# STM32_output_card.net
KiCad netlist of a schematic drawn in EAGLE
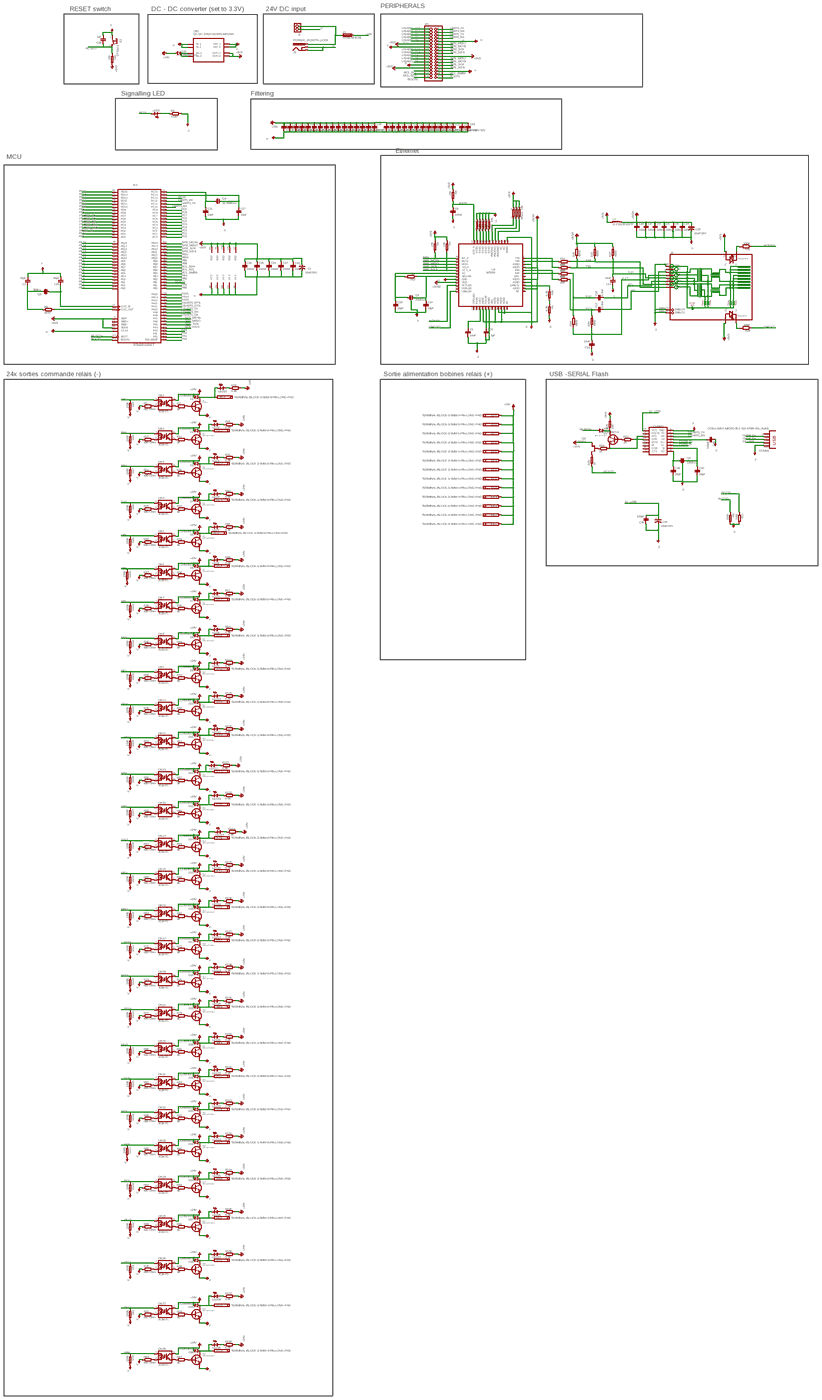
[diagram p0: schematic, sheet 1, overview]
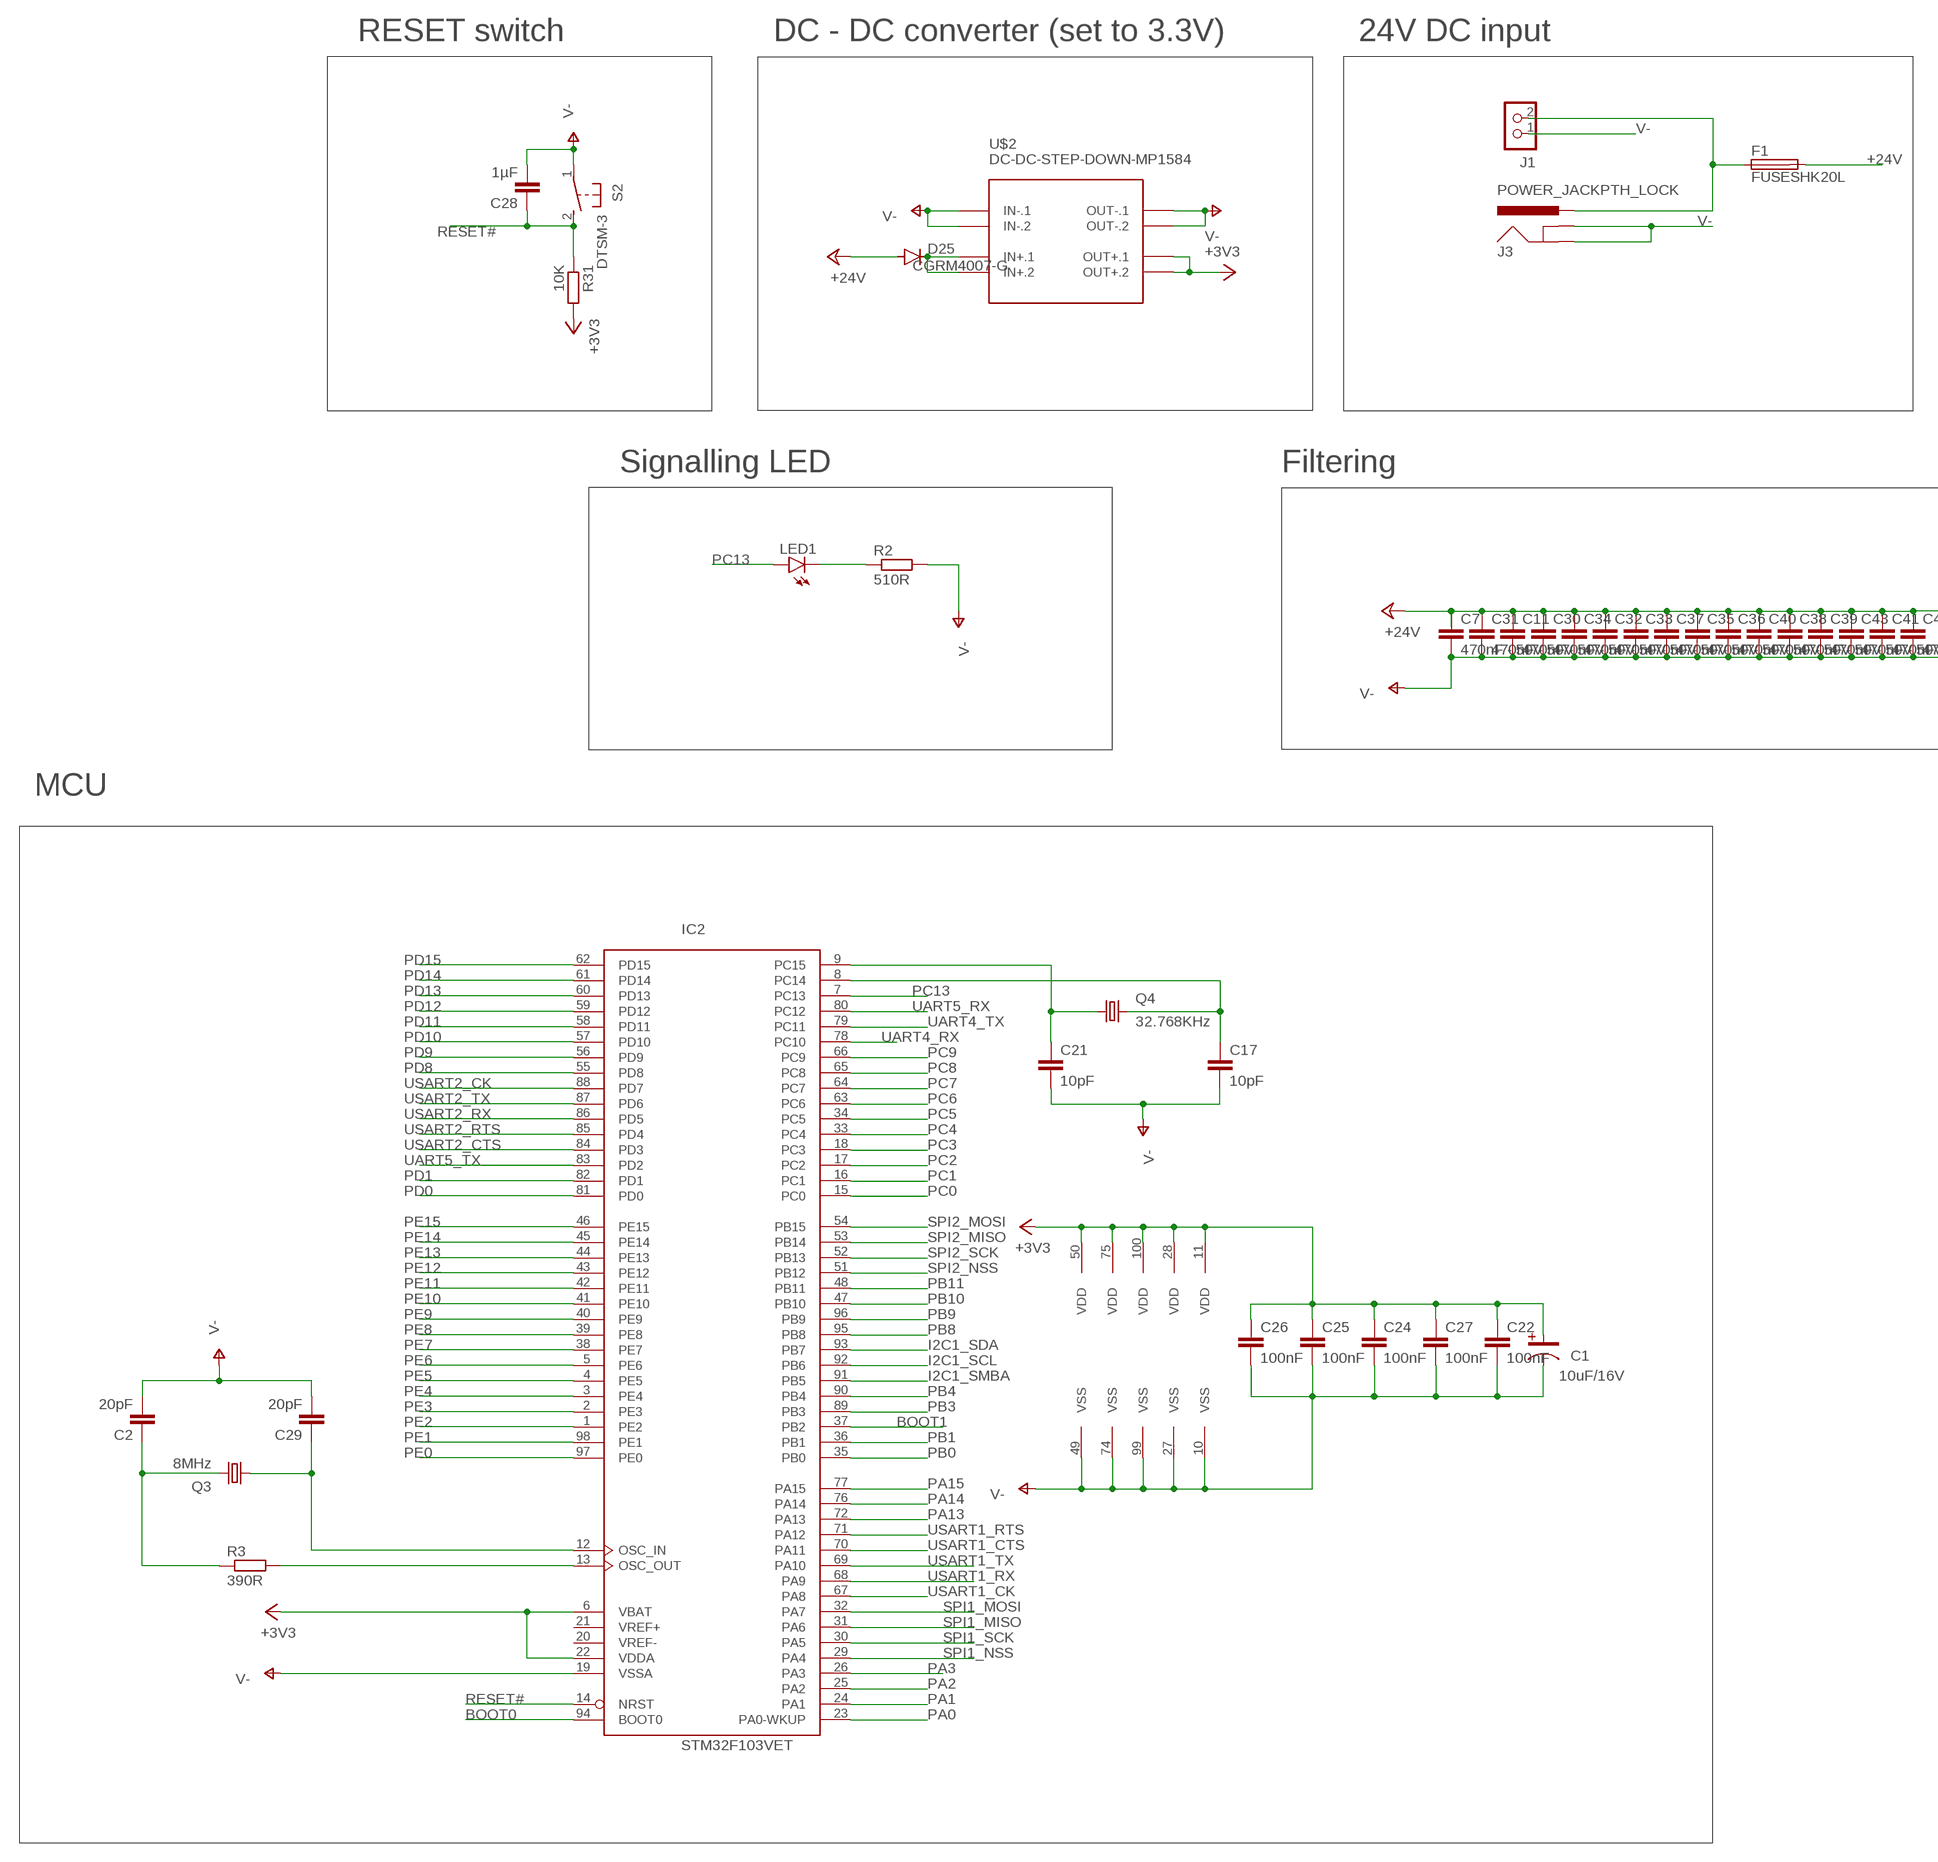
[diagram p1: schematic, sheet 1, part 1 of 6]
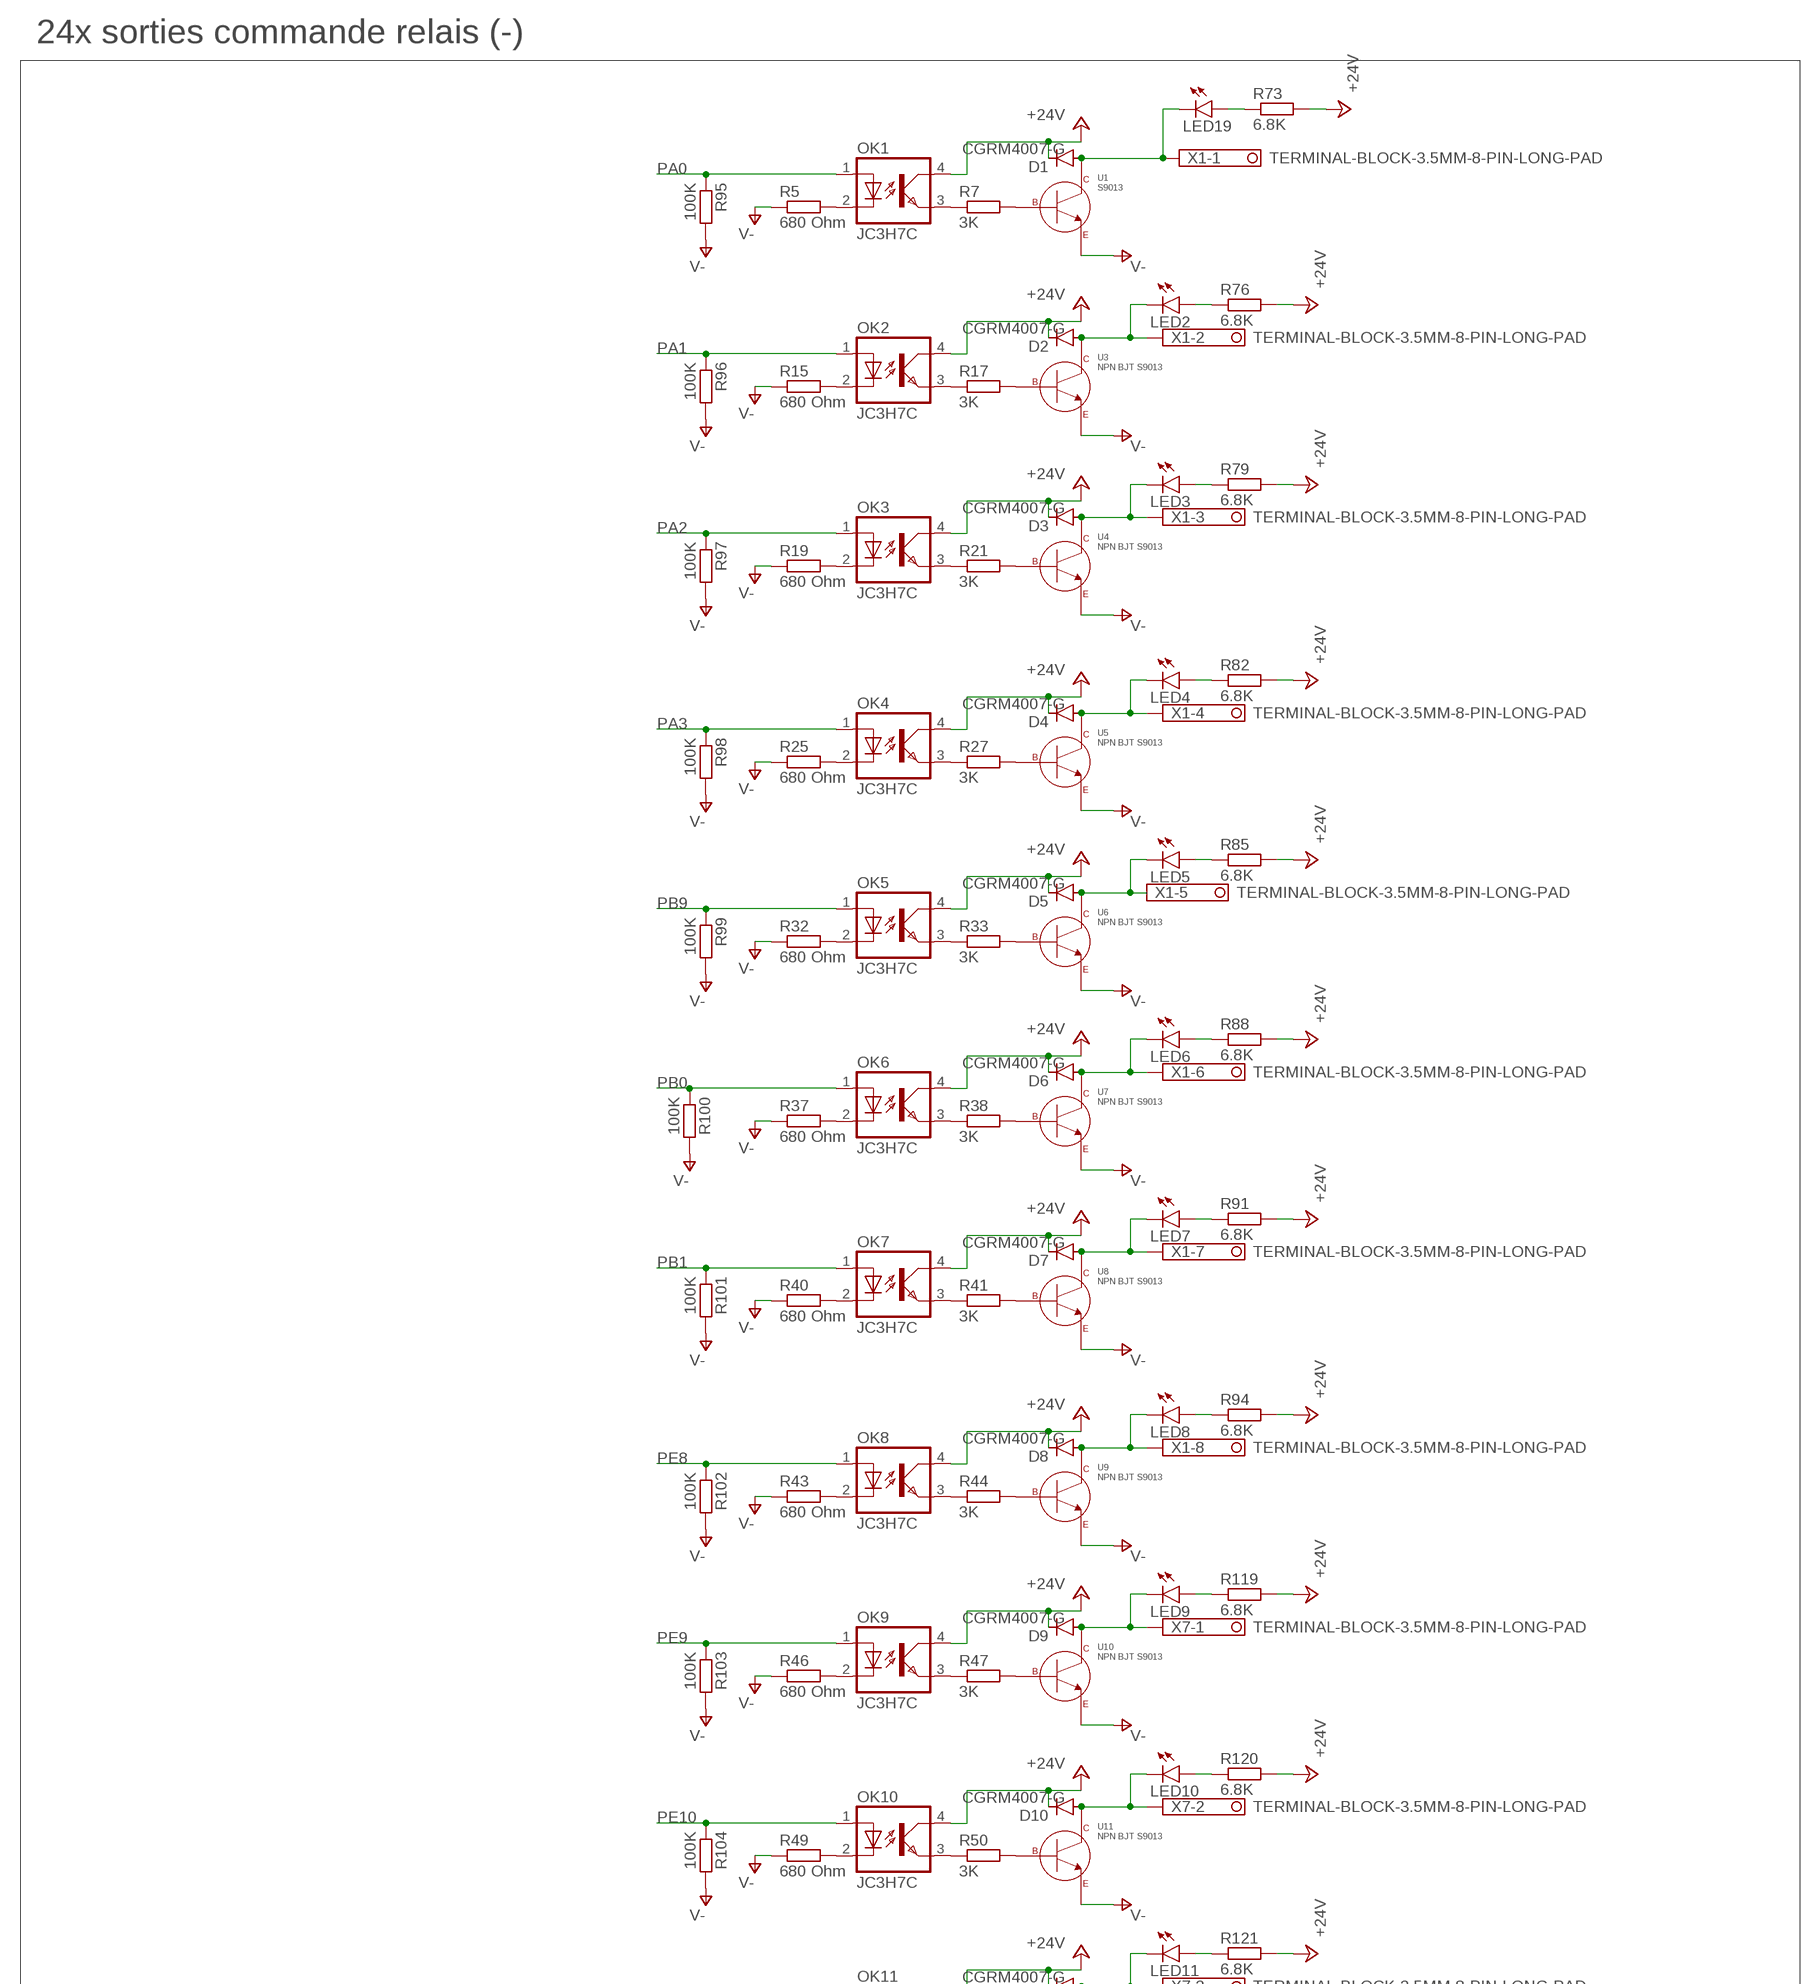
[diagram p2: schematic, sheet 1, part 2 of 6]
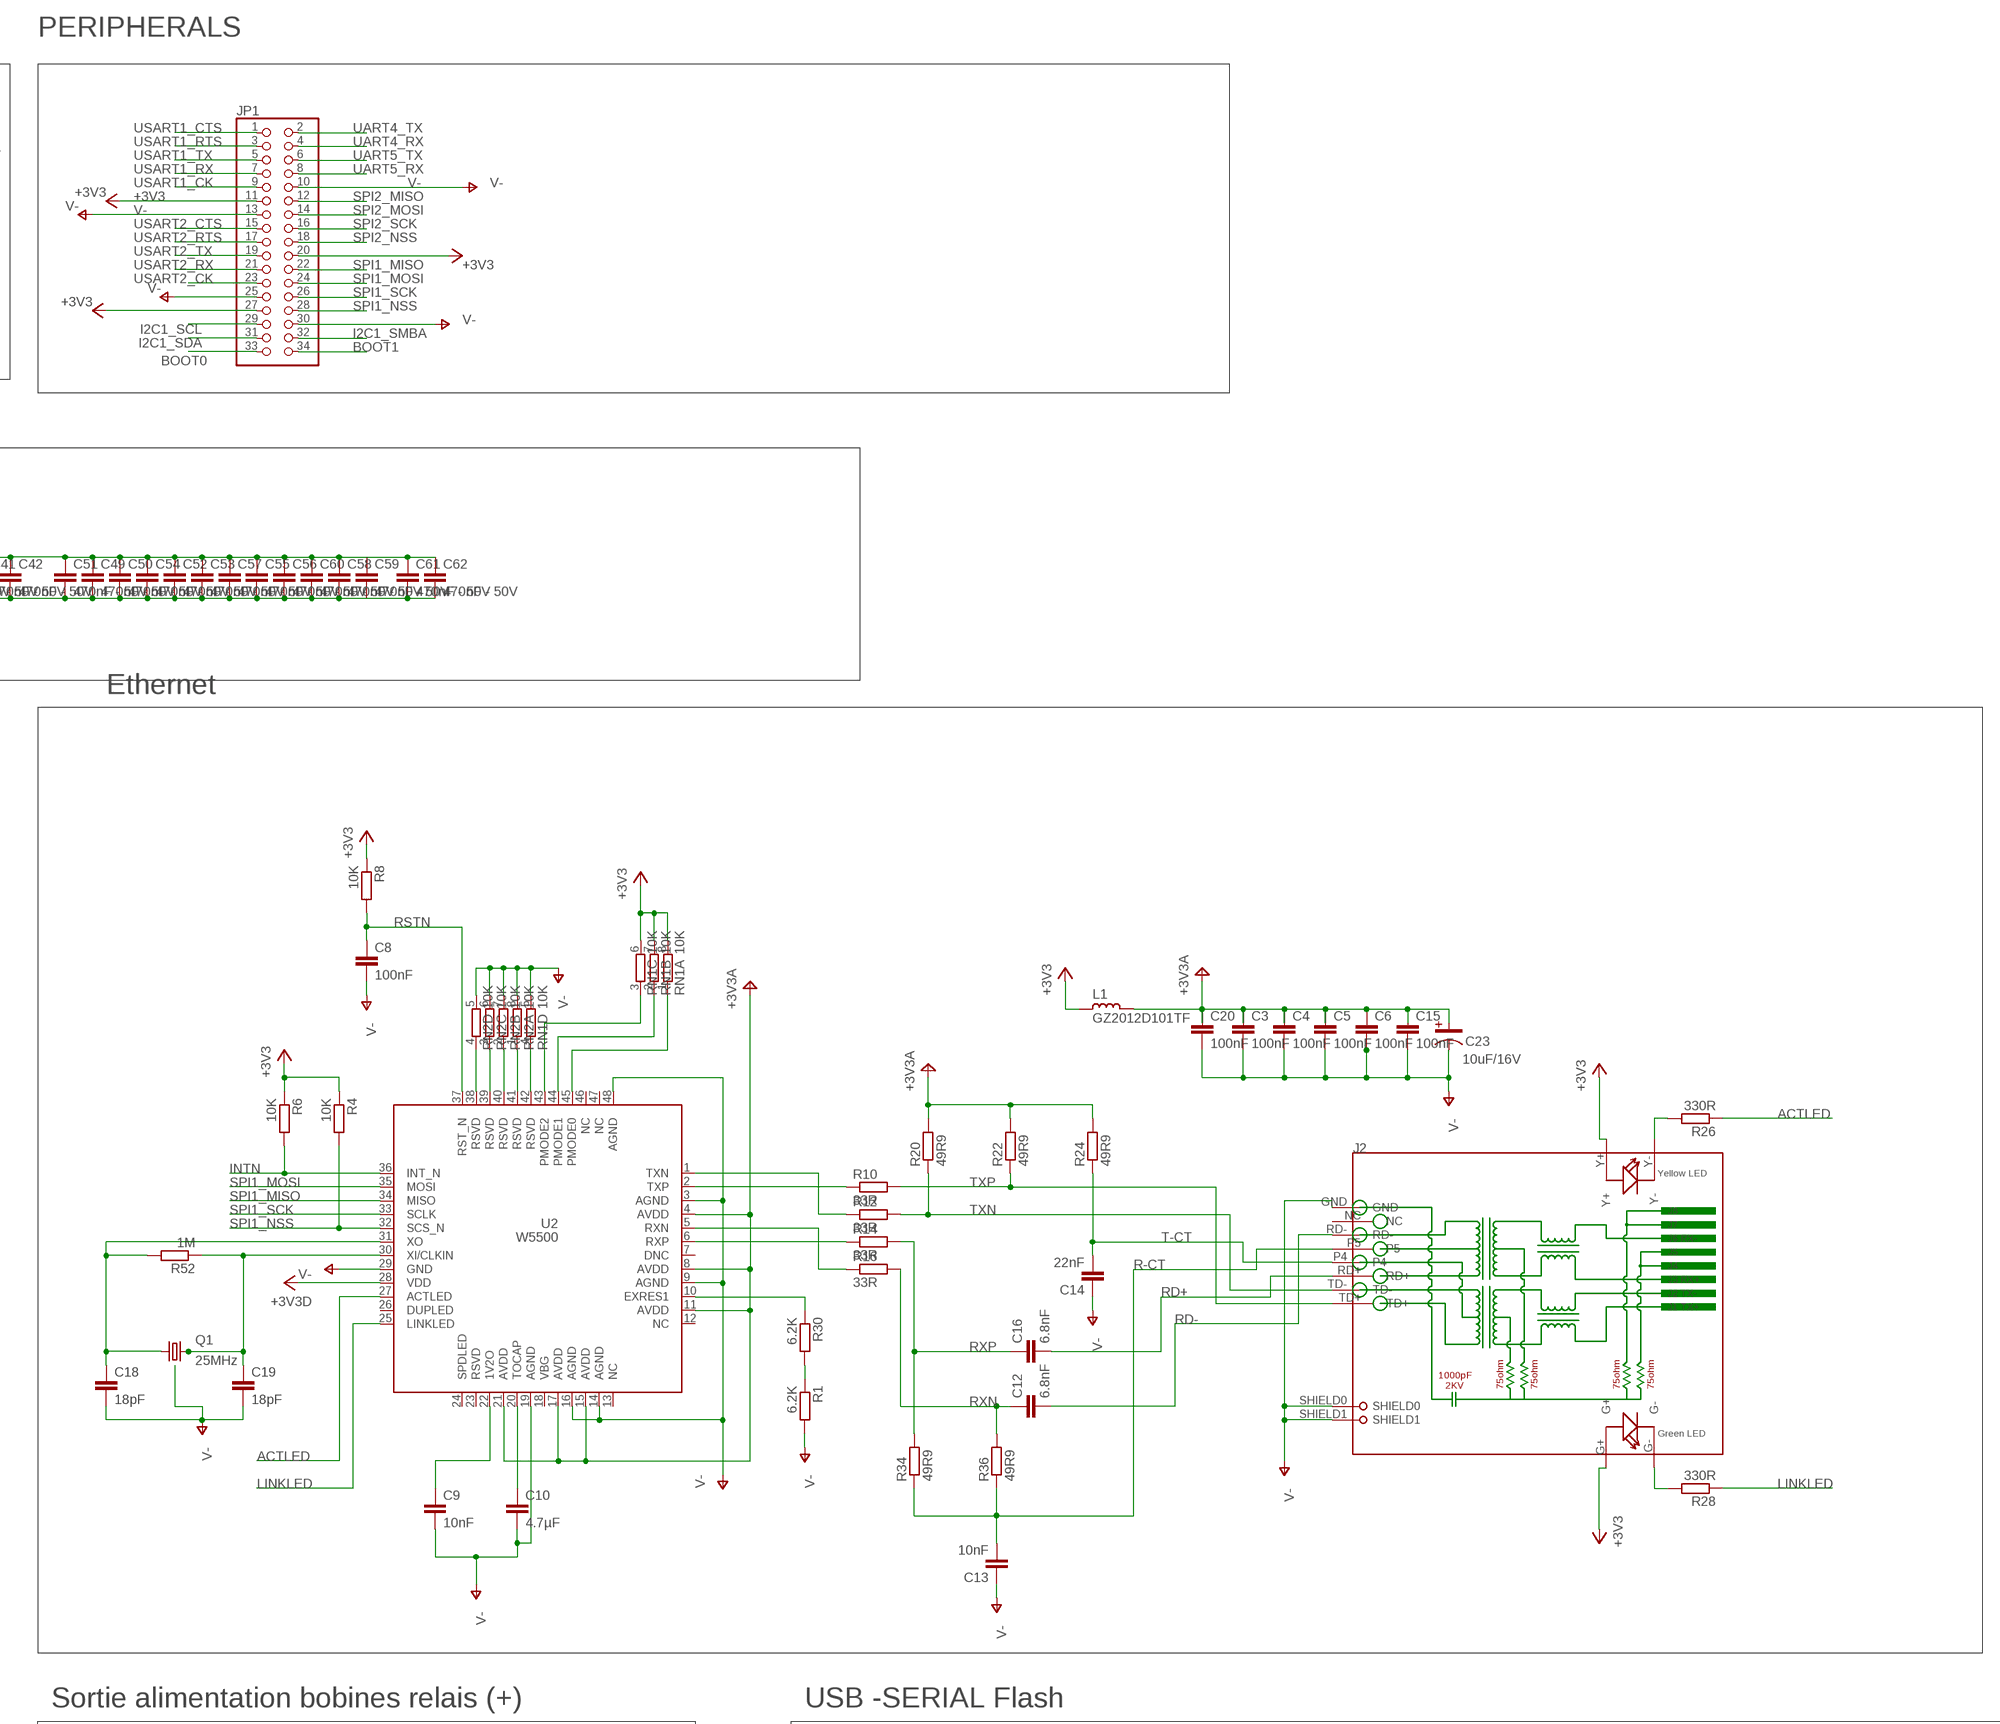
[diagram p3: schematic, sheet 1, part 3 of 6]
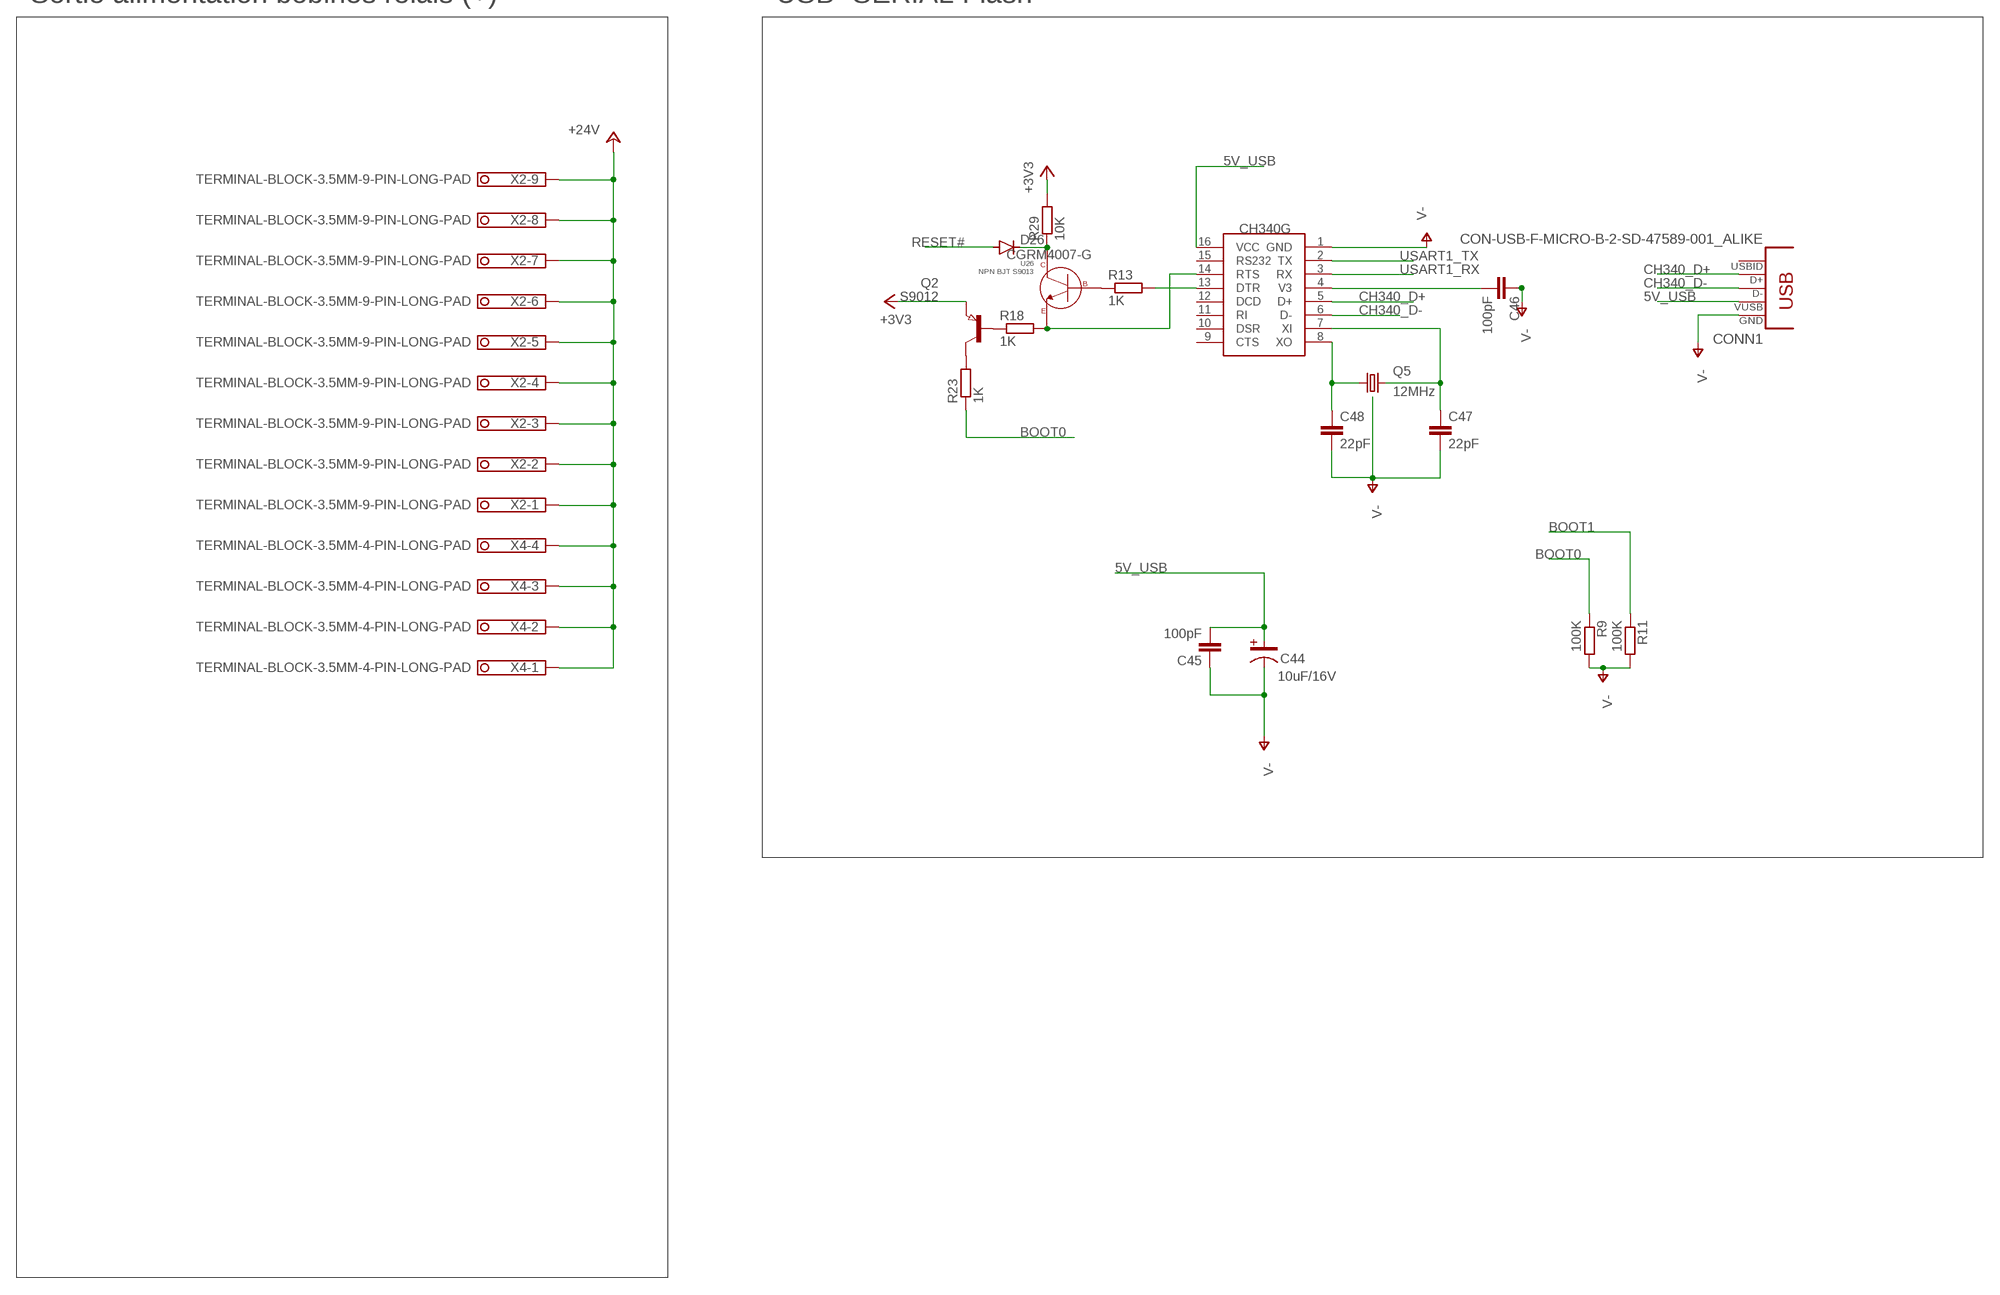
[diagram p4: schematic, sheet 1, part 4 of 6]
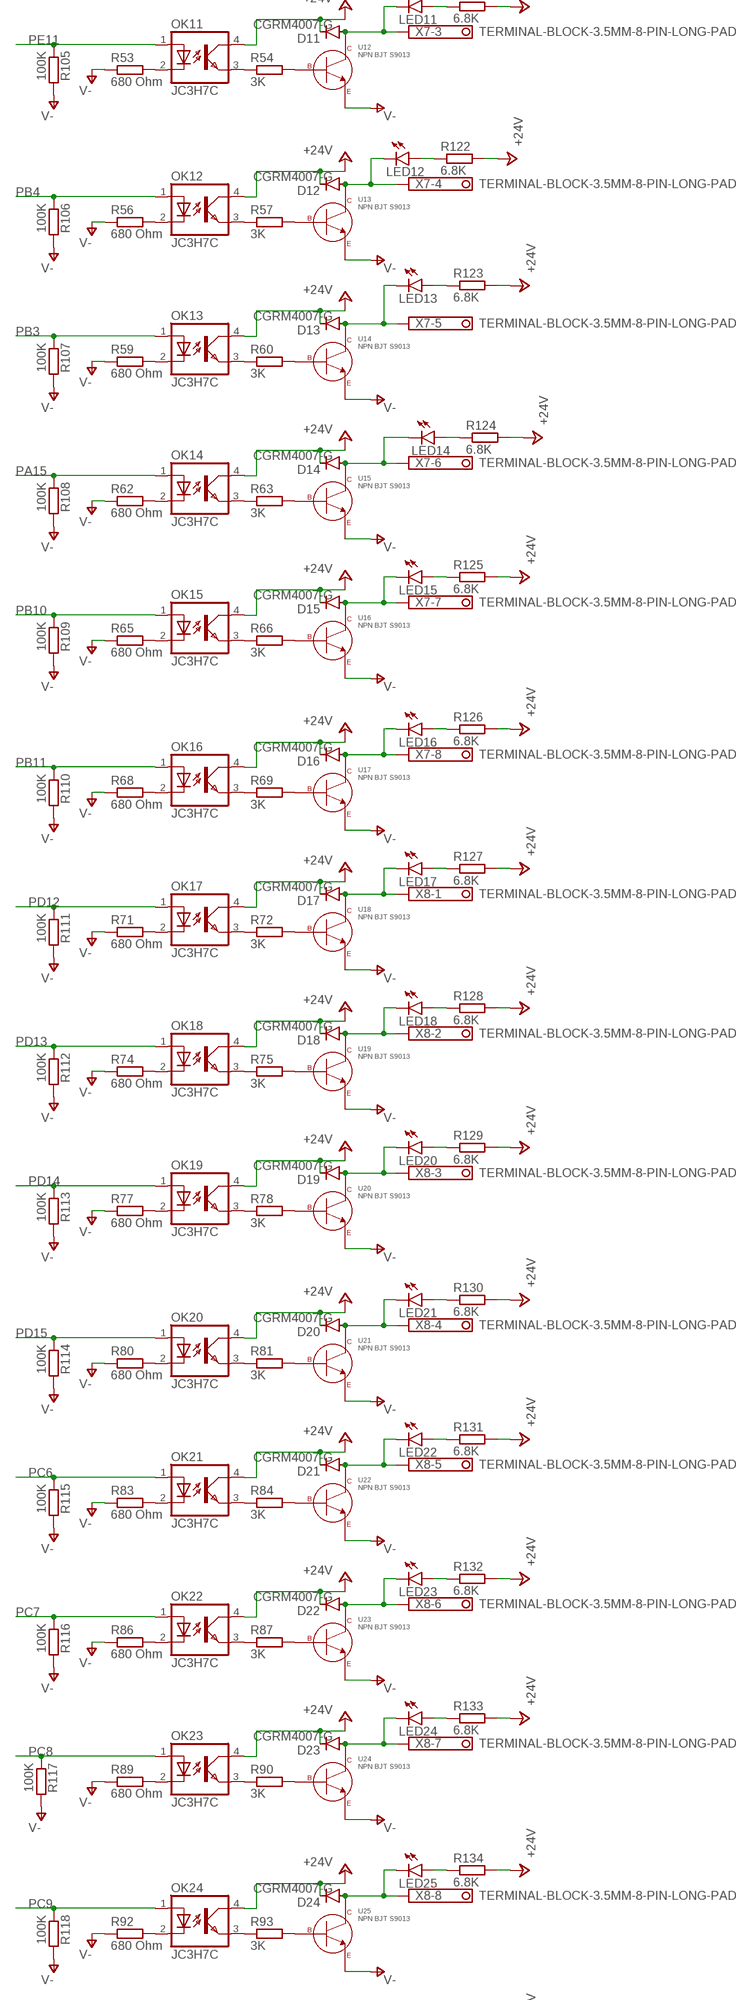
[diagram p5: schematic, sheet 1, part 5 of 6]
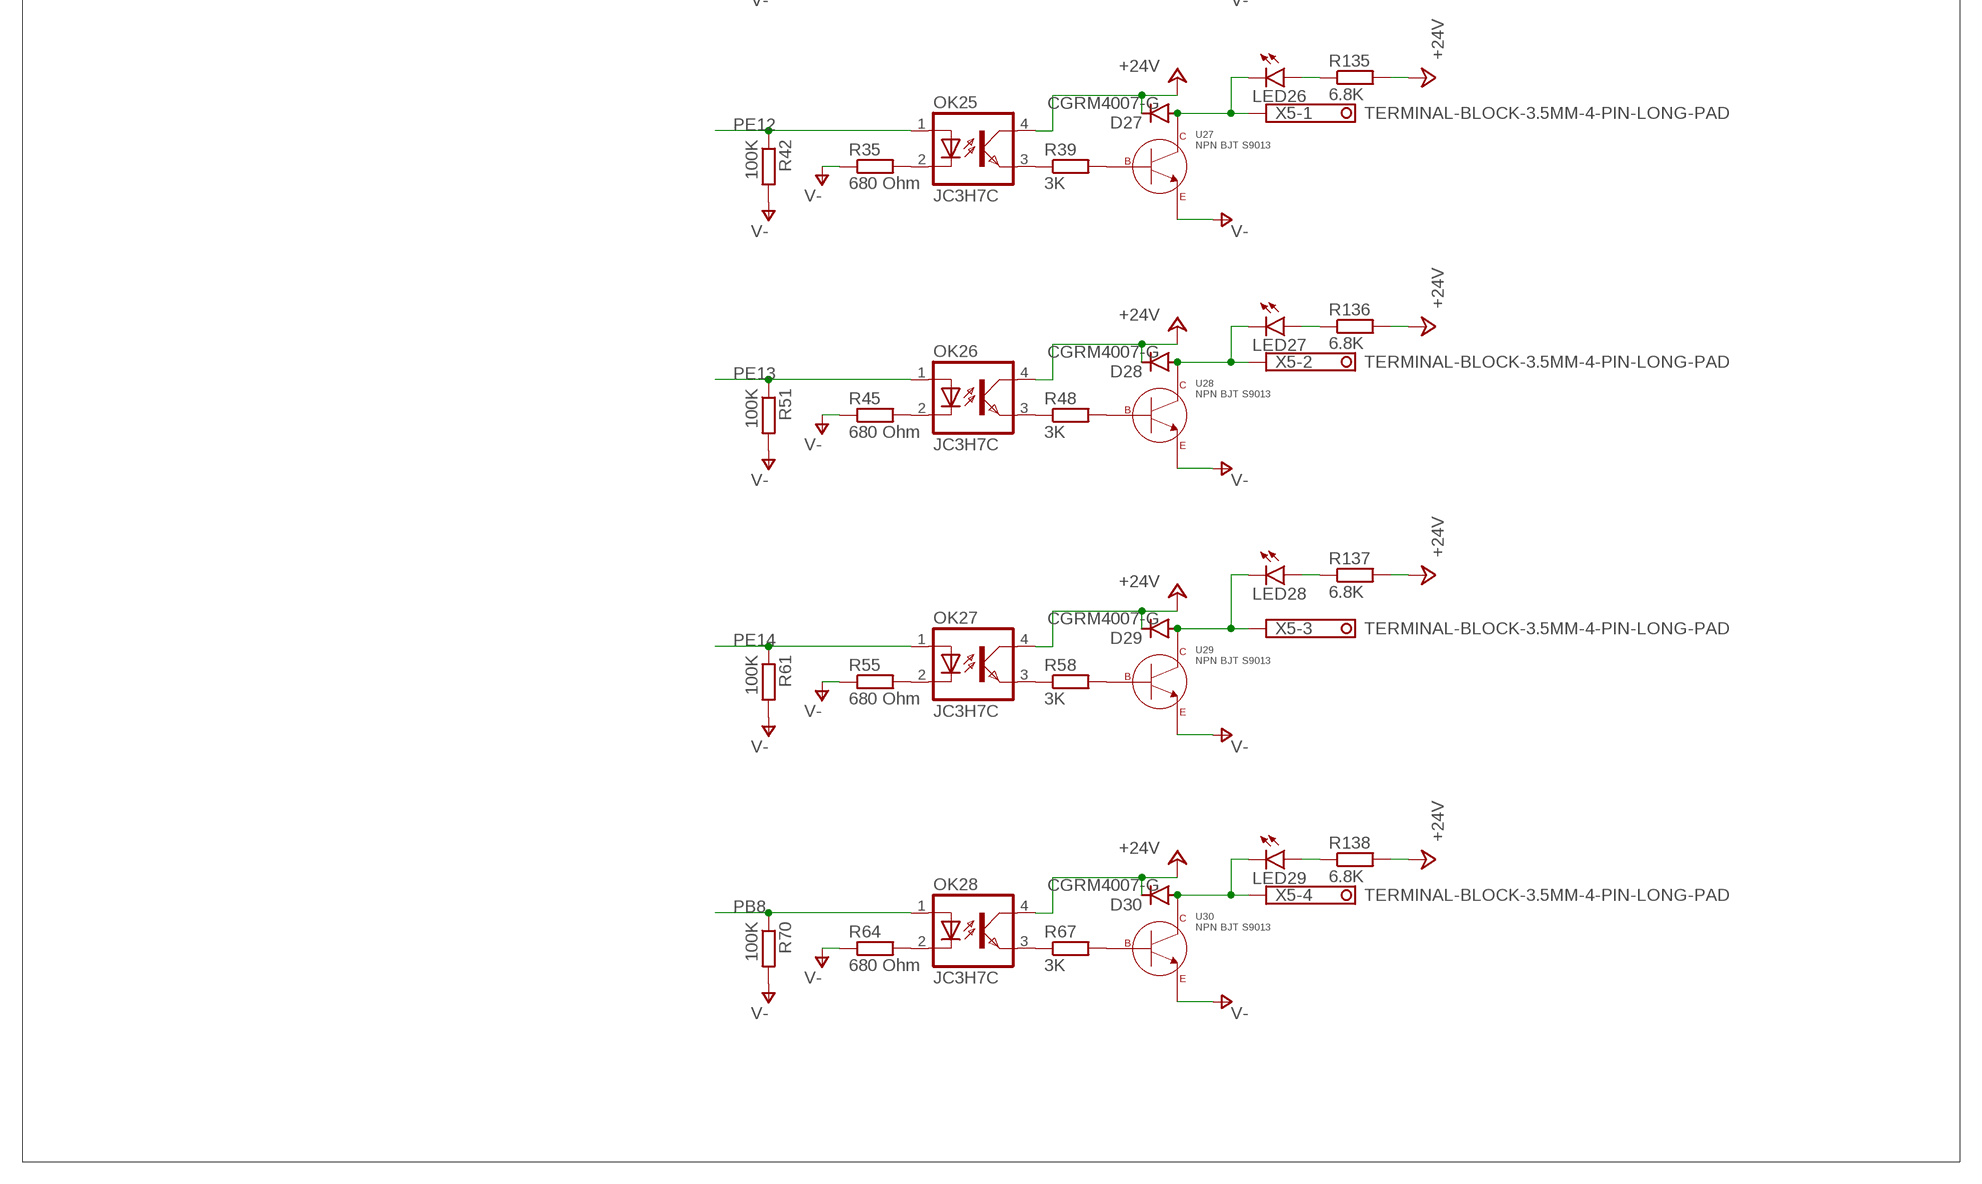
[diagram p6: schematic, sheet 1, part 6 of 6]

(export (version "E")
  (design (tool "Eeschema 10.0.6"))
  (components
    (comp (ref "C1")
      (value "10uF/16V")
      (footprint "eagle-import:C-3216(TANTAL)")
      (libsource (lib "eagle-import") (part "C-3216(TANTAL)"))
    )
    (comp (ref "C2")
      (value "20pF")
      (footprint "eagle-import:C0402")
      (libsource (lib "eagle-import") (part "C-EUC0402"))
    )
    (comp (ref "C3")
      (value "100nF")
      (footprint "eagle-import:C0402")
      (libsource (lib "eagle-import") (part "C-EUC0402"))
    )
    (comp (ref "C4")
      (value "100nF")
      (footprint "eagle-import:C0402")
      (libsource (lib "eagle-import") (part "C-EUC0402"))
    )
    (comp (ref "C5")
      (value "100nF")
      (footprint "eagle-import:C0402")
      (libsource (lib "eagle-import") (part "C-EUC0402"))
    )
    (comp (ref "C6")
      (value "100nF")
      (footprint "eagle-import:C0402")
      (libsource (lib "eagle-import") (part "C-EUC0402"))
    )
    (comp (ref "C7")
      (value "470nF - 50V")
      (footprint "eagle-import:C0805")
      (libsource (lib "eagle-import") (part "C-EUC0805"))
    )
    (comp (ref "C8")
      (value "100nF")
      (footprint "eagle-import:C0402")
      (libsource (lib "eagle-import") (part "C-EUC0402"))
    )
    (comp (ref "C9")
      (value "10nF")
      (footprint "eagle-import:C0402")
      (libsource (lib "eagle-import") (part "C-EUC0402"))
    )
    (comp (ref "C10")
      (value "4.7µF")
      (footprint "eagle-import:C0402")
      (libsource (lib "eagle-import") (part "C-EUC0402"))
    )
    (comp (ref "C11")
      (value "470nF - 50V")
      (footprint "eagle-import:C0805")
      (libsource (lib "eagle-import") (part "C-EUC0805"))
    )
    (comp (ref "C12")
      (value "6.8nF")
      (footprint "eagle-import:C0402")
      (libsource (lib "eagle-import") (part "C-EUC0402"))
    )
    (comp (ref "C13")
      (value "10nF")
      (footprint "eagle-import:C0402")
      (libsource (lib "eagle-import") (part "C-EUC0402"))
    )
    (comp (ref "C14")
      (value "22nF")
      (footprint "eagle-import:C0402")
      (libsource (lib "eagle-import") (part "C-EUC0402"))
    )
    (comp (ref "C15")
      (value "100nF")
      (footprint "eagle-import:C0402")
      (libsource (lib "eagle-import") (part "C-EUC0402"))
    )
    (comp (ref "C16")
      (value "6.8nF")
      (footprint "eagle-import:C0402")
      (libsource (lib "eagle-import") (part "C-EUC0402"))
    )
    (comp (ref "C17")
      (value "10pF")
      (footprint "eagle-import:C0402")
      (libsource (lib "eagle-import") (part "C-EUC0402"))
    )
    (comp (ref "C18")
      (value "18pF")
      (footprint "eagle-import:C0402")
      (libsource (lib "eagle-import") (part "C-EUC0402"))
    )
    (comp (ref "C19")
      (value "18pF")
      (footprint "eagle-import:C0402")
      (libsource (lib "eagle-import") (part "C-EUC0402"))
    )
    (comp (ref "C20")
      (value "100nF")
      (footprint "eagle-import:C0402")
      (libsource (lib "eagle-import") (part "C-EUC0402"))
    )
    (comp (ref "C21")
      (value "10pF")
      (footprint "eagle-import:C0402")
      (libsource (lib "eagle-import") (part "C-EUC0402"))
    )
    (comp (ref "C22")
      (value "100nF")
      (footprint "eagle-import:C0402")
      (libsource (lib "eagle-import") (part "C-EUC0402"))
    )
    (comp (ref "C23")
      (value "10uF/16V")
      (footprint "eagle-import:C-3216(TANTAL)")
      (libsource (lib "eagle-import") (part "C-3216(TANTAL)"))
    )
    (comp (ref "C24")
      (value "100nF")
      (footprint "eagle-import:C0402")
      (libsource (lib "eagle-import") (part "C-EUC0402"))
    )
    (comp (ref "C25")
      (value "100nF")
      (footprint "eagle-import:C0402")
      (libsource (lib "eagle-import") (part "C-EUC0402"))
    )
    (comp (ref "C26")
      (value "100nF")
      (footprint "eagle-import:C0402")
      (libsource (lib "eagle-import") (part "C-EUC0402"))
    )
    (comp (ref "C27")
      (value "100nF")
      (footprint "eagle-import:C0402")
      (libsource (lib "eagle-import") (part "C-EUC0402"))
    )
    (comp (ref "C28")
      (value "1µF")
      (footprint "eagle-import:C0402")
      (libsource (lib "eagle-import") (part "C-EUC0402"))
    )
    (comp (ref "C29")
      (value "20pF")
      (footprint "eagle-import:C0402")
      (libsource (lib "eagle-import") (part "C-EUC0402"))
    )
    (comp (ref "C30")
      (value "470nF - 50V")
      (footprint "eagle-import:C0805")
      (libsource (lib "eagle-import") (part "C-EUC0805"))
    )
    (comp (ref "C31")
      (value "470nF - 50V")
      (footprint "eagle-import:C0805")
      (libsource (lib "eagle-import") (part "C-EUC0805"))
    )
    (comp (ref "C32")
      (value "470nF - 50V")
      (footprint "eagle-import:C0805")
      (libsource (lib "eagle-import") (part "C-EUC0805"))
    )
    (comp (ref "C33")
      (value "470nF - 50V")
      (footprint "eagle-import:C0805")
      (libsource (lib "eagle-import") (part "C-EUC0805"))
    )
    (comp (ref "C34")
      (value "470nF - 50V")
      (footprint "eagle-import:C0805")
      (libsource (lib "eagle-import") (part "C-EUC0805"))
    )
    (comp (ref "C35")
      (value "470nF - 50V")
      (footprint "eagle-import:C0805")
      (libsource (lib "eagle-import") (part "C-EUC0805"))
    )
    (comp (ref "C36")
      (value "470nF - 50V")
      (footprint "eagle-import:C0805")
      (libsource (lib "eagle-import") (part "C-EUC0805"))
    )
    (comp (ref "C37")
      (value "470nF - 50V")
      (footprint "eagle-import:C0805")
      (libsource (lib "eagle-import") (part "C-EUC0805"))
    )
    (comp (ref "C38")
      (value "470nF - 50V")
      (footprint "eagle-import:C0805")
      (libsource (lib "eagle-import") (part "C-EUC0805"))
    )
    (comp (ref "C39")
      (value "470nF - 50V")
      (footprint "eagle-import:C0805")
      (libsource (lib "eagle-import") (part "C-EUC0805"))
    )
    (comp (ref "C40")
      (value "470nF - 50V")
      (footprint "eagle-import:C0805")
      (libsource (lib "eagle-import") (part "C-EUC0805"))
    )
    (comp (ref "C41")
      (value "470nF - 50V")
      (footprint "eagle-import:C0805")
      (libsource (lib "eagle-import") (part "C-EUC0805"))
    )
    (comp (ref "C42")
      (value "470nF - 50V")
      (footprint "eagle-import:C0805")
      (libsource (lib "eagle-import") (part "C-EUC0805"))
    )
    (comp (ref "C43")
      (value "470nF - 50V")
      (footprint "eagle-import:C0805")
      (libsource (lib "eagle-import") (part "C-EUC0805"))
    )
    (comp (ref "C44")
      (value "10uF/16V")
      (footprint "eagle-import:C-3216(TANTAL)")
      (libsource (lib "eagle-import") (part "C-3216(TANTAL)"))
    )
    (comp (ref "C45")
      (value "100pF")
      (footprint "eagle-import:C0402")
      (libsource (lib "eagle-import") (part "C-EUC0402"))
    )
    (comp (ref "C46")
      (value "100pF")
      (footprint "eagle-import:C0402")
      (libsource (lib "eagle-import") (part "C-EUC0402"))
    )
    (comp (ref "C47")
      (value "22pF")
      (footprint "eagle-import:C0402")
      (libsource (lib "eagle-import") (part "C-EUC0402"))
    )
    (comp (ref "C48")
      (value "22pF")
      (footprint "eagle-import:C0402")
      (libsource (lib "eagle-import") (part "C-EUC0402"))
    )
    (comp (ref "C49")
      (value "470nF - 50V")
      (footprint "eagle-import:C0805")
      (libsource (lib "eagle-import") (part "C-EUC0805"))
    )
    (comp (ref "C50")
      (value "470nF - 50V")
      (footprint "eagle-import:C0805")
      (libsource (lib "eagle-import") (part "C-EUC0805"))
    )
    (comp (ref "C51")
      (value "470nF - 50V")
      (footprint "eagle-import:C0805")
      (libsource (lib "eagle-import") (part "C-EUC0805"))
    )
    (comp (ref "C52")
      (value "470nF - 50V")
      (footprint "eagle-import:C0805")
      (libsource (lib "eagle-import") (part "C-EUC0805"))
    )
    (comp (ref "C53")
      (value "470nF - 50V")
      (footprint "eagle-import:C0805")
      (libsource (lib "eagle-import") (part "C-EUC0805"))
    )
    (comp (ref "C54")
      (value "470nF - 50V")
      (footprint "eagle-import:C0805")
      (libsource (lib "eagle-import") (part "C-EUC0805"))
    )
    (comp (ref "C55")
      (value "470nF - 50V")
      (footprint "eagle-import:C0805")
      (libsource (lib "eagle-import") (part "C-EUC0805"))
    )
    (comp (ref "C56")
      (value "470nF - 50V")
      (footprint "eagle-import:C0805")
      (libsource (lib "eagle-import") (part "C-EUC0805"))
    )
    (comp (ref "C57")
      (value "470nF - 50V")
      (footprint "eagle-import:C0805")
      (libsource (lib "eagle-import") (part "C-EUC0805"))
    )
    (comp (ref "C58")
      (value "470nF - 50V")
      (footprint "eagle-import:C0805")
      (libsource (lib "eagle-import") (part "C-EUC0805"))
    )
    (comp (ref "C59")
      (value "470nF - 50V")
      (footprint "eagle-import:C0805")
      (libsource (lib "eagle-import") (part "C-EUC0805"))
    )
    (comp (ref "C60")
      (value "470nF - 50V")
      (footprint "eagle-import:C0805")
      (libsource (lib "eagle-import") (part "C-EUC0805"))
    )
    (comp (ref "C61")
      (value "470nF - 50V")
      (footprint "eagle-import:C0805")
      (libsource (lib "eagle-import") (part "C-EUC0805"))
    )
    (comp (ref "C62")
      (value "470nF - 50V")
      (footprint "eagle-import:C0805")
      (libsource (lib "eagle-import") (part "C-EUC0805"))
    )
    (comp (ref "CONN1")
      (value "CON-USB-F-MICRO-B-2-SD-47589-001_ALIKE")
      (footprint "eagle-import:CON_USB_MICRO-B-3")
      (libsource (lib "eagle-import") (part "CON-USB-F-MICRO-B-2-SD-47589-001_ALIKE"))
    )
    (comp (ref "D1")
      (value "CGRM4007-G")
      (footprint "eagle-import:SOD-123_MINI-SMA")
      (libsource (lib "eagle-import") (part "CGRM400-G7"))
    )
    (comp (ref "D2")
      (value "CGRM4007-G")
      (footprint "eagle-import:SOD-123_MINI-SMA")
      (libsource (lib "eagle-import") (part "CGRM400-G7"))
    )
    (comp (ref "D3")
      (value "CGRM4007-G")
      (footprint "eagle-import:SOD-123_MINI-SMA")
      (libsource (lib "eagle-import") (part "CGRM400-G7"))
    )
    (comp (ref "D4")
      (value "CGRM4007-G")
      (footprint "eagle-import:SOD-123_MINI-SMA")
      (libsource (lib "eagle-import") (part "CGRM400-G7"))
    )
    (comp (ref "D5")
      (value "CGRM4007-G")
      (footprint "eagle-import:SOD-123_MINI-SMA")
      (libsource (lib "eagle-import") (part "CGRM400-G7"))
    )
    (comp (ref "D6")
      (value "CGRM4007-G")
      (footprint "eagle-import:SOD-123_MINI-SMA")
      (libsource (lib "eagle-import") (part "CGRM400-G7"))
    )
    (comp (ref "D7")
      (value "CGRM4007-G")
      (footprint "eagle-import:SOD-123_MINI-SMA")
      (libsource (lib "eagle-import") (part "CGRM400-G7"))
    )
    (comp (ref "D8")
      (value "CGRM4007-G")
      (footprint "eagle-import:SOD-123_MINI-SMA")
      (libsource (lib "eagle-import") (part "CGRM400-G7"))
    )
    (comp (ref "D9")
      (value "CGRM4007-G")
      (footprint "eagle-import:SOD-123_MINI-SMA")
      (libsource (lib "eagle-import") (part "CGRM400-G7"))
    )
    (comp (ref "D10")
      (value "CGRM4007-G")
      (footprint "eagle-import:SOD-123_MINI-SMA")
      (libsource (lib "eagle-import") (part "CGRM400-G7"))
    )
    (comp (ref "D11")
      (value "CGRM4007-G")
      (footprint "eagle-import:SOD-123_MINI-SMA")
      (libsource (lib "eagle-import") (part "CGRM400-G7"))
    )
    (comp (ref "D12")
      (value "CGRM4007-G")
      (footprint "eagle-import:SOD-123_MINI-SMA")
      (libsource (lib "eagle-import") (part "CGRM400-G7"))
    )
    (comp (ref "D13")
      (value "CGRM4007-G")
      (footprint "eagle-import:SOD-123_MINI-SMA")
      (libsource (lib "eagle-import") (part "CGRM400-G7"))
    )
    (comp (ref "D14")
      (value "CGRM4007-G")
      (footprint "eagle-import:SOD-123_MINI-SMA")
      (libsource (lib "eagle-import") (part "CGRM400-G7"))
    )
    (comp (ref "D15")
      (value "CGRM4007-G")
      (footprint "eagle-import:SOD-123_MINI-SMA")
      (libsource (lib "eagle-import") (part "CGRM400-G7"))
    )
    (comp (ref "D16")
      (value "CGRM4007-G")
      (footprint "eagle-import:SOD-123_MINI-SMA")
      (libsource (lib "eagle-import") (part "CGRM400-G7"))
    )
    (comp (ref "D17")
      (value "CGRM4007-G")
      (footprint "eagle-import:SOD-123_MINI-SMA")
      (libsource (lib "eagle-import") (part "CGRM400-G7"))
    )
    (comp (ref "D18")
      (value "CGRM4007-G")
      (footprint "eagle-import:SOD-123_MINI-SMA")
      (libsource (lib "eagle-import") (part "CGRM400-G7"))
    )
    (comp (ref "D19")
      (value "CGRM4007-G")
      (footprint "eagle-import:SOD-123_MINI-SMA")
      (libsource (lib "eagle-import") (part "CGRM400-G7"))
    )
    (comp (ref "D20")
      (value "CGRM4007-G")
      (footprint "eagle-import:SOD-123_MINI-SMA")
      (libsource (lib "eagle-import") (part "CGRM400-G7"))
    )
    (comp (ref "D21")
      (value "CGRM4007-G")
      (footprint "eagle-import:SOD-123_MINI-SMA")
      (libsource (lib "eagle-import") (part "CGRM400-G7"))
    )
    (comp (ref "D22")
      (value "CGRM4007-G")
      (footprint "eagle-import:SOD-123_MINI-SMA")
      (libsource (lib "eagle-import") (part "CGRM400-G7"))
    )
    (comp (ref "D23")
      (value "CGRM4007-G")
      (footprint "eagle-import:SOD-123_MINI-SMA")
      (libsource (lib "eagle-import") (part "CGRM400-G7"))
    )
    (comp (ref "D24")
      (value "CGRM4007-G")
      (footprint "eagle-import:SOD-123_MINI-SMA")
      (libsource (lib "eagle-import") (part "CGRM400-G7"))
    )
    (comp (ref "D25")
      (value "CGRM4007-G")
      (footprint "eagle-import:SOD-123_MINI-SMA")
      (libsource (lib "eagle-import") (part "CGRM400-G7"))
    )
    (comp (ref "D26")
      (value "CGRM4007-G")
      (footprint "eagle-import:SOD-123_MINI-SMA")
      (libsource (lib "eagle-import") (part "CGRM400-G7"))
    )
    (comp (ref "D27")
      (value "CGRM4007-G")
      (footprint "eagle-import:SOD-123_MINI-SMA")
      (libsource (lib "eagle-import") (part "CGRM400-G7"))
    )
    (comp (ref "D28")
      (value "CGRM4007-G")
      (footprint "eagle-import:SOD-123_MINI-SMA")
      (libsource (lib "eagle-import") (part "CGRM400-G7"))
    )
    (comp (ref "D29")
      (value "CGRM4007-G")
      (footprint "eagle-import:SOD-123_MINI-SMA")
      (libsource (lib "eagle-import") (part "CGRM400-G7"))
    )
    (comp (ref "D30")
      (value "CGRM4007-G")
      (footprint "eagle-import:SOD-123_MINI-SMA")
      (libsource (lib "eagle-import") (part "CGRM400-G7"))
    )
    (comp (ref "F1")
      (value "FUSESHK20L")
      (footprint "eagle-import:SHK20L")
      (libsource (lib "eagle-import") (part "FUSESHK20L"))
    )
    (comp (ref "IC2")
      (value "STM32F103VET")
      (footprint "eagle-import:LQFP100")
      (libsource (lib "eagle-import") (part "STM32F103VTE"))
    )
    (comp (ref "J1")
      (value "CON_TERMINAL_BLOCK_02-5MM")
      (footprint "eagle-import:TERMINAL_BLOCK_2P_5")
      (libsource (lib "eagle-import") (part "CON_TERMINAL_BLOCK_02-5MM"))
    )
    (comp (ref "J2")
      (value "RJ45-HR911105A-HR911105A")
      (footprint "eagle-import:RJ45")
      (libsource (lib "eagle-import") (part "RJ45-HR911105A-HR911105A"))
    )
    (comp (ref "J3")
      (value "POWER_JACKPTH_LOCK")
      (footprint "eagle-import:POWER_JACK_PTH_LOCK")
      (libsource (lib "eagle-import") (part "POWER_JACKPTH_LOCK"))
    )
    (comp (ref "JP1")
      (value "PINHD-2X17")
      (footprint "eagle-import:2X17")
      (libsource (lib "eagle-import") (part "PINHD-2X17"))
    )
    (comp (ref "L1")
      (value "GZ2012D101TF")
      (footprint "eagle-import:L0805")
      (libsource (lib "eagle-import") (part "L_0805"))
    )
    (comp (ref "LED1")
      (value "LEDCHIP-LED0603")
      (footprint "eagle-import:CHIP-LED0603")
      (libsource (lib "eagle-import") (part "LEDCHIP-LED0603"))
    )
    (comp (ref "LED2")
      (value "LEDSML0603")
      (footprint "eagle-import:SML0603")
      (libsource (lib "eagle-import") (part "LEDSML0603"))
    )
    (comp (ref "LED3")
      (value "LEDSML0603")
      (footprint "eagle-import:SML0603")
      (libsource (lib "eagle-import") (part "LEDSML0603"))
    )
    (comp (ref "LED4")
      (value "LEDSML0603")
      (footprint "eagle-import:SML0603")
      (libsource (lib "eagle-import") (part "LEDSML0603"))
    )
    (comp (ref "LED5")
      (value "LEDSML0603")
      (footprint "eagle-import:SML0603")
      (libsource (lib "eagle-import") (part "LEDSML0603"))
    )
    (comp (ref "LED6")
      (value "LEDSML0603")
      (footprint "eagle-import:SML0603")
      (libsource (lib "eagle-import") (part "LEDSML0603"))
    )
    (comp (ref "LED7")
      (value "LEDSML0603")
      (footprint "eagle-import:SML0603")
      (libsource (lib "eagle-import") (part "LEDSML0603"))
    )
    (comp (ref "LED8")
      (value "LEDSML0603")
      (footprint "eagle-import:SML0603")
      (libsource (lib "eagle-import") (part "LEDSML0603"))
    )
    (comp (ref "LED9")
      (value "LEDSML0603")
      (footprint "eagle-import:SML0603")
      (libsource (lib "eagle-import") (part "LEDSML0603"))
    )
    (comp (ref "LED10")
      (value "LEDSML0603")
      (footprint "eagle-import:SML0603")
      (libsource (lib "eagle-import") (part "LEDSML0603"))
    )
    (comp (ref "LED11")
      (value "LEDSML0603")
      (footprint "eagle-import:SML0603")
      (libsource (lib "eagle-import") (part "LEDSML0603"))
    )
    (comp (ref "LED12")
      (value "LEDSML0603")
      (footprint "eagle-import:SML0603")
      (libsource (lib "eagle-import") (part "LEDSML0603"))
    )
    (comp (ref "LED13")
      (value "LEDSML0603")
      (footprint "eagle-import:SML0603")
      (libsource (lib "eagle-import") (part "LEDSML0603"))
    )
    (comp (ref "LED14")
      (value "LEDSML0603")
      (footprint "eagle-import:SML0603")
      (libsource (lib "eagle-import") (part "LEDSML0603"))
    )
    (comp (ref "LED15")
      (value "LEDSML0603")
      (footprint "eagle-import:SML0603")
      (libsource (lib "eagle-import") (part "LEDSML0603"))
    )
    (comp (ref "LED16")
      (value "LEDSML0603")
      (footprint "eagle-import:SML0603")
      (libsource (lib "eagle-import") (part "LEDSML0603"))
    )
    (comp (ref "LED17")
      (value "LEDSML0603")
      (footprint "eagle-import:SML0603")
      (libsource (lib "eagle-import") (part "LEDSML0603"))
    )
    (comp (ref "LED18")
      (value "LEDSML0603")
      (footprint "eagle-import:SML0603")
      (libsource (lib "eagle-import") (part "LEDSML0603"))
    )
    (comp (ref "LED19")
      (value "LEDSML0603")
      (footprint "eagle-import:SML0603")
      (libsource (lib "eagle-import") (part "LEDSML0603"))
    )
    (comp (ref "LED20")
      (value "LEDSML0603")
      (footprint "eagle-import:SML0603")
      (libsource (lib "eagle-import") (part "LEDSML0603"))
    )
    (comp (ref "LED21")
      (value "LEDSML0603")
      (footprint "eagle-import:SML0603")
      (libsource (lib "eagle-import") (part "LEDSML0603"))
    )
    (comp (ref "LED22")
      (value "LEDSML0603")
      (footprint "eagle-import:SML0603")
      (libsource (lib "eagle-import") (part "LEDSML0603"))
    )
    (comp (ref "LED23")
      (value "LEDSML0603")
      (footprint "eagle-import:SML0603")
      (libsource (lib "eagle-import") (part "LEDSML0603"))
    )
    (comp (ref "LED24")
      (value "LEDSML0603")
      (footprint "eagle-import:SML0603")
      (libsource (lib "eagle-import") (part "LEDSML0603"))
    )
    (comp (ref "LED25")
      (value "LEDSML0603")
      (footprint "eagle-import:SML0603")
      (libsource (lib "eagle-import") (part "LEDSML0603"))
    )
    (comp (ref "LED26")
      (value "LEDSML0603")
      (footprint "eagle-import:SML0603")
      (libsource (lib "eagle-import") (part "LEDSML0603"))
    )
    (comp (ref "LED27")
      (value "LEDSML0603")
      (footprint "eagle-import:SML0603")
      (libsource (lib "eagle-import") (part "LEDSML0603"))
    )
    (comp (ref "LED28")
      (value "LEDSML0603")
      (footprint "eagle-import:SML0603")
      (libsource (lib "eagle-import") (part "LEDSML0603"))
    )
    (comp (ref "LED29")
      (value "LEDSML0603")
      (footprint "eagle-import:SML0603")
      (libsource (lib "eagle-import") (part "LEDSML0603"))
    )
    (comp (ref "OK1")
      (value "JC3H7C")
      (footprint "eagle-import:MINI-FLAT-4")
      (fields (field (name "LCSCPART#") "C55287"))
      (libsource (lib "eagle-import") (part "JC3H7C"))
    )
    (comp (ref "OK2")
      (value "JC3H7C")
      (footprint "eagle-import:MINI-FLAT-4")
      (fields (field (name "LCSCPART#") "C55287"))
      (libsource (lib "eagle-import") (part "JC3H7C"))
    )
    (comp (ref "OK3")
      (value "JC3H7C")
      (footprint "eagle-import:MINI-FLAT-4")
      (fields (field (name "LCSCPART#") "C55287"))
      (libsource (lib "eagle-import") (part "JC3H7C"))
    )
    (comp (ref "OK4")
      (value "JC3H7C")
      (footprint "eagle-import:MINI-FLAT-4")
      (fields (field (name "LCSCPART#") "C55287"))
      (libsource (lib "eagle-import") (part "JC3H7C"))
    )
    (comp (ref "OK5")
      (value "JC3H7C")
      (footprint "eagle-import:MINI-FLAT-4")
      (fields (field (name "LCSCPART#") "C55287"))
      (libsource (lib "eagle-import") (part "JC3H7C"))
    )
    (comp (ref "OK6")
      (value "JC3H7C")
      (footprint "eagle-import:MINI-FLAT-4")
      (fields (field (name "LCSCPART#") "C55287"))
      (libsource (lib "eagle-import") (part "JC3H7C"))
    )
    (comp (ref "OK7")
      (value "JC3H7C")
      (footprint "eagle-import:MINI-FLAT-4")
      (fields (field (name "LCSCPART#") "C55287"))
      (libsource (lib "eagle-import") (part "JC3H7C"))
    )
    (comp (ref "OK8")
      (value "JC3H7C")
      (footprint "eagle-import:MINI-FLAT-4")
      (fields (field (name "LCSCPART#") "C55287"))
      (libsource (lib "eagle-import") (part "JC3H7C"))
    )
    (comp (ref "OK9")
      (value "JC3H7C")
      (footprint "eagle-import:MINI-FLAT-4")
      (fields (field (name "LCSCPART#") "C55287"))
      (libsource (lib "eagle-import") (part "JC3H7C"))
    )
    (comp (ref "OK10")
      (value "JC3H7C")
      (footprint "eagle-import:MINI-FLAT-4")
      (fields (field (name "LCSCPART#") "C55287"))
      (libsource (lib "eagle-import") (part "JC3H7C"))
    )
    (comp (ref "OK11")
      (value "JC3H7C")
      (footprint "eagle-import:MINI-FLAT-4")
      (fields (field (name "LCSCPART#") "C55287"))
      (libsource (lib "eagle-import") (part "JC3H7C"))
    )
    (comp (ref "OK12")
      (value "JC3H7C")
      (footprint "eagle-import:MINI-FLAT-4")
      (fields (field (name "LCSCPART#") "C55287"))
      (libsource (lib "eagle-import") (part "JC3H7C"))
    )
    (comp (ref "OK13")
      (value "JC3H7C")
      (footprint "eagle-import:MINI-FLAT-4")
      (fields (field (name "LCSCPART#") "C55287"))
      (libsource (lib "eagle-import") (part "JC3H7C"))
    )
    (comp (ref "OK14")
      (value "JC3H7C")
      (footprint "eagle-import:MINI-FLAT-4")
      (fields (field (name "LCSCPART#") "C55287"))
      (libsource (lib "eagle-import") (part "JC3H7C"))
    )
    (comp (ref "OK15")
      (value "JC3H7C")
      (footprint "eagle-import:MINI-FLAT-4")
      (fields (field (name "LCSCPART#") "C55287"))
      (libsource (lib "eagle-import") (part "JC3H7C"))
    )
    (comp (ref "OK16")
      (value "JC3H7C")
      (footprint "eagle-import:MINI-FLAT-4")
      (fields (field (name "LCSCPART#") "C55287"))
      (libsource (lib "eagle-import") (part "JC3H7C"))
    )
    (comp (ref "OK17")
      (value "JC3H7C")
      (footprint "eagle-import:MINI-FLAT-4")
      (fields (field (name "LCSCPART#") "C55287"))
      (libsource (lib "eagle-import") (part "JC3H7C"))
    )
    (comp (ref "OK18")
      (value "JC3H7C")
      (footprint "eagle-import:MINI-FLAT-4")
      (fields (field (name "LCSCPART#") "C55287"))
      (libsource (lib "eagle-import") (part "JC3H7C"))
    )
    (comp (ref "OK19")
      (value "JC3H7C")
      (footprint "eagle-import:MINI-FLAT-4")
      (fields (field (name "LCSCPART#") "C55287"))
      (libsource (lib "eagle-import") (part "JC3H7C"))
    )
    (comp (ref "OK20")
      (value "JC3H7C")
      (footprint "eagle-import:MINI-FLAT-4")
      (fields (field (name "LCSCPART#") "C55287"))
      (libsource (lib "eagle-import") (part "JC3H7C"))
    )
    (comp (ref "OK21")
      (value "JC3H7C")
      (footprint "eagle-import:MINI-FLAT-4")
      (fields (field (name "LCSCPART#") "C55287"))
      (libsource (lib "eagle-import") (part "JC3H7C"))
    )
    (comp (ref "OK22")
      (value "JC3H7C")
      (footprint "eagle-import:MINI-FLAT-4")
      (fields (field (name "LCSCPART#") "C55287"))
      (libsource (lib "eagle-import") (part "JC3H7C"))
    )
    (comp (ref "OK23")
      (value "JC3H7C")
      (footprint "eagle-import:MINI-FLAT-4")
      (fields (field (name "LCSCPART#") "C55287"))
      (libsource (lib "eagle-import") (part "JC3H7C"))
    )
    (comp (ref "OK24")
      (value "JC3H7C")
      (footprint "eagle-import:MINI-FLAT-4")
      (fields (field (name "LCSCPART#") "C55287"))
      (libsource (lib "eagle-import") (part "JC3H7C"))
    )
    (comp (ref "OK25")
      (value "JC3H7C")
      (footprint "eagle-import:MINI-FLAT-4")
      (fields (field (name "LCSCPART#") "C55287"))
      (libsource (lib "eagle-import") (part "JC3H7C"))
    )
    (comp (ref "OK26")
      (value "JC3H7C")
      (footprint "eagle-import:MINI-FLAT-4")
      (fields (field (name "LCSCPART#") "C55287"))
      (libsource (lib "eagle-import") (part "JC3H7C"))
    )
    (comp (ref "OK27")
      (value "JC3H7C")
      (footprint "eagle-import:MINI-FLAT-4")
      (fields (field (name "LCSCPART#") "C55287"))
      (libsource (lib "eagle-import") (part "JC3H7C"))
    )
    (comp (ref "OK28")
      (value "JC3H7C")
      (footprint "eagle-import:MINI-FLAT-4")
      (fields (field (name "LCSCPART#") "C55287"))
      (libsource (lib "eagle-import") (part "JC3H7C"))
    )
    (comp (ref "Q1")
      (value "25MHz")
      (footprint "eagle-import:3.2X2.5_KX-7")
      (libsource (lib "eagle-import") (part "KX-7"))
    )
    (comp (ref "Q2")
      (value "S9012")
      (footprint "eagle-import:SOT23")
      (libsource (lib "eagle-import") (part "PNP-TRANSISTOR_SOT23"))
    )
    (comp (ref "Q3")
      (value "8MHz")
      (footprint "eagle-import:5.0X3.2_2")
      (libsource (lib "eagle-import") (part "crystal-geyer_V1_0_203_KX-9B"))
    )
    (comp (ref "Q4")
      (value "32.768KHz")
      (footprint "eagle-import:3.2X1.5")
      (libsource (lib "eagle-import") (part "KX-327-NHT"))
    )
    (comp (ref "Q5")
      (value "12MHz")
      (footprint "eagle-import:3.2X2.5_KX-7")
      (libsource (lib "eagle-import") (part "KX-7"))
    )
    (comp (ref "R1")
      (value "6.2K")
      (footprint "eagle-import:R0603")
      (libsource (lib "eagle-import") (part "R-EU_R0603"))
    )
    (comp (ref "R2")
      (value "510R")
      (footprint "eagle-import:R0402")
      (libsource (lib "eagle-import") (part "R-EU_R0402"))
    )
    (comp (ref "R3")
      (value "390R")
      (footprint "eagle-import:R0603")
      (libsource (lib "eagle-import") (part "R-EU_R0603"))
    )
    (comp (ref "R4")
      (value "10K")
      (footprint "eagle-import:R0402")
      (libsource (lib "eagle-import") (part "R-EU_R0402"))
    )
    (comp (ref "R5")
      (value "680 Ohm")
      (footprint "eagle-import:R0402")
      (libsource (lib "eagle-import") (part "R-EU_R0402"))
    )
    (comp (ref "R6")
      (value "10K")
      (footprint "eagle-import:R0402")
      (libsource (lib "eagle-import") (part "R-EU_R0402"))
    )
    (comp (ref "R7")
      (value "3K")
      (footprint "eagle-import:R0805")
      (libsource (lib "eagle-import") (part "R-EU_R0805"))
    )
    (comp (ref "R8")
      (value "10K")
      (footprint "eagle-import:R0402")
      (libsource (lib "eagle-import") (part "R-EU_R0402"))
    )
    (comp (ref "R9")
      (value "100K")
      (footprint "eagle-import:R0402")
      (libsource (lib "eagle-import") (part "R-EU_R0402"))
    )
    (comp (ref "R10")
      (value "33R")
      (footprint "eagle-import:R0805")
      (libsource (lib "eagle-import") (part "R-EU_R0805"))
    )
    (comp (ref "R11")
      (value "100K")
      (footprint "eagle-import:R0402")
      (libsource (lib "eagle-import") (part "R-EU_R0402"))
    )
    (comp (ref "R12")
      (value "33R")
      (footprint "eagle-import:R0805")
      (libsource (lib "eagle-import") (part "R-EU_R0805"))
    )
    (comp (ref "R13")
      (value "1K")
      (footprint "eagle-import:R0402")
      (libsource (lib "eagle-import") (part "R-EU_R0402"))
    )
    (comp (ref "R14")
      (value "33R")
      (footprint "eagle-import:R0805")
      (libsource (lib "eagle-import") (part "R-EU_R0805"))
    )
    (comp (ref "R15")
      (value "680 Ohm")
      (footprint "eagle-import:R0402")
      (libsource (lib "eagle-import") (part "R-EU_R0402"))
    )
    (comp (ref "R16")
      (value "33R")
      (footprint "eagle-import:R0805")
      (libsource (lib "eagle-import") (part "R-EU_R0805"))
    )
    (comp (ref "R17")
      (value "3K")
      (footprint "eagle-import:R0805")
      (libsource (lib "eagle-import") (part "R-EU_R0805"))
    )
    (comp (ref "R18")
      (value "1K")
      (footprint "eagle-import:R0402")
      (libsource (lib "eagle-import") (part "R-EU_R0402"))
    )
    (comp (ref "R19")
      (value "680 Ohm")
      (footprint "eagle-import:R0402")
      (libsource (lib "eagle-import") (part "R-EU_R0402"))
    )
    (comp (ref "R20")
      (value "49R9")
      (footprint "eagle-import:R0805")
      (libsource (lib "eagle-import") (part "R-EU_R0805"))
    )
    (comp (ref "R21")
      (value "3K")
      (footprint "eagle-import:R0805")
      (libsource (lib "eagle-import") (part "R-EU_R0805"))
    )
    (comp (ref "R22")
      (value "49R9")
      (footprint "eagle-import:R0805")
      (libsource (lib "eagle-import") (part "R-EU_R0805"))
    )
    (comp (ref "R23")
      (value "1K")
      (footprint "eagle-import:R0402")
      (libsource (lib "eagle-import") (part "R-EU_R0402"))
    )
    (comp (ref "R24")
      (value "49R9")
      (footprint "eagle-import:R0805")
      (libsource (lib "eagle-import") (part "R-EU_R0805"))
    )
    (comp (ref "R25")
      (value "680 Ohm")
      (footprint "eagle-import:R0402")
      (libsource (lib "eagle-import") (part "R-EU_R0402"))
    )
    (comp (ref "R26")
      (value "330R")
      (footprint "eagle-import:R0402")
      (libsource (lib "eagle-import") (part "R-EU_R0402"))
    )
    (comp (ref "R27")
      (value "3K")
      (footprint "eagle-import:R0805")
      (libsource (lib "eagle-import") (part "R-EU_R0805"))
    )
    (comp (ref "R28")
      (value "330R")
      (footprint "eagle-import:R0402")
      (libsource (lib "eagle-import") (part "R-EU_R0402"))
    )
    (comp (ref "R29")
      (value "10K")
      (footprint "eagle-import:R0402")
      (libsource (lib "eagle-import") (part "R-EU_R0402"))
    )
    (comp (ref "R30")
      (value "6.2K")
      (footprint "eagle-import:R0603")
      (libsource (lib "eagle-import") (part "R-EU_R0603"))
    )
    (comp (ref "R31")
      (value "10K")
      (footprint "eagle-import:R0402")
      (libsource (lib "eagle-import") (part "R-EU_R0402"))
    )
    (comp (ref "R32")
      (value "680 Ohm")
      (footprint "eagle-import:R0402")
      (libsource (lib "eagle-import") (part "R-EU_R0402"))
    )
    (comp (ref "R33")
      (value "3K")
      (footprint "eagle-import:R0805")
      (libsource (lib "eagle-import") (part "R-EU_R0805"))
    )
    (comp (ref "R34")
      (value "49R9")
      (footprint "eagle-import:R0805")
      (libsource (lib "eagle-import") (part "R-EU_R0805"))
    )
    (comp (ref "R35")
      (value "680 Ohm")
      (footprint "eagle-import:R0402")
      (libsource (lib "eagle-import") (part "R-EU_R0402"))
    )
    (comp (ref "R36")
      (value "49R9")
      (footprint "eagle-import:R0805")
      (libsource (lib "eagle-import") (part "R-EU_R0805"))
    )
    (comp (ref "R37")
      (value "680 Ohm")
      (footprint "eagle-import:R0402")
      (libsource (lib "eagle-import") (part "R-EU_R0402"))
    )
    (comp (ref "R38")
      (value "3K")
      (footprint "eagle-import:R0805")
      (libsource (lib "eagle-import") (part "R-EU_R0805"))
    )
    (comp (ref "R39")
      (value "3K")
      (footprint "eagle-import:R0805")
      (libsource (lib "eagle-import") (part "R-EU_R0805"))
    )
    (comp (ref "R40")
      (value "680 Ohm")
      (footprint "eagle-import:R0402")
      (libsource (lib "eagle-import") (part "R-EU_R0402"))
    )
    (comp (ref "R41")
      (value "3K")
      (footprint "eagle-import:R0805")
      (libsource (lib "eagle-import") (part "R-EU_R0805"))
    )
    (comp (ref "R42")
      (value "100K")
      (footprint "eagle-import:R0402")
      (libsource (lib "eagle-import") (part "R-EU_R0402"))
    )
    (comp (ref "R43")
      (value "680 Ohm")
      (footprint "eagle-import:R0402")
      (libsource (lib "eagle-import") (part "R-EU_R0402"))
    )
    (comp (ref "R44")
      (value "3K")
      (footprint "eagle-import:R0805")
      (libsource (lib "eagle-import") (part "R-EU_R0805"))
    )
    (comp (ref "R45")
      (value "680 Ohm")
      (footprint "eagle-import:R0402")
      (libsource (lib "eagle-import") (part "R-EU_R0402"))
    )
    (comp (ref "R46")
      (value "680 Ohm")
      (footprint "eagle-import:R0402")
      (libsource (lib "eagle-import") (part "R-EU_R0402"))
    )
    (comp (ref "R47")
      (value "3K")
      (footprint "eagle-import:R0805")
      (libsource (lib "eagle-import") (part "R-EU_R0805"))
    )
    (comp (ref "R48")
      (value "3K")
      (footprint "eagle-import:R0805")
      (libsource (lib "eagle-import") (part "R-EU_R0805"))
    )
    (comp (ref "R49")
      (value "680 Ohm")
      (footprint "eagle-import:R0402")
      (libsource (lib "eagle-import") (part "R-EU_R0402"))
    )
    (comp (ref "R50")
      (value "3K")
      (footprint "eagle-import:R0805")
      (libsource (lib "eagle-import") (part "R-EU_R0805"))
    )
    (comp (ref "R51")
      (value "100K")
      (footprint "eagle-import:R0402")
      (libsource (lib "eagle-import") (part "R-EU_R0402"))
    )
    (comp (ref "R52")
      (value "1M")
      (footprint "eagle-import:R0402")
      (libsource (lib "eagle-import") (part "R-EU_R0402"))
    )
    (comp (ref "R53")
      (value "680 Ohm")
      (footprint "eagle-import:R0402")
      (libsource (lib "eagle-import") (part "R-EU_R0402"))
    )
    (comp (ref "R54")
      (value "3K")
      (footprint "eagle-import:R0805")
      (libsource (lib "eagle-import") (part "R-EU_R0805"))
    )
    (comp (ref "R55")
      (value "680 Ohm")
      (footprint "eagle-import:R0402")
      (libsource (lib "eagle-import") (part "R-EU_R0402"))
    )
    (comp (ref "R56")
      (value "680 Ohm")
      (footprint "eagle-import:R0402")
      (libsource (lib "eagle-import") (part "R-EU_R0402"))
    )
    (comp (ref "R57")
      (value "3K")
      (footprint "eagle-import:R0805")
      (libsource (lib "eagle-import") (part "R-EU_R0805"))
    )
    (comp (ref "R58")
      (value "3K")
      (footprint "eagle-import:R0805")
      (libsource (lib "eagle-import") (part "R-EU_R0805"))
    )
    (comp (ref "R59")
      (value "680 Ohm")
      (footprint "eagle-import:R0402")
      (libsource (lib "eagle-import") (part "R-EU_R0402"))
    )
    (comp (ref "R60")
      (value "3K")
      (footprint "eagle-import:R0805")
      (libsource (lib "eagle-import") (part "R-EU_R0805"))
    )
    (comp (ref "R61")
      (value "100K")
      (footprint "eagle-import:R0402")
      (libsource (lib "eagle-import") (part "R-EU_R0402"))
    )
    (comp (ref "R62")
      (value "680 Ohm")
      (footprint "eagle-import:R0402")
      (libsource (lib "eagle-import") (part "R-EU_R0402"))
    )
    (comp (ref "R63")
      (value "3K")
      (footprint "eagle-import:R0805")
      (libsource (lib "eagle-import") (part "R-EU_R0805"))
    )
    (comp (ref "R64")
      (value "680 Ohm")
      (footprint "eagle-import:R0402")
      (libsource (lib "eagle-import") (part "R-EU_R0402"))
    )
    (comp (ref "R65")
      (value "680 Ohm")
      (footprint "eagle-import:R0402")
      (libsource (lib "eagle-import") (part "R-EU_R0402"))
    )
    (comp (ref "R66")
      (value "3K")
      (footprint "eagle-import:R0805")
      (libsource (lib "eagle-import") (part "R-EU_R0805"))
    )
    (comp (ref "R67")
      (value "3K")
      (footprint "eagle-import:R0805")
      (libsource (lib "eagle-import") (part "R-EU_R0805"))
    )
    (comp (ref "R68")
      (value "680 Ohm")
      (footprint "eagle-import:R0402")
      (libsource (lib "eagle-import") (part "R-EU_R0402"))
    )
    (comp (ref "R69")
      (value "3K")
      (footprint "eagle-import:R0805")
      (libsource (lib "eagle-import") (part "R-EU_R0805"))
    )
    (comp (ref "R70")
      (value "100K")
      (footprint "eagle-import:R0402")
      (libsource (lib "eagle-import") (part "R-EU_R0402"))
    )
    (comp (ref "R71")
      (value "680 Ohm")
      (footprint "eagle-import:R0402")
      (libsource (lib "eagle-import") (part "R-EU_R0402"))
    )
    (comp (ref "R72")
      (value "3K")
      (footprint "eagle-import:R0805")
      (libsource (lib "eagle-import") (part "R-EU_R0805"))
    )
    (comp (ref "R73")
      (value "6.8K")
      (footprint "eagle-import:R0402")
      (libsource (lib "eagle-import") (part "R-EU_R0402"))
    )
    (comp (ref "R74")
      (value "680 Ohm")
      (footprint "eagle-import:R0402")
      (libsource (lib "eagle-import") (part "R-EU_R0402"))
    )
    (comp (ref "R75")
      (value "3K")
      (footprint "eagle-import:R0805")
      (libsource (lib "eagle-import") (part "R-EU_R0805"))
    )
    (comp (ref "R76")
      (value "6.8K")
      (footprint "eagle-import:R0402")
      (libsource (lib "eagle-import") (part "R-EU_R0402"))
    )
    (comp (ref "R77")
      (value "680 Ohm")
      (footprint "eagle-import:R0402")
      (libsource (lib "eagle-import") (part "R-EU_R0402"))
    )
    (comp (ref "R78")
      (value "3K")
      (footprint "eagle-import:R0805")
      (libsource (lib "eagle-import") (part "R-EU_R0805"))
    )
    (comp (ref "R79")
      (value "6.8K")
      (footprint "eagle-import:R0402")
      (libsource (lib "eagle-import") (part "R-EU_R0402"))
    )
    (comp (ref "R80")
      (value "680 Ohm")
      (footprint "eagle-import:R0402")
      (libsource (lib "eagle-import") (part "R-EU_R0402"))
    )
    (comp (ref "R81")
      (value "3K")
      (footprint "eagle-import:R0805")
      (libsource (lib "eagle-import") (part "R-EU_R0805"))
    )
    (comp (ref "R82")
      (value "6.8K")
      (footprint "eagle-import:R0402")
      (libsource (lib "eagle-import") (part "R-EU_R0402"))
    )
    (comp (ref "R83")
      (value "680 Ohm")
      (footprint "eagle-import:R0402")
      (libsource (lib "eagle-import") (part "R-EU_R0402"))
    )
    (comp (ref "R84")
      (value "3K")
      (footprint "eagle-import:R0805")
      (libsource (lib "eagle-import") (part "R-EU_R0805"))
    )
    (comp (ref "R85")
      (value "6.8K")
      (footprint "eagle-import:R0402")
      (libsource (lib "eagle-import") (part "R-EU_R0402"))
    )
    (comp (ref "R86")
      (value "680 Ohm")
      (footprint "eagle-import:R0402")
      (libsource (lib "eagle-import") (part "R-EU_R0402"))
    )
    (comp (ref "R87")
      (value "3K")
      (footprint "eagle-import:R0805")
      (libsource (lib "eagle-import") (part "R-EU_R0805"))
    )
    (comp (ref "R88")
      (value "6.8K")
      (footprint "eagle-import:R0402")
      (libsource (lib "eagle-import") (part "R-EU_R0402"))
    )
    (comp (ref "R89")
      (value "680 Ohm")
      (footprint "eagle-import:R0402")
      (libsource (lib "eagle-import") (part "R-EU_R0402"))
    )
    (comp (ref "R90")
      (value "3K")
      (footprint "eagle-import:R0805")
      (libsource (lib "eagle-import") (part "R-EU_R0805"))
    )
    (comp (ref "R91")
      (value "6.8K")
      (footprint "eagle-import:R0402")
      (libsource (lib "eagle-import") (part "R-EU_R0402"))
    )
    (comp (ref "R92")
      (value "680 Ohm")
      (footprint "eagle-import:R0402")
      (libsource (lib "eagle-import") (part "R-EU_R0402"))
    )
    (comp (ref "R93")
      (value "3K")
      (footprint "eagle-import:R0805")
      (libsource (lib "eagle-import") (part "R-EU_R0805"))
    )
    (comp (ref "R94")
      (value "6.8K")
      (footprint "eagle-import:R0402")
      (libsource (lib "eagle-import") (part "R-EU_R0402"))
    )
    (comp (ref "R95")
      (value "100K")
      (footprint "eagle-import:R0402")
      (libsource (lib "eagle-import") (part "R-EU_R0402"))
    )
    (comp (ref "R96")
      (value "100K")
      (footprint "eagle-import:R0402")
      (libsource (lib "eagle-import") (part "R-EU_R0402"))
    )
    (comp (ref "R97")
      (value "100K")
      (footprint "eagle-import:R0402")
      (libsource (lib "eagle-import") (part "R-EU_R0402"))
    )
    (comp (ref "R98")
      (value "100K")
      (footprint "eagle-import:R0402")
      (libsource (lib "eagle-import") (part "R-EU_R0402"))
    )
    (comp (ref "R99")
      (value "100K")
      (footprint "eagle-import:R0402")
      (libsource (lib "eagle-import") (part "R-EU_R0402"))
    )
    (comp (ref "R100")
      (value "100K")
      (footprint "eagle-import:R0402")
      (libsource (lib "eagle-import") (part "R-EU_R0402"))
    )
    (comp (ref "R101")
      (value "100K")
      (footprint "eagle-import:R0402")
      (libsource (lib "eagle-import") (part "R-EU_R0402"))
    )
    (comp (ref "R102")
      (value "100K")
      (footprint "eagle-import:R0402")
      (libsource (lib "eagle-import") (part "R-EU_R0402"))
    )
    (comp (ref "R103")
      (value "100K")
      (footprint "eagle-import:R0402")
      (libsource (lib "eagle-import") (part "R-EU_R0402"))
    )
    (comp (ref "R104")
      (value "100K")
      (footprint "eagle-import:R0402")
      (libsource (lib "eagle-import") (part "R-EU_R0402"))
    )
    (comp (ref "R105")
      (value "100K")
      (footprint "eagle-import:R0402")
      (libsource (lib "eagle-import") (part "R-EU_R0402"))
    )
    (comp (ref "R106")
      (value "100K")
      (footprint "eagle-import:R0402")
      (libsource (lib "eagle-import") (part "R-EU_R0402"))
    )
    (comp (ref "R107")
      (value "100K")
      (footprint "eagle-import:R0402")
      (libsource (lib "eagle-import") (part "R-EU_R0402"))
    )
    (comp (ref "R108")
      (value "100K")
      (footprint "eagle-import:R0402")
      (libsource (lib "eagle-import") (part "R-EU_R0402"))
    )
    (comp (ref "R109")
      (value "100K")
      (footprint "eagle-import:R0402")
      (libsource (lib "eagle-import") (part "R-EU_R0402"))
    )
    (comp (ref "R110")
      (value "100K")
      (footprint "eagle-import:R0402")
      (libsource (lib "eagle-import") (part "R-EU_R0402"))
    )
    (comp (ref "R111")
      (value "100K")
      (footprint "eagle-import:R0402")
      (libsource (lib "eagle-import") (part "R-EU_R0402"))
    )
    (comp (ref "R112")
      (value "100K")
      (footprint "eagle-import:R0402")
      (libsource (lib "eagle-import") (part "R-EU_R0402"))
    )
    (comp (ref "R113")
      (value "100K")
      (footprint "eagle-import:R0402")
      (libsource (lib "eagle-import") (part "R-EU_R0402"))
    )
    (comp (ref "R114")
      (value "100K")
      (footprint "eagle-import:R0402")
      (libsource (lib "eagle-import") (part "R-EU_R0402"))
    )
    (comp (ref "R115")
      (value "100K")
      (footprint "eagle-import:R0402")
      (libsource (lib "eagle-import") (part "R-EU_R0402"))
    )
    (comp (ref "R116")
      (value "100K")
      (footprint "eagle-import:R0402")
      (libsource (lib "eagle-import") (part "R-EU_R0402"))
    )
    (comp (ref "R117")
      (value "100K")
      (footprint "eagle-import:R0402")
      (libsource (lib "eagle-import") (part "R-EU_R0402"))
    )
    (comp (ref "R118")
      (value "100K")
      (footprint "eagle-import:R0402")
      (libsource (lib "eagle-import") (part "R-EU_R0402"))
    )
    (comp (ref "R119")
      (value "6.8K")
      (footprint "eagle-import:R0402")
      (libsource (lib "eagle-import") (part "R-EU_R0402"))
    )
    (comp (ref "R120")
      (value "6.8K")
      (footprint "eagle-import:R0402")
      (libsource (lib "eagle-import") (part "R-EU_R0402"))
    )
    (comp (ref "R121")
      (value "6.8K")
      (footprint "eagle-import:R0402")
      (libsource (lib "eagle-import") (part "R-EU_R0402"))
    )
    (comp (ref "R122")
      (value "6.8K")
      (footprint "eagle-import:R0402")
      (libsource (lib "eagle-import") (part "R-EU_R0402"))
    )
    (comp (ref "R123")
      (value "6.8K")
      (footprint "eagle-import:R0402")
      (libsource (lib "eagle-import") (part "R-EU_R0402"))
    )
    (comp (ref "R124")
      (value "6.8K")
      (footprint "eagle-import:R0402")
      (libsource (lib "eagle-import") (part "R-EU_R0402"))
    )
    (comp (ref "R125")
      (value "6.8K")
      (footprint "eagle-import:R0402")
      (libsource (lib "eagle-import") (part "R-EU_R0402"))
    )
    (comp (ref "R126")
      (value "6.8K")
      (footprint "eagle-import:R0402")
      (libsource (lib "eagle-import") (part "R-EU_R0402"))
    )
    (comp (ref "R127")
      (value "6.8K")
      (footprint "eagle-import:R0402")
      (libsource (lib "eagle-import") (part "R-EU_R0402"))
    )
    (comp (ref "R128")
      (value "6.8K")
      (footprint "eagle-import:R0402")
      (libsource (lib "eagle-import") (part "R-EU_R0402"))
    )
    (comp (ref "R129")
      (value "6.8K")
      (footprint "eagle-import:R0402")
      (libsource (lib "eagle-import") (part "R-EU_R0402"))
    )
    (comp (ref "R130")
      (value "6.8K")
      (footprint "eagle-import:R0402")
      (libsource (lib "eagle-import") (part "R-EU_R0402"))
    )
    (comp (ref "R131")
      (value "6.8K")
      (footprint "eagle-import:R0402")
      (libsource (lib "eagle-import") (part "R-EU_R0402"))
    )
    (comp (ref "R132")
      (value "6.8K")
      (footprint "eagle-import:R0402")
      (libsource (lib "eagle-import") (part "R-EU_R0402"))
    )
    (comp (ref "R133")
      (value "6.8K")
      (footprint "eagle-import:R0402")
      (libsource (lib "eagle-import") (part "R-EU_R0402"))
    )
    (comp (ref "R134")
      (value "6.8K")
      (footprint "eagle-import:R0402")
      (libsource (lib "eagle-import") (part "R-EU_R0402"))
    )
    (comp (ref "R135")
      (value "6.8K")
      (footprint "eagle-import:R0402")
      (libsource (lib "eagle-import") (part "R-EU_R0402"))
    )
    (comp (ref "R136")
      (value "6.8K")
      (footprint "eagle-import:R0402")
      (libsource (lib "eagle-import") (part "R-EU_R0402"))
    )
    (comp (ref "R137")
      (value "6.8K")
      (footprint "eagle-import:R0402")
      (libsource (lib "eagle-import") (part "R-EU_R0402"))
    )
    (comp (ref "R138")
      (value "6.8K")
      (footprint "eagle-import:R0402")
      (libsource (lib "eagle-import") (part "R-EU_R0402"))
    )
    (comp (ref "RN1")
      (value "10K")
      (footprint "eagle-import:4X0402ARV341")
      (libsource (lib "eagle-import") (part "4R-N0402ARV341"))
    )
    (comp (ref "RN2")
      (value "10K")
      (footprint "eagle-import:4X0402ARV341")
      (libsource (lib "eagle-import") (part "4R-N0402ARV341"))
    )
    (comp (ref "S2")
      (value "DTSM-3")
      (footprint "eagle-import:DTSM-3")
      (libsource (lib "eagle-import") (part "DTSM-3"))
    )
    (comp (ref "U$1")
      (value "CH340G")
      (footprint "eagle-import:SOIC16")
      (libsource (lib "eagle-import") (part "CH340G"))
    )
    (comp (ref "U$2")
      (value "DC-DC-STEP-DOWN-MP1584")
      (footprint "eagle-import:DC-DC-STEP-DOWN-MP1584")
      (libsource (lib "eagle-import") (part "DC-DC-STEP-DOWN-MP1584"))
    )
    (comp (ref "U1")
      (value "S9013")
      (footprint "eagle-import:SOT-23-3")
      (fields
        (field (name "HOUSEPART") "YES")
        (field (name "MPN") "MF-DSC-SOT233-MMBT3904")
        (field (name "MPN_1") "MF-DSC-SOT233-MMBT5551")
      )
      (libsource (lib "eagle-import") (part "NPN_BJT_SOT-23-3MMBT3904"))
    )
    (comp (ref "U2")
      (value "W5500")
      (footprint "eagle-import:W5500")
      (libsource (lib "eagle-import") (part "W5500"))
    )
    (comp (ref "U3")
      (value "NPN BJT S9013")
      (footprint "eagle-import:SOT-23-3")
      (fields (field (name "HOUSEPART") "YES") (field (name "MPN") "MF-DSC-SOT233-MMBT3904"))
      (libsource (lib "eagle-import") (part "NPN_BJT_SOT-23-3MMBT3904"))
    )
    (comp (ref "U4")
      (value "NPN BJT S9013")
      (footprint "eagle-import:SOT-23-3")
      (fields (field (name "HOUSEPART") "YES") (field (name "MPN") "MF-DSC-SOT233-MMBT3904"))
      (libsource (lib "eagle-import") (part "NPN_BJT_SOT-23-3MMBT3904"))
    )
    (comp (ref "U5")
      (value "NPN BJT S9013")
      (footprint "eagle-import:SOT-23-3")
      (fields (field (name "HOUSEPART") "YES") (field (name "MPN") "MF-DSC-SOT233-MMBT3904"))
      (libsource (lib "eagle-import") (part "NPN_BJT_SOT-23-3MMBT3904"))
    )
    (comp (ref "U6")
      (value "NPN BJT S9013")
      (footprint "eagle-import:SOT-23-3")
      (fields (field (name "HOUSEPART") "YES") (field (name "MPN") "MF-DSC-SOT233-MMBT3904"))
      (libsource (lib "eagle-import") (part "NPN_BJT_SOT-23-3MMBT3904"))
    )
    (comp (ref "U7")
      (value "NPN BJT S9013")
      (footprint "eagle-import:SOT-23-3")
      (fields (field (name "HOUSEPART") "YES") (field (name "MPN") "MF-DSC-SOT233-MMBT3904"))
      (libsource (lib "eagle-import") (part "NPN_BJT_SOT-23-3MMBT3904"))
    )
    (comp (ref "U8")
      (value "NPN BJT S9013")
      (footprint "eagle-import:SOT-23-3")
      (fields (field (name "HOUSEPART") "YES") (field (name "MPN") "MF-DSC-SOT233-MMBT3904"))
      (libsource (lib "eagle-import") (part "NPN_BJT_SOT-23-3MMBT3904"))
    )
    (comp (ref "U9")
      (value "NPN BJT S9013")
      (footprint "eagle-import:SOT-23-3")
      (fields (field (name "HOUSEPART") "YES") (field (name "MPN") "MF-DSC-SOT233-MMBT3904"))
      (libsource (lib "eagle-import") (part "NPN_BJT_SOT-23-3MMBT3904"))
    )
    (comp (ref "U10")
      (value "NPN BJT S9013")
      (footprint "eagle-import:SOT-23-3")
      (fields (field (name "HOUSEPART") "YES") (field (name "MPN") "MF-DSC-SOT233-MMBT3904"))
      (libsource (lib "eagle-import") (part "NPN_BJT_SOT-23-3MMBT3904"))
    )
    (comp (ref "U11")
      (value "NPN BJT S9013")
      (footprint "eagle-import:SOT-23-3")
      (fields (field (name "HOUSEPART") "YES") (field (name "MPN") "MF-DSC-SOT233-MMBT3904"))
      (libsource (lib "eagle-import") (part "NPN_BJT_SOT-23-3MMBT3904"))
    )
    (comp (ref "U12")
      (value "NPN BJT S9013")
      (footprint "eagle-import:SOT-23-3")
      (fields (field (name "HOUSEPART") "YES") (field (name "MPN") "MF-DSC-SOT233-MMBT3904"))
      (libsource (lib "eagle-import") (part "NPN_BJT_SOT-23-3MMBT3904"))
    )
    (comp (ref "U13")
      (value "NPN BJT S9013")
      (footprint "eagle-import:SOT-23-3")
      (fields (field (name "HOUSEPART") "YES") (field (name "MPN") "MF-DSC-SOT233-MMBT3904"))
      (libsource (lib "eagle-import") (part "NPN_BJT_SOT-23-3MMBT3904"))
    )
    (comp (ref "U14")
      (value "NPN BJT S9013")
      (footprint "eagle-import:SOT-23-3")
      (fields (field (name "HOUSEPART") "YES") (field (name "MPN") "MF-DSC-SOT233-MMBT3904"))
      (libsource (lib "eagle-import") (part "NPN_BJT_SOT-23-3MMBT3904"))
    )
    (comp (ref "U15")
      (value "NPN BJT S9013")
      (footprint "eagle-import:SOT-23-3")
      (fields (field (name "HOUSEPART") "YES") (field (name "MPN") "MF-DSC-SOT233-MMBT3904"))
      (libsource (lib "eagle-import") (part "NPN_BJT_SOT-23-3MMBT3904"))
    )
    (comp (ref "U16")
      (value "NPN BJT S9013")
      (footprint "eagle-import:SOT-23-3")
      (fields (field (name "HOUSEPART") "YES") (field (name "MPN") "MF-DSC-SOT233-MMBT3904"))
      (libsource (lib "eagle-import") (part "NPN_BJT_SOT-23-3MMBT3904"))
    )
    (comp (ref "U17")
      (value "NPN BJT S9013")
      (footprint "eagle-import:SOT-23-3")
      (fields (field (name "HOUSEPART") "YES") (field (name "MPN") "MF-DSC-SOT233-MMBT3904"))
      (libsource (lib "eagle-import") (part "NPN_BJT_SOT-23-3MMBT3904"))
    )
    (comp (ref "U18")
      (value "NPN BJT S9013")
      (footprint "eagle-import:SOT-23-3")
      (fields (field (name "HOUSEPART") "YES") (field (name "MPN") "MF-DSC-SOT233-MMBT3904"))
      (libsource (lib "eagle-import") (part "NPN_BJT_SOT-23-3MMBT3904"))
    )
    (comp (ref "U19")
      (value "NPN BJT S9013")
      (footprint "eagle-import:SOT-23-3")
      (fields (field (name "HOUSEPART") "YES") (field (name "MPN") "MF-DSC-SOT233-MMBT3904"))
      (libsource (lib "eagle-import") (part "NPN_BJT_SOT-23-3MMBT3904"))
    )
    (comp (ref "U20")
      (value "NPN BJT S9013")
      (footprint "eagle-import:SOT-23-3")
      (fields (field (name "HOUSEPART") "YES") (field (name "MPN") "MF-DSC-SOT233-MMBT3904"))
      (libsource (lib "eagle-import") (part "NPN_BJT_SOT-23-3MMBT3904"))
    )
    (comp (ref "U21")
      (value "NPN BJT S9013")
      (footprint "eagle-import:SOT-23-3")
      (fields (field (name "HOUSEPART") "YES") (field (name "MPN") "MF-DSC-SOT233-MMBT3904"))
      (libsource (lib "eagle-import") (part "NPN_BJT_SOT-23-3MMBT3904"))
    )
    (comp (ref "U22")
      (value "NPN BJT S9013")
      (footprint "eagle-import:SOT-23-3")
      (fields (field (name "HOUSEPART") "YES") (field (name "MPN") "MF-DSC-SOT233-MMBT3904"))
      (libsource (lib "eagle-import") (part "NPN_BJT_SOT-23-3MMBT3904"))
    )
    (comp (ref "U23")
      (value "NPN BJT S9013")
      (footprint "eagle-import:SOT-23-3")
      (fields (field (name "HOUSEPART") "YES") (field (name "MPN") "MF-DSC-SOT233-MMBT3904"))
      (libsource (lib "eagle-import") (part "NPN_BJT_SOT-23-3MMBT3904"))
    )
    (comp (ref "U24")
      (value "NPN BJT S9013")
      (footprint "eagle-import:SOT-23-3")
      (fields (field (name "HOUSEPART") "YES") (field (name "MPN") "MF-DSC-SOT233-MMBT3904"))
      (libsource (lib "eagle-import") (part "NPN_BJT_SOT-23-3MMBT3904"))
    )
    (comp (ref "U25")
      (value "NPN BJT S9013")
      (footprint "eagle-import:SOT-23-3")
      (fields (field (name "HOUSEPART") "YES") (field (name "MPN") "MF-DSC-SOT233-MMBT3904"))
      (libsource (lib "eagle-import") (part "NPN_BJT_SOT-23-3MMBT3904"))
    )
    (comp (ref "U26")
      (value "NPN BJT S9013")
      (footprint "eagle-import:SOT-23-3")
      (fields (field (name "HOUSEPART") "YES") (field (name "MPN") "MF-DSC-SOT233-MMBT3904"))
      (libsource (lib "eagle-import") (part "NPN_BJT_SOT-23-3MMBT3904"))
    )
    (comp (ref "U27")
      (value "NPN BJT S9013")
      (footprint "eagle-import:SOT-23-3")
      (fields (field (name "HOUSEPART") "YES") (field (name "MPN") "MF-DSC-SOT233-MMBT3904"))
      (libsource (lib "eagle-import") (part "NPN_BJT_SOT-23-3MMBT3904"))
    )
    (comp (ref "U28")
      (value "NPN BJT S9013")
      (footprint "eagle-import:SOT-23-3")
      (fields (field (name "HOUSEPART") "YES") (field (name "MPN") "MF-DSC-SOT233-MMBT3904"))
      (libsource (lib "eagle-import") (part "NPN_BJT_SOT-23-3MMBT3904"))
    )
    (comp (ref "U29")
      (value "NPN BJT S9013")
      (footprint "eagle-import:SOT-23-3")
      (fields (field (name "HOUSEPART") "YES") (field (name "MPN") "MF-DSC-SOT233-MMBT3904"))
      (libsource (lib "eagle-import") (part "NPN_BJT_SOT-23-3MMBT3904"))
    )
    (comp (ref "U30")
      (value "NPN BJT S9013")
      (footprint "eagle-import:SOT-23-3")
      (fields (field (name "HOUSEPART") "YES") (field (name "MPN") "MF-DSC-SOT233-MMBT3904"))
      (libsource (lib "eagle-import") (part "NPN_BJT_SOT-23-3MMBT3904"))
    )
    (comp (ref "X1")
      (value "TERMINAL-BLOCK-3.5MM-8-PIN-LONG-PAD")
      (footprint "eagle-import:TERMINAL-BLOCK-8-PIN-3.5MM-LONG-PAD")
      (libsource (lib "eagle-import") (part "TERMINAL-BLOCK-3.5MM-8-PIN-LONG-PAD"))
    )
    (comp (ref "X2")
      (value "TERMINAL-BLOCK-3.5MM-9-PIN-LONG-PAD")
      (footprint "eagle-import:TERMINAL-BLOCK-9-PIN-3.5MM-LONG-PAD")
      (libsource (lib "eagle-import") (part "TERMINAL-BLOCK-3.5MM-9-PIN-LONG-PAD"))
    )
    (comp (ref "X4")
      (value "TERMINAL-BLOCK-3.5MM-4-PIN-LONG-PAD")
      (footprint "eagle-import:TERMINAL-BLOCK-4-PIN-3.5MM-LONG-PAD")
      (libsource (lib "eagle-import") (part "TERMINAL-BLOCK-3.5MM-4-PIN-LONG-PAD"))
    )
    (comp (ref "X5")
      (value "TERMINAL-BLOCK-3.5MM-4-PIN-LONG-PAD")
      (footprint "eagle-import:TERMINAL-BLOCK-4-PIN-3.5MM-LONG-PAD")
      (libsource (lib "eagle-import") (part "TERMINAL-BLOCK-3.5MM-4-PIN-LONG-PAD"))
    )
    (comp (ref "X7")
      (value "TERMINAL-BLOCK-3.5MM-8-PIN-LONG-PAD")
      (footprint "eagle-import:TERMINAL-BLOCK-8-PIN-3.5MM-LONG-PAD")
      (libsource (lib "eagle-import") (part "TERMINAL-BLOCK-3.5MM-8-PIN-LONG-PAD"))
    )
    (comp (ref "X8")
      (value "TERMINAL-BLOCK-3.5MM-8-PIN-LONG-PAD")
      (footprint "eagle-import:TERMINAL-BLOCK-8-PIN-3.5MM-LONG-PAD")
      (libsource (lib "eagle-import") (part "TERMINAL-BLOCK-3.5MM-8-PIN-LONG-PAD"))
    )
  )
  (nets
    (net (code "1") (name "+3V3") (class "Default")
      (node (ref "C1") (pin "1") (pinfunction "1_1") (pintype "passive"))
      (node (ref "C22") (pin "1") (pinfunction "1_1") (pintype "passive"))
      (node (ref "C24") (pin "1") (pinfunction "1_1") (pintype "passive"))
      (node (ref "C25") (pin "1") (pinfunction "1_1") (pintype "passive"))
      (node (ref "C26") (pin "1") (pinfunction "1_1") (pintype "passive"))
      (node (ref "C27") (pin "1") (pinfunction "1_1") (pintype "passive"))
      (node (ref "IC2") (pin "100") (pinfunction "VDD_100") (pintype "power_in"))
      (node (ref "IC2") (pin "11") (pinfunction "VDD_11") (pintype "power_in"))
      (node (ref "IC2") (pin "22") (pinfunction "VDDA_22") (pintype "power_in"))
      (node (ref "IC2") (pin "28") (pinfunction "VDD_28") (pintype "power_in"))
      (node (ref "IC2") (pin "50") (pinfunction "VDD_50") (pintype "power_in"))
      (node (ref "IC2") (pin "6") (pinfunction "VBAT_6") (pintype "power_in"))
      (node (ref "IC2") (pin "75") (pinfunction "VDD_75") (pintype "power_in"))
      (node (ref "J2") (pin "G+") (pinfunction "G+_G+") (pintype "bidirectional"))
      (node (ref "J2") (pin "Y+") (pinfunction "Y+_Y+") (pintype "bidirectional"))
      (node (ref "JP1") (pin "11") (pinfunction "11_11") (pintype "passive"))
      (node (ref "JP1") (pin "20") (pinfunction "20_20") (pintype "passive"))
      (node (ref "JP1") (pin "27") (pinfunction "27_27") (pintype "passive"))
      (node (ref "L1") (pin "2") (pinfunction "2_2") (pintype "passive"))
      (node (ref "Q2") (pin "2") (pinfunction "E_2") (pintype "passive"))
      (node (ref "R29") (pin "2") (pinfunction "2_2") (pintype "passive"))
      (node (ref "R31") (pin "2") (pinfunction "2_2") (pintype "passive"))
      (node (ref "R4") (pin "1") (pinfunction "1_1") (pintype "passive"))
      (node (ref "R6") (pin "1") (pinfunction "1_1") (pintype "passive"))
      (node (ref "R8") (pin "1") (pinfunction "1_1") (pintype "passive"))
      (node (ref "RN1") (pin "6") (pinfunction "2_6") (pintype "passive"))
      (node (ref "RN1") (pin "7") (pinfunction "2_7") (pintype "passive"))
      (node (ref "RN1") (pin "8") (pinfunction "2_8") (pintype "passive"))
      (node (ref "U$2") (pin "OUT+.1") (pinfunction "OUT+.1_OUT+.1") (pintype "bidirectional"))
      (node (ref "U$2") (pin "OUT+.2") (pinfunction "OUT+.2_OUT+.2") (pintype "bidirectional"))
      (node (ref "U2") (pin "28") (pinfunction "VDD_28") (pintype "passive"))
    )
    (net (code "2") (name "+3V3A") (class "Default")
      (node (ref "C15") (pin "1") (pinfunction "1_1") (pintype "passive"))
      (node (ref "C20") (pin "1") (pinfunction "1_1") (pintype "passive"))
      (node (ref "C23") (pin "1") (pinfunction "1_1") (pintype "passive"))
      (node (ref "C3") (pin "1") (pinfunction "1_1") (pintype "passive"))
      (node (ref "C4") (pin "1") (pinfunction "1_1") (pintype "passive"))
      (node (ref "C5") (pin "1") (pinfunction "1_1") (pintype "passive"))
      (node (ref "C6") (pin "1") (pinfunction "1_1") (pintype "passive"))
      (node (ref "L1") (pin "1") (pinfunction "1_1") (pintype "passive"))
      (node (ref "R20") (pin "2") (pinfunction "2_2") (pintype "passive"))
      (node (ref "R22") (pin "2") (pinfunction "2_2") (pintype "passive"))
      (node (ref "R24") (pin "2") (pinfunction "2_2") (pintype "passive"))
      (node (ref "U2") (pin "11") (pinfunction "AVDD_11") (pintype "passive"))
      (node (ref "U2") (pin "15") (pinfunction "AVDD_15") (pintype "passive"))
      (node (ref "U2") (pin "17") (pinfunction "AVDD_17") (pintype "passive"))
      (node (ref "U2") (pin "21") (pinfunction "AVDD_21") (pintype "passive"))
      (node (ref "U2") (pin "4") (pinfunction "AVDD_4") (pintype "passive"))
      (node (ref "U2") (pin "8") (pinfunction "AVDD_8") (pintype "passive"))
    )
    (net (code "3") (name "+24V") (class "Default")
      (node (ref "C11") (pin "1") (pinfunction "1_1") (pintype "passive"))
      (node (ref "C30") (pin "1") (pinfunction "1_1") (pintype "passive"))
      (node (ref "C31") (pin "1") (pinfunction "1_1") (pintype "passive"))
      (node (ref "C32") (pin "1") (pinfunction "1_1") (pintype "passive"))
      (node (ref "C33") (pin "1") (pinfunction "1_1") (pintype "passive"))
      (node (ref "C34") (pin "1") (pinfunction "1_1") (pintype "passive"))
      (node (ref "C35") (pin "1") (pinfunction "1_1") (pintype "passive"))
      (node (ref "C36") (pin "1") (pinfunction "1_1") (pintype "passive"))
      (node (ref "C37") (pin "1") (pinfunction "1_1") (pintype "passive"))
      (node (ref "C38") (pin "1") (pinfunction "1_1") (pintype "passive"))
      (node (ref "C39") (pin "1") (pinfunction "1_1") (pintype "passive"))
      (node (ref "C40") (pin "1") (pinfunction "1_1") (pintype "passive"))
      (node (ref "C41") (pin "1") (pinfunction "1_1") (pintype "passive"))
      (node (ref "C42") (pin "1") (pinfunction "1_1") (pintype "passive"))
      (node (ref "C43") (pin "1") (pinfunction "1_1") (pintype "passive"))
      (node (ref "C49") (pin "1") (pinfunction "1_1") (pintype "passive"))
      (node (ref "C50") (pin "1") (pinfunction "1_1") (pintype "passive"))
      (node (ref "C51") (pin "1") (pinfunction "1_1") (pintype "passive"))
      (node (ref "C52") (pin "1") (pinfunction "1_1") (pintype "passive"))
      (node (ref "C53") (pin "1") (pinfunction "1_1") (pintype "passive"))
      (node (ref "C54") (pin "1") (pinfunction "1_1") (pintype "passive"))
      (node (ref "C55") (pin "1") (pinfunction "1_1") (pintype "passive"))
      (node (ref "C56") (pin "1") (pinfunction "1_1") (pintype "passive"))
      (node (ref "C57") (pin "1") (pinfunction "1_1") (pintype "passive"))
      (node (ref "C58") (pin "1") (pinfunction "1_1") (pintype "passive"))
      (node (ref "C59") (pin "1") (pinfunction "1_1") (pintype "passive"))
      (node (ref "C60") (pin "1") (pinfunction "1_1") (pintype "passive"))
      (node (ref "C61") (pin "1") (pinfunction "1_1") (pintype "passive"))
      (node (ref "C62") (pin "1") (pinfunction "1_1") (pintype "passive"))
      (node (ref "C7") (pin "1") (pinfunction "1_1") (pintype "passive"))
      (node (ref "D1") (pin "C") (pinfunction "C_C") (pintype "passive"))
      (node (ref "D10") (pin "C") (pinfunction "C_C") (pintype "passive"))
      (node (ref "D11") (pin "C") (pinfunction "C_C") (pintype "passive"))
      (node (ref "D12") (pin "C") (pinfunction "C_C") (pintype "passive"))
      (node (ref "D13") (pin "C") (pinfunction "C_C") (pintype "passive"))
      (node (ref "D14") (pin "C") (pinfunction "C_C") (pintype "passive"))
      (node (ref "D15") (pin "C") (pinfunction "C_C") (pintype "passive"))
      (node (ref "D16") (pin "C") (pinfunction "C_C") (pintype "passive"))
      (node (ref "D17") (pin "C") (pinfunction "C_C") (pintype "passive"))
      (node (ref "D18") (pin "C") (pinfunction "C_C") (pintype "passive"))
      (node (ref "D19") (pin "C") (pinfunction "C_C") (pintype "passive"))
      (node (ref "D2") (pin "C") (pinfunction "C_C") (pintype "passive"))
      (node (ref "D20") (pin "C") (pinfunction "C_C") (pintype "passive"))
      (node (ref "D21") (pin "C") (pinfunction "C_C") (pintype "passive"))
      (node (ref "D22") (pin "C") (pinfunction "C_C") (pintype "passive"))
      (node (ref "D23") (pin "C") (pinfunction "C_C") (pintype "passive"))
      (node (ref "D24") (pin "C") (pinfunction "C_C") (pintype "passive"))
      (node (ref "D25") (pin "A") (pinfunction "A_A") (pintype "passive"))
      (node (ref "D27") (pin "C") (pinfunction "C_C") (pintype "passive"))
      (node (ref "D28") (pin "C") (pinfunction "C_C") (pintype "passive"))
      (node (ref "D29") (pin "C") (pinfunction "C_C") (pintype "passive"))
      (node (ref "D3") (pin "C") (pinfunction "C_C") (pintype "passive"))
      (node (ref "D30") (pin "C") (pinfunction "C_C") (pintype "passive"))
      (node (ref "D4") (pin "C") (pinfunction "C_C") (pintype "passive"))
      (node (ref "D5") (pin "C") (pinfunction "C_C") (pintype "passive"))
      (node (ref "D6") (pin "C") (pinfunction "C_C") (pintype "passive"))
      (node (ref "D7") (pin "C") (pinfunction "C_C") (pintype "passive"))
      (node (ref "D8") (pin "C") (pinfunction "C_C") (pintype "passive"))
      (node (ref "D9") (pin "C") (pinfunction "C_C") (pintype "passive"))
      (node (ref "F1") (pin "2A") (pinfunction "2_2A") (pintype "passive"))
      (node (ref "OK1") (pin "4") (pinfunction "COL_4") (pintype "passive"))
      (node (ref "OK10") (pin "4") (pinfunction "COL_4") (pintype "passive"))
      (node (ref "OK11") (pin "4") (pinfunction "COL_4") (pintype "passive"))
      (node (ref "OK12") (pin "4") (pinfunction "COL_4") (pintype "passive"))
      (node (ref "OK13") (pin "4") (pinfunction "COL_4") (pintype "passive"))
      (node (ref "OK14") (pin "4") (pinfunction "COL_4") (pintype "passive"))
      (node (ref "OK15") (pin "4") (pinfunction "COL_4") (pintype "passive"))
      (node (ref "OK16") (pin "4") (pinfunction "COL_4") (pintype "passive"))
      (node (ref "OK17") (pin "4") (pinfunction "COL_4") (pintype "passive"))
      (node (ref "OK18") (pin "4") (pinfunction "COL_4") (pintype "passive"))
      (node (ref "OK19") (pin "4") (pinfunction "COL_4") (pintype "passive"))
      (node (ref "OK2") (pin "4") (pinfunction "COL_4") (pintype "passive"))
      (node (ref "OK20") (pin "4") (pinfunction "COL_4") (pintype "passive"))
      (node (ref "OK21") (pin "4") (pinfunction "COL_4") (pintype "passive"))
      (node (ref "OK22") (pin "4") (pinfunction "COL_4") (pintype "passive"))
      (node (ref "OK23") (pin "4") (pinfunction "COL_4") (pintype "passive"))
      (node (ref "OK24") (pin "4") (pinfunction "COL_4") (pintype "passive"))
      (node (ref "OK25") (pin "4") (pinfunction "COL_4") (pintype "passive"))
      (node (ref "OK26") (pin "4") (pinfunction "COL_4") (pintype "passive"))
      (node (ref "OK27") (pin "4") (pinfunction "COL_4") (pintype "passive"))
      (node (ref "OK28") (pin "4") (pinfunction "COL_4") (pintype "passive"))
      (node (ref "OK3") (pin "4") (pinfunction "COL_4") (pintype "passive"))
      (node (ref "OK4") (pin "4") (pinfunction "COL_4") (pintype "passive"))
      (node (ref "OK5") (pin "4") (pinfunction "COL_4") (pintype "passive"))
      (node (ref "OK6") (pin "4") (pinfunction "COL_4") (pintype "passive"))
      (node (ref "OK7") (pin "4") (pinfunction "COL_4") (pintype "passive"))
      (node (ref "OK8") (pin "4") (pinfunction "COL_4") (pintype "passive"))
      (node (ref "OK9") (pin "4") (pinfunction "COL_4") (pintype "passive"))
      (node (ref "R119") (pin "2") (pinfunction "2_2") (pintype "passive"))
      (node (ref "R120") (pin "2") (pinfunction "2_2") (pintype "passive"))
      (node (ref "R121") (pin "2") (pinfunction "2_2") (pintype "passive"))
      (node (ref "R122") (pin "2") (pinfunction "2_2") (pintype "passive"))
      (node (ref "R123") (pin "2") (pinfunction "2_2") (pintype "passive"))
      (node (ref "R124") (pin "2") (pinfunction "2_2") (pintype "passive"))
      (node (ref "R125") (pin "2") (pinfunction "2_2") (pintype "passive"))
      (node (ref "R126") (pin "2") (pinfunction "2_2") (pintype "passive"))
      (node (ref "R127") (pin "2") (pinfunction "2_2") (pintype "passive"))
      (node (ref "R128") (pin "2") (pinfunction "2_2") (pintype "passive"))
      (node (ref "R129") (pin "2") (pinfunction "2_2") (pintype "passive"))
      (node (ref "R130") (pin "2") (pinfunction "2_2") (pintype "passive"))
      (node (ref "R131") (pin "2") (pinfunction "2_2") (pintype "passive"))
      (node (ref "R132") (pin "2") (pinfunction "2_2") (pintype "passive"))
      (node (ref "R133") (pin "2") (pinfunction "2_2") (pintype "passive"))
      (node (ref "R134") (pin "2") (pinfunction "2_2") (pintype "passive"))
      (node (ref "R135") (pin "2") (pinfunction "2_2") (pintype "passive"))
      (node (ref "R136") (pin "2") (pinfunction "2_2") (pintype "passive"))
      (node (ref "R137") (pin "2") (pinfunction "2_2") (pintype "passive"))
      (node (ref "R138") (pin "2") (pinfunction "2_2") (pintype "passive"))
      (node (ref "R73") (pin "2") (pinfunction "2_2") (pintype "passive"))
      (node (ref "R76") (pin "2") (pinfunction "2_2") (pintype "passive"))
      (node (ref "R79") (pin "2") (pinfunction "2_2") (pintype "passive"))
      (node (ref "R82") (pin "2") (pinfunction "2_2") (pintype "passive"))
      (node (ref "R85") (pin "2") (pinfunction "2_2") (pintype "passive"))
      (node (ref "R88") (pin "2") (pinfunction "2_2") (pintype "passive"))
      (node (ref "R91") (pin "2") (pinfunction "2_2") (pintype "passive"))
      (node (ref "R94") (pin "2") (pinfunction "2_2") (pintype "passive"))
      (node (ref "X2") (pin "1") (pinfunction "K_1") (pintype "passive"))
      (node (ref "X2") (pin "2") (pinfunction "K_2") (pintype "passive"))
      (node (ref "X2") (pin "3") (pinfunction "K_3") (pintype "passive"))
      (node (ref "X2") (pin "4") (pinfunction "K_4") (pintype "passive"))
      (node (ref "X2") (pin "5") (pinfunction "K_5") (pintype "passive"))
      (node (ref "X2") (pin "6") (pinfunction "K_6") (pintype "passive"))
      (node (ref "X2") (pin "7") (pinfunction "K_7") (pintype "passive"))
      (node (ref "X2") (pin "8") (pinfunction "K_8") (pintype "passive"))
      (node (ref "X2") (pin "9") (pinfunction "K_9") (pintype "passive"))
      (node (ref "X4") (pin "1") (pinfunction "K_1") (pintype "passive"))
      (node (ref "X4") (pin "2") (pinfunction "K_2") (pintype "passive"))
      (node (ref "X4") (pin "3") (pinfunction "K_3") (pintype "passive"))
      (node (ref "X4") (pin "4") (pinfunction "K_4") (pintype "passive"))
    )
    (net (code "4") (name "/5V_USB") (class "Default")
      (node (ref "C44") (pin "1") (pinfunction "1_1") (pintype "passive"))
      (node (ref "C45") (pin "2") (pinfunction "2_2") (pintype "passive"))
      (node (ref "CONN1") (pin "P1") (pinfunction "VUSB_P1") (pintype "bidirectional"))
      (node (ref "U$1") (pin "16") (pinfunction "VCC_16") (pintype "bidirectional"))
    )
    (net (code "5") (name "/ACTLED") (class "Default")
      (node (ref "R26") (pin "1") (pinfunction "1_1") (pintype "passive"))
      (node (ref "U2") (pin "27") (pinfunction "ACTLED_27") (pintype "passive"))
    )
    (net (code "6") (name "/BOOT0") (class "Default")
      (node (ref "IC2") (pin "94") (pinfunction "BOOT0_94") (pintype "input"))
      (node (ref "JP1") (pin "33") (pinfunction "33_33") (pintype "passive"))
      (node (ref "R23") (pin "1") (pinfunction "1_1") (pintype "passive"))
      (node (ref "R9") (pin "1") (pinfunction "1_1") (pintype "passive"))
    )
    (net (code "7") (name "/BOOT1") (class "Default")
      (node (ref "IC2") (pin "37") (pinfunction "PB2_37") (pintype "bidirectional"))
      (node (ref "JP1") (pin "34") (pinfunction "34_34") (pintype "passive"))
      (node (ref "R11") (pin "1") (pinfunction "1_1") (pintype "passive"))
    )
    (net (code "8") (name "/CH340_D+") (class "Default")
      (node (ref "CONN1") (pin "P3") (pinfunction "D+_P3") (pintype "bidirectional"))
      (node (ref "U$1") (pin "5") (pinfunction "D+_5") (pintype "bidirectional"))
    )
    (net (code "9") (name "/CH340_D-") (class "Default")
      (node (ref "CONN1") (pin "P2") (pinfunction "D-_P2") (pintype "bidirectional"))
      (node (ref "U$1") (pin "6") (pinfunction "D-_6") (pintype "bidirectional"))
    )
    (net (code "10") (name "/I2C1_SCL") (class "Default")
      (node (ref "IC2") (pin "92") (pinfunction "PB6_92") (pintype "bidirectional"))
      (node (ref "JP1") (pin "29") (pinfunction "29_29") (pintype "passive"))
    )
    (net (code "11") (name "/I2C1_SDA") (class "Default")
      (node (ref "IC2") (pin "93") (pinfunction "PB7_93") (pintype "bidirectional"))
      (node (ref "JP1") (pin "31") (pinfunction "31_31") (pintype "passive"))
    )
    (net (code "12") (name "/I2C1_SMBA") (class "Default")
      (node (ref "IC2") (pin "91") (pinfunction "PB5_91") (pintype "bidirectional"))
      (node (ref "JP1") (pin "32") (pinfunction "32_32") (pintype "passive"))
    )
    (net (code "13") (name "/INTN") (class "Default")
      (node (ref "R6") (pin "2") (pinfunction "2_2") (pintype "passive"))
      (node (ref "U2") (pin "36") (pinfunction "INT_N_36") (pintype "passive"))
    )
    (net (code "14") (name "/LINKLED") (class "Default")
      (node (ref "R28") (pin "1") (pinfunction "1_1") (pintype "passive"))
      (node (ref "U2") (pin "25") (pinfunction "LINKLED_25") (pintype "passive"))
    )
    (net (code "15") (name "/PA0") (class "Default")
      (node (ref "IC2") (pin "23") (pinfunction "PA0-WKUP_23") (pintype "bidirectional"))
      (node (ref "OK1") (pin "1") (pinfunction "A_1") (pintype "passive"))
      (node (ref "R95") (pin "1") (pinfunction "1_1") (pintype "passive"))
    )
    (net (code "16") (name "/PA1") (class "Default")
      (node (ref "IC2") (pin "24") (pinfunction "PA1_24") (pintype "bidirectional"))
      (node (ref "OK2") (pin "1") (pinfunction "A_1") (pintype "passive"))
      (node (ref "R96") (pin "1") (pinfunction "1_1") (pintype "passive"))
    )
    (net (code "17") (name "/PA2") (class "Default")
      (node (ref "IC2") (pin "25") (pinfunction "PA2_25") (pintype "bidirectional"))
      (node (ref "OK3") (pin "1") (pinfunction "A_1") (pintype "passive"))
      (node (ref "R97") (pin "1") (pinfunction "1_1") (pintype "passive"))
    )
    (net (code "18") (name "/PA3") (class "Default")
      (node (ref "IC2") (pin "26") (pinfunction "PA3_26") (pintype "bidirectional"))
      (node (ref "OK4") (pin "1") (pinfunction "A_1") (pintype "passive"))
      (node (ref "R98") (pin "1") (pinfunction "1_1") (pintype "passive"))
    )
    (net (code "19") (name "/PA13") (class "Default")
      (node (ref "IC2") (pin "72") (pinfunction "PA13_72") (pintype "bidirectional"))
    )
    (net (code "20") (name "/PA14") (class "Default")
      (node (ref "IC2") (pin "76") (pinfunction "PA14_76") (pintype "bidirectional"))
    )
    (net (code "21") (name "/PA15") (class "Default")
      (node (ref "IC2") (pin "77") (pinfunction "PA15_77") (pintype "bidirectional"))
      (node (ref "OK14") (pin "1") (pinfunction "A_1") (pintype "passive"))
      (node (ref "R108") (pin "1") (pinfunction "1_1") (pintype "passive"))
    )
    (net (code "22") (name "/PB0") (class "Default")
      (node (ref "IC2") (pin "35") (pinfunction "PB0_35") (pintype "bidirectional"))
      (node (ref "OK6") (pin "1") (pinfunction "A_1") (pintype "passive"))
      (node (ref "R100") (pin "1") (pinfunction "1_1") (pintype "passive"))
    )
    (net (code "23") (name "/PB1") (class "Default")
      (node (ref "IC2") (pin "36") (pinfunction "PB1_36") (pintype "bidirectional"))
      (node (ref "OK7") (pin "1") (pinfunction "A_1") (pintype "passive"))
      (node (ref "R101") (pin "1") (pinfunction "1_1") (pintype "passive"))
    )
    (net (code "24") (name "/PB3") (class "Default")
      (node (ref "IC2") (pin "89") (pinfunction "PB3_89") (pintype "bidirectional"))
      (node (ref "OK13") (pin "1") (pinfunction "A_1") (pintype "passive"))
      (node (ref "R107") (pin "1") (pinfunction "1_1") (pintype "passive"))
    )
    (net (code "25") (name "/PB4") (class "Default")
      (node (ref "IC2") (pin "90") (pinfunction "PB4_90") (pintype "bidirectional"))
      (node (ref "OK12") (pin "1") (pinfunction "A_1") (pintype "passive"))
      (node (ref "R106") (pin "1") (pinfunction "1_1") (pintype "passive"))
    )
    (net (code "26") (name "/PB8") (class "Default")
      (node (ref "IC2") (pin "95") (pinfunction "PB8_95") (pintype "bidirectional"))
      (node (ref "OK28") (pin "1") (pinfunction "A_1") (pintype "passive"))
      (node (ref "R70") (pin "1") (pinfunction "1_1") (pintype "passive"))
    )
    (net (code "27") (name "/PB9") (class "Default")
      (node (ref "IC2") (pin "96") (pinfunction "PB9_96") (pintype "bidirectional"))
      (node (ref "OK5") (pin "1") (pinfunction "A_1") (pintype "passive"))
      (node (ref "R99") (pin "1") (pinfunction "1_1") (pintype "passive"))
    )
    (net (code "28") (name "/PB10") (class "Default")
      (node (ref "IC2") (pin "47") (pinfunction "PB10_47") (pintype "bidirectional"))
      (node (ref "OK15") (pin "1") (pinfunction "A_1") (pintype "passive"))
      (node (ref "R109") (pin "1") (pinfunction "1_1") (pintype "passive"))
    )
    (net (code "29") (name "/PB11") (class "Default")
      (node (ref "IC2") (pin "48") (pinfunction "PB11_48") (pintype "bidirectional"))
      (node (ref "OK16") (pin "1") (pinfunction "A_1") (pintype "passive"))
      (node (ref "R110") (pin "1") (pinfunction "1_1") (pintype "passive"))
    )
    (net (code "30") (name "/PC0") (class "Default")
      (node (ref "IC2") (pin "15") (pinfunction "PC0_15") (pintype "bidirectional"))
    )
    (net (code "31") (name "/PC1") (class "Default")
      (node (ref "IC2") (pin "16") (pinfunction "PC1_16") (pintype "bidirectional"))
    )
    (net (code "32") (name "/PC2") (class "Default")
      (node (ref "IC2") (pin "17") (pinfunction "PC2_17") (pintype "bidirectional"))
    )
    (net (code "33") (name "/PC3") (class "Default")
      (node (ref "IC2") (pin "18") (pinfunction "PC3_18") (pintype "bidirectional"))
    )
    (net (code "34") (name "/PC4") (class "Default")
      (node (ref "IC2") (pin "33") (pinfunction "PC4_33") (pintype "bidirectional"))
    )
    (net (code "35") (name "/PC5") (class "Default")
      (node (ref "IC2") (pin "34") (pinfunction "PC5_34") (pintype "bidirectional"))
    )
    (net (code "36") (name "/PC6") (class "Default")
      (node (ref "IC2") (pin "63") (pinfunction "PC6_63") (pintype "bidirectional"))
      (node (ref "OK21") (pin "1") (pinfunction "A_1") (pintype "passive"))
      (node (ref "R115") (pin "1") (pinfunction "1_1") (pintype "passive"))
    )
    (net (code "37") (name "/PC7") (class "Default")
      (node (ref "IC2") (pin "64") (pinfunction "PC7_64") (pintype "bidirectional"))
      (node (ref "OK22") (pin "1") (pinfunction "A_1") (pintype "passive"))
      (node (ref "R116") (pin "1") (pinfunction "1_1") (pintype "passive"))
    )
    (net (code "38") (name "/PC8") (class "Default")
      (node (ref "IC2") (pin "65") (pinfunction "PC8_65") (pintype "bidirectional"))
      (node (ref "OK23") (pin "1") (pinfunction "A_1") (pintype "passive"))
      (node (ref "R117") (pin "1") (pinfunction "1_1") (pintype "passive"))
    )
    (net (code "39") (name "/PC9") (class "Default")
      (node (ref "IC2") (pin "66") (pinfunction "PC9_66") (pintype "bidirectional"))
      (node (ref "OK24") (pin "1") (pinfunction "A_1") (pintype "passive"))
      (node (ref "R118") (pin "1") (pinfunction "1_1") (pintype "passive"))
    )
    (net (code "40") (name "/PC13") (class "Default")
      (node (ref "IC2") (pin "7") (pinfunction "PC13_7") (pintype "bidirectional"))
      (node (ref "LED1") (pin "A") (pinfunction "A_A") (pintype "passive"))
    )
    (net (code "41") (name "/PD0") (class "Default")
      (node (ref "IC2") (pin "81") (pinfunction "PD0_81") (pintype "bidirectional"))
    )
    (net (code "42") (name "/PD1") (class "Default")
      (node (ref "IC2") (pin "82") (pinfunction "PD1_82") (pintype "bidirectional"))
    )
    (net (code "43") (name "/PD8") (class "Default")
      (node (ref "IC2") (pin "55") (pinfunction "PD8_55") (pintype "bidirectional"))
    )
    (net (code "44") (name "/PD9") (class "Default")
      (node (ref "IC2") (pin "56") (pinfunction "PD9_56") (pintype "bidirectional"))
    )
    (net (code "45") (name "/PD10") (class "Default")
      (node (ref "IC2") (pin "57") (pinfunction "PD10_57") (pintype "bidirectional"))
    )
    (net (code "46") (name "/PD11") (class "Default")
      (node (ref "IC2") (pin "58") (pinfunction "PD11_58") (pintype "bidirectional"))
    )
    (net (code "47") (name "/PD12") (class "Default")
      (node (ref "IC2") (pin "59") (pinfunction "PD12_59") (pintype "bidirectional"))
      (node (ref "OK17") (pin "1") (pinfunction "A_1") (pintype "passive"))
      (node (ref "R111") (pin "1") (pinfunction "1_1") (pintype "passive"))
    )
    (net (code "48") (name "/PD13") (class "Default")
      (node (ref "IC2") (pin "60") (pinfunction "PD13_60") (pintype "bidirectional"))
      (node (ref "OK18") (pin "1") (pinfunction "A_1") (pintype "passive"))
      (node (ref "R112") (pin "1") (pinfunction "1_1") (pintype "passive"))
    )
    (net (code "49") (name "/PD14") (class "Default")
      (node (ref "IC2") (pin "61") (pinfunction "PD14_61") (pintype "bidirectional"))
      (node (ref "OK19") (pin "1") (pinfunction "A_1") (pintype "passive"))
      (node (ref "R113") (pin "1") (pinfunction "1_1") (pintype "passive"))
    )
    (net (code "50") (name "/PD15") (class "Default")
      (node (ref "IC2") (pin "62") (pinfunction "PD15_62") (pintype "bidirectional"))
      (node (ref "OK20") (pin "1") (pinfunction "A_1") (pintype "passive"))
      (node (ref "R114") (pin "1") (pinfunction "1_1") (pintype "passive"))
    )
    (net (code "51") (name "/PE0") (class "Default")
      (node (ref "IC2") (pin "97") (pinfunction "PE0_97") (pintype "bidirectional"))
    )
    (net (code "52") (name "/PE1") (class "Default")
      (node (ref "IC2") (pin "98") (pinfunction "PE1_98") (pintype "bidirectional"))
    )
    (net (code "53") (name "/PE2") (class "Default")
      (node (ref "IC2") (pin "1") (pinfunction "PE2_1") (pintype "bidirectional"))
    )
    (net (code "54") (name "/PE3") (class "Default")
      (node (ref "IC2") (pin "2") (pinfunction "PE3_2") (pintype "bidirectional"))
    )
    (net (code "55") (name "/PE4") (class "Default")
      (node (ref "IC2") (pin "3") (pinfunction "PE4_3") (pintype "bidirectional"))
    )
    (net (code "56") (name "/PE5") (class "Default")
      (node (ref "IC2") (pin "4") (pinfunction "PE5_4") (pintype "bidirectional"))
    )
    (net (code "57") (name "/PE6") (class "Default")
      (node (ref "IC2") (pin "5") (pinfunction "PE6_5") (pintype "bidirectional"))
    )
    (net (code "58") (name "/PE7") (class "Default")
      (node (ref "IC2") (pin "38") (pinfunction "PE7_38") (pintype "bidirectional"))
    )
    (net (code "59") (name "/PE8") (class "Default")
      (node (ref "IC2") (pin "39") (pinfunction "PE8_39") (pintype "bidirectional"))
      (node (ref "OK8") (pin "1") (pinfunction "A_1") (pintype "passive"))
      (node (ref "R102") (pin "1") (pinfunction "1_1") (pintype "passive"))
    )
    (net (code "60") (name "/PE9") (class "Default")
      (node (ref "IC2") (pin "40") (pinfunction "PE9_40") (pintype "bidirectional"))
      (node (ref "OK9") (pin "1") (pinfunction "A_1") (pintype "passive"))
      (node (ref "R103") (pin "1") (pinfunction "1_1") (pintype "passive"))
    )
    (net (code "61") (name "/PE10") (class "Default")
      (node (ref "IC2") (pin "41") (pinfunction "PE10_41") (pintype "bidirectional"))
      (node (ref "OK10") (pin "1") (pinfunction "A_1") (pintype "passive"))
      (node (ref "R104") (pin "1") (pinfunction "1_1") (pintype "passive"))
    )
    (net (code "62") (name "/PE11") (class "Default")
      (node (ref "IC2") (pin "42") (pinfunction "PE11_42") (pintype "bidirectional"))
      (node (ref "OK11") (pin "1") (pinfunction "A_1") (pintype "passive"))
      (node (ref "R105") (pin "1") (pinfunction "1_1") (pintype "passive"))
    )
    (net (code "63") (name "/PE12") (class "Default")
      (node (ref "IC2") (pin "43") (pinfunction "PE12_43") (pintype "bidirectional"))
      (node (ref "OK25") (pin "1") (pinfunction "A_1") (pintype "passive"))
      (node (ref "R42") (pin "1") (pinfunction "1_1") (pintype "passive"))
    )
    (net (code "64") (name "/PE13") (class "Default")
      (node (ref "IC2") (pin "44") (pinfunction "PE13_44") (pintype "bidirectional"))
      (node (ref "OK26") (pin "1") (pinfunction "A_1") (pintype "passive"))
      (node (ref "R51") (pin "1") (pinfunction "1_1") (pintype "passive"))
    )
    (net (code "65") (name "/PE14") (class "Default")
      (node (ref "IC2") (pin "45") (pinfunction "PE14_45") (pintype "bidirectional"))
      (node (ref "OK27") (pin "1") (pinfunction "A_1") (pintype "passive"))
      (node (ref "R61") (pin "1") (pinfunction "1_1") (pintype "passive"))
    )
    (net (code "66") (name "/PE15") (class "Default")
      (node (ref "IC2") (pin "46") (pinfunction "PE15_46") (pintype "bidirectional"))
    )
    (net (code "67") (name "/R-CT") (class "Default")
      (node (ref "C13") (pin "2") (pinfunction "2_2") (pintype "passive"))
      (node (ref "J2") (pin "P5") (pinfunction "P5_P5") (pintype "bidirectional"))
      (node (ref "R34") (pin "1") (pinfunction "1_1") (pintype "passive"))
      (node (ref "R36") (pin "1") (pinfunction "1_1") (pintype "passive"))
    )
    (net (code "68") (name "/RD+") (class "Default")
      (node (ref "C16") (pin "2") (pinfunction "2_2") (pintype "passive"))
      (node (ref "J2") (pin "RD+") (pinfunction "RD+_RD+") (pintype "bidirectional"))
    )
    (net (code "69") (name "/RD-") (class "Default")
      (node (ref "C12") (pin "2") (pinfunction "2_2") (pintype "passive"))
      (node (ref "J2") (pin "RD-") (pinfunction "RD-_RD-") (pintype "bidirectional"))
    )
    (net (code "70") (name "/RESET#") (class "Default")
      (node (ref "C28") (pin "1") (pinfunction "1_1") (pintype "passive"))
      (node (ref "D26") (pin "A") (pinfunction "A_A") (pintype "passive"))
      (node (ref "IC2") (pin "14") (pinfunction "NRST_14") (pintype "bidirectional"))
      (node (ref "R31") (pin "1") (pinfunction "1_1") (pintype "passive"))
      (node (ref "S2") (pin "2") (pinfunction "2_2") (pintype "passive"))
    )
    (net (code "71") (name "/RSTN") (class "Default")
      (node (ref "C8") (pin "1") (pinfunction "1_1") (pintype "passive"))
      (node (ref "R8") (pin "2") (pinfunction "2_2") (pintype "passive"))
      (node (ref "U2") (pin "37") (pinfunction "RST_N_37") (pintype "passive"))
    )
    (net (code "72") (name "/RXN") (class "Default")
      (node (ref "C12") (pin "1") (pinfunction "1_1") (pintype "passive"))
      (node (ref "R16") (pin "2") (pinfunction "2_2") (pintype "passive"))
      (node (ref "R36") (pin "2") (pinfunction "2_2") (pintype "passive"))
    )
    (net (code "73") (name "/RXP") (class "Default")
      (node (ref "C16") (pin "1") (pinfunction "1_1") (pintype "passive"))
      (node (ref "R14") (pin "2") (pinfunction "2_2") (pintype "passive"))
      (node (ref "R34") (pin "2") (pinfunction "2_2") (pintype "passive"))
    )
    (net (code "74") (name "/SPI1_MISO") (class "Default")
      (node (ref "IC2") (pin "31") (pinfunction "PA6_31") (pintype "bidirectional"))
      (node (ref "JP1") (pin "22") (pinfunction "22_22") (pintype "passive"))
      (node (ref "U2") (pin "34") (pinfunction "MISO_34") (pintype "passive"))
    )
    (net (code "75") (name "/SPI1_MOSI") (class "Default")
      (node (ref "IC2") (pin "32") (pinfunction "PA7_32") (pintype "bidirectional"))
      (node (ref "JP1") (pin "24") (pinfunction "24_24") (pintype "passive"))
      (node (ref "U2") (pin "35") (pinfunction "MOSI_35") (pintype "passive"))
    )
    (net (code "76") (name "/SPI1_NSS") (class "Default")
      (node (ref "IC2") (pin "29") (pinfunction "PA4_29") (pintype "bidirectional"))
      (node (ref "JP1") (pin "28") (pinfunction "28_28") (pintype "passive"))
      (node (ref "R4") (pin "2") (pinfunction "2_2") (pintype "passive"))
      (node (ref "U2") (pin "32") (pinfunction "SCS_N_32") (pintype "passive"))
    )
    (net (code "77") (name "/SPI1_SCK") (class "Default")
      (node (ref "IC2") (pin "30") (pinfunction "PA5_30") (pintype "bidirectional"))
      (node (ref "JP1") (pin "26") (pinfunction "26_26") (pintype "passive"))
      (node (ref "U2") (pin "33") (pinfunction "SCLK_33") (pintype "passive"))
    )
    (net (code "78") (name "/SPI2_MISO") (class "Default")
      (node (ref "IC2") (pin "53") (pinfunction "PB14_53") (pintype "bidirectional"))
      (node (ref "JP1") (pin "12") (pinfunction "12_12") (pintype "passive"))
    )
    (net (code "79") (name "/SPI2_MOSI") (class "Default")
      (node (ref "IC2") (pin "54") (pinfunction "PB15_54") (pintype "bidirectional"))
      (node (ref "JP1") (pin "14") (pinfunction "14_14") (pintype "passive"))
    )
    (net (code "80") (name "/SPI2_NSS") (class "Default")
      (node (ref "IC2") (pin "51") (pinfunction "PB12_51") (pintype "bidirectional"))
      (node (ref "JP1") (pin "18") (pinfunction "18_18") (pintype "passive"))
    )
    (net (code "81") (name "/SPI2_SCK") (class "Default")
      (node (ref "IC2") (pin "52") (pinfunction "PB13_52") (pintype "bidirectional"))
      (node (ref "JP1") (pin "16") (pinfunction "16_16") (pintype "passive"))
    )
    (net (code "82") (name "/T-CT") (class "Default")
      (node (ref "C14") (pin "2") (pinfunction "2_2") (pintype "passive"))
      (node (ref "J2") (pin "P4") (pinfunction "P4_P4") (pintype "bidirectional"))
      (node (ref "R24") (pin "1") (pinfunction "1_1") (pintype "passive"))
    )
    (net (code "83") (name "/TXN") (class "Default")
      (node (ref "J2") (pin "TD-") (pinfunction "TD-_TD-") (pintype "bidirectional"))
      (node (ref "R12") (pin "2") (pinfunction "2_2") (pintype "passive"))
      (node (ref "R20") (pin "1") (pinfunction "1_1") (pintype "passive"))
    )
    (net (code "84") (name "/TXP") (class "Default")
      (node (ref "J2") (pin "TD+") (pinfunction "TD+_TD+") (pintype "bidirectional"))
      (node (ref "R10") (pin "2") (pinfunction "2_2") (pintype "passive"))
      (node (ref "R22") (pin "1") (pinfunction "1_1") (pintype "passive"))
    )
    (net (code "85") (name "/UART4_RX") (class "Default")
      (node (ref "IC2") (pin "78") (pinfunction "PC10_78") (pintype "bidirectional"))
      (node (ref "JP1") (pin "4") (pinfunction "4_4") (pintype "passive"))
    )
    (net (code "86") (name "/UART4_TX") (class "Default")
      (node (ref "IC2") (pin "79") (pinfunction "PC11_79") (pintype "bidirectional"))
      (node (ref "JP1") (pin "2") (pinfunction "2_2") (pintype "passive"))
    )
    (net (code "87") (name "/UART5_RX") (class "Default")
      (node (ref "IC2") (pin "80") (pinfunction "PC12_80") (pintype "bidirectional"))
      (node (ref "JP1") (pin "8") (pinfunction "8_8") (pintype "passive"))
    )
    (net (code "88") (name "/UART5_TX") (class "Default")
      (node (ref "IC2") (pin "83") (pinfunction "PD2_83") (pintype "bidirectional"))
      (node (ref "JP1") (pin "6") (pinfunction "6_6") (pintype "passive"))
    )
    (net (code "89") (name "/USART1_CK") (class "Default")
      (node (ref "IC2") (pin "67") (pinfunction "PA8_67") (pintype "bidirectional"))
      (node (ref "JP1") (pin "9") (pinfunction "9_9") (pintype "passive"))
    )
    (net (code "90") (name "/USART1_CTS") (class "Default")
      (node (ref "IC2") (pin "70") (pinfunction "PA11_70") (pintype "bidirectional"))
      (node (ref "JP1") (pin "1") (pinfunction "1_1") (pintype "passive"))
    )
    (net (code "91") (name "/USART1_RTS") (class "Default")
      (node (ref "IC2") (pin "71") (pinfunction "PA12_71") (pintype "bidirectional"))
      (node (ref "JP1") (pin "3") (pinfunction "3_3") (pintype "passive"))
    )
    (net (code "92") (name "/USART1_RX") (class "Default")
      (node (ref "IC2") (pin "68") (pinfunction "PA9_68") (pintype "bidirectional"))
      (node (ref "JP1") (pin "7") (pinfunction "7_7") (pintype "passive"))
      (node (ref "U$1") (pin "3") (pinfunction "RX_3") (pintype "bidirectional"))
    )
    (net (code "93") (name "/USART1_TX") (class "Default")
      (node (ref "IC2") (pin "69") (pinfunction "PA10_69") (pintype "bidirectional"))
      (node (ref "JP1") (pin "5") (pinfunction "5_5") (pintype "passive"))
      (node (ref "U$1") (pin "2") (pinfunction "TX_2") (pintype "bidirectional"))
    )
    (net (code "94") (name "/USART2_CK") (class "Default")
      (node (ref "IC2") (pin "88") (pinfunction "PD7_88") (pintype "bidirectional"))
      (node (ref "JP1") (pin "23") (pinfunction "23_23") (pintype "passive"))
    )
    (net (code "95") (name "/USART2_CTS") (class "Default")
      (node (ref "IC2") (pin "84") (pinfunction "PD3_84") (pintype "bidirectional"))
      (node (ref "JP1") (pin "15") (pinfunction "15_15") (pintype "passive"))
    )
    (net (code "96") (name "/USART2_RTS") (class "Default")
      (node (ref "IC2") (pin "85") (pinfunction "PD4_85") (pintype "bidirectional"))
      (node (ref "JP1") (pin "17") (pinfunction "17_17") (pintype "passive"))
    )
    (net (code "97") (name "/USART2_RX") (class "Default")
      (node (ref "IC2") (pin "86") (pinfunction "PD5_86") (pintype "bidirectional"))
      (node (ref "JP1") (pin "21") (pinfunction "21_21") (pintype "passive"))
    )
    (net (code "98") (name "/USART2_TX") (class "Default")
      (node (ref "IC2") (pin "87") (pinfunction "PD6_87") (pintype "bidirectional"))
      (node (ref "JP1") (pin "19") (pinfunction "19_19") (pintype "passive"))
    )
    (net (code "99") (name "/VREF+") (class "Default")
      (node (ref "IC2") (pin "21") (pinfunction "VREF+_21") (pintype "power_in"))
    )
    (net (code "100") (name "/VREF-") (class "Default")
      (node (ref "IC2") (pin "20") (pinfunction "VREF-_20") (pintype "power_in"))
    )
    (net (code "101") (name "Net-(C2-Pad1)") (class "Default")
      (node (ref "C2") (pin "1") (pinfunction "1_1") (pintype "passive"))
      (node (ref "Q3") (pin "2") (pinfunction "2_2") (pintype "passive"))
      (node (ref "R3") (pin "1") (pinfunction "1_1") (pintype "passive"))
    )
    (net (code "102") (name "Net-(D25-PadC)") (class "Default")
      (node (ref "D25") (pin "C") (pinfunction "C_C") (pintype "passive"))
      (node (ref "U$2") (pin "IN+.1") (pinfunction "IN+.1_IN+.1") (pintype "bidirectional"))
      (node (ref "U$2") (pin "IN+.2") (pinfunction "IN+.2_IN+.2") (pintype "bidirectional"))
    )
    (net (code "103") (name "Net-(F1-1)") (class "Default")
      (node (ref "F1") (pin "1A") (pinfunction "1_1A") (pintype "passive"))
      (node (ref "J1") (pin "2") (pinfunction "2_2") (pintype "passive"))
      (node (ref "J3") (pin "PWR") (pinfunction "PWR_PWR") (pintype "bidirectional"))
    )
    (net (code "104") (name "Net-(IC2A-OSC_IN)") (class "Default")
      (node (ref "C29") (pin "1") (pinfunction "1_1") (pintype "passive"))
      (node (ref "IC2") (pin "12") (pinfunction "OSC_IN_12") (pintype "bidirectional"))
      (node (ref "Q3") (pin "1") (pinfunction "1_1") (pintype "passive"))
    )
    (net (code "105") (name "Net-(IC2A-OSC_OUT)") (class "Default")
      (node (ref "IC2") (pin "13") (pinfunction "OSC_OUT_13") (pintype "bidirectional"))
      (node (ref "R3") (pin "2") (pinfunction "2_2") (pintype "passive"))
    )
    (net (code "106") (name "Net-(IC2A-PC14)") (class "Default")
      (node (ref "C17") (pin "1") (pinfunction "1_1") (pintype "passive"))
      (node (ref "IC2") (pin "8") (pinfunction "PC14_8") (pintype "bidirectional"))
      (node (ref "Q4") (pin "2") (pinfunction "2_2") (pintype "passive"))
    )
    (net (code "107") (name "Net-(IC2A-PC15)") (class "Default")
      (node (ref "C21") (pin "1") (pinfunction "1_1") (pintype "passive"))
      (node (ref "IC2") (pin "9") (pinfunction "PC15_9") (pintype "bidirectional"))
      (node (ref "Q4") (pin "1") (pinfunction "1_1") (pintype "passive"))
    )
    (net (code "108") (name "Net-(J2-PadG-)") (class "Default")
      (node (ref "J2") (pin "G-") (pinfunction "G-_G-") (pintype "bidirectional"))
      (node (ref "R28") (pin "2") (pinfunction "2_2") (pintype "passive"))
    )
    (net (code "109") (name "Net-(J2-PadY-)") (class "Default")
      (node (ref "J2") (pin "Y-") (pinfunction "Y-_Y-") (pintype "bidirectional"))
      (node (ref "R26") (pin "2") (pinfunction "2_2") (pintype "passive"))
    )
    (net (code "110") (name "Net-(LED1-PadC)") (class "Default")
      (node (ref "LED1") (pin "C") (pinfunction "C_C") (pintype "passive"))
      (node (ref "R2") (pin "1") (pinfunction "1_1") (pintype "passive"))
    )
    (net (code "111") (name "Net-(LED2-PadA)") (class "Default")
      (node (ref "LED2") (pin "A") (pinfunction "A_A") (pintype "passive"))
      (node (ref "R76") (pin "1") (pinfunction "1_1") (pintype "passive"))
    )
    (net (code "112") (name "Net-(LED3-PadA)") (class "Default")
      (node (ref "LED3") (pin "A") (pinfunction "A_A") (pintype "passive"))
      (node (ref "R79") (pin "1") (pinfunction "1_1") (pintype "passive"))
    )
    (net (code "113") (name "Net-(LED4-PadA)") (class "Default")
      (node (ref "LED4") (pin "A") (pinfunction "A_A") (pintype "passive"))
      (node (ref "R82") (pin "1") (pinfunction "1_1") (pintype "passive"))
    )
    (net (code "114") (name "Net-(LED5-PadA)") (class "Default")
      (node (ref "LED5") (pin "A") (pinfunction "A_A") (pintype "passive"))
      (node (ref "R85") (pin "1") (pinfunction "1_1") (pintype "passive"))
    )
    (net (code "115") (name "Net-(LED6-PadA)") (class "Default")
      (node (ref "LED6") (pin "A") (pinfunction "A_A") (pintype "passive"))
      (node (ref "R88") (pin "1") (pinfunction "1_1") (pintype "passive"))
    )
    (net (code "116") (name "Net-(LED7-PadA)") (class "Default")
      (node (ref "LED7") (pin "A") (pinfunction "A_A") (pintype "passive"))
      (node (ref "R91") (pin "1") (pinfunction "1_1") (pintype "passive"))
    )
    (net (code "117") (name "Net-(LED8-PadA)") (class "Default")
      (node (ref "LED8") (pin "A") (pinfunction "A_A") (pintype "passive"))
      (node (ref "R94") (pin "1") (pinfunction "1_1") (pintype "passive"))
    )
    (net (code "118") (name "Net-(LED9-PadA)") (class "Default")
      (node (ref "LED9") (pin "A") (pinfunction "A_A") (pintype "passive"))
      (node (ref "R119") (pin "1") (pinfunction "1_1") (pintype "passive"))
    )
    (net (code "119") (name "Net-(LED10-PadA)") (class "Default")
      (node (ref "LED10") (pin "A") (pinfunction "A_A") (pintype "passive"))
      (node (ref "R120") (pin "1") (pinfunction "1_1") (pintype "passive"))
    )
    (net (code "120") (name "Net-(LED11-PadA)") (class "Default")
      (node (ref "LED11") (pin "A") (pinfunction "A_A") (pintype "passive"))
      (node (ref "R121") (pin "1") (pinfunction "1_1") (pintype "passive"))
    )
    (net (code "121") (name "Net-(LED12-PadA)") (class "Default")
      (node (ref "LED12") (pin "A") (pinfunction "A_A") (pintype "passive"))
      (node (ref "R122") (pin "1") (pinfunction "1_1") (pintype "passive"))
    )
    (net (code "122") (name "Net-(LED13-PadA)") (class "Default")
      (node (ref "LED13") (pin "A") (pinfunction "A_A") (pintype "passive"))
      (node (ref "R123") (pin "1") (pinfunction "1_1") (pintype "passive"))
    )
    (net (code "123") (name "Net-(LED14-PadA)") (class "Default")
      (node (ref "LED14") (pin "A") (pinfunction "A_A") (pintype "passive"))
      (node (ref "R124") (pin "1") (pinfunction "1_1") (pintype "passive"))
    )
    (net (code "124") (name "Net-(LED15-PadA)") (class "Default")
      (node (ref "LED15") (pin "A") (pinfunction "A_A") (pintype "passive"))
      (node (ref "R125") (pin "1") (pinfunction "1_1") (pintype "passive"))
    )
    (net (code "125") (name "Net-(LED16-PadA)") (class "Default")
      (node (ref "LED16") (pin "A") (pinfunction "A_A") (pintype "passive"))
      (node (ref "R126") (pin "1") (pinfunction "1_1") (pintype "passive"))
    )
    (net (code "126") (name "Net-(LED17-PadA)") (class "Default")
      (node (ref "LED17") (pin "A") (pinfunction "A_A") (pintype "passive"))
      (node (ref "R127") (pin "1") (pinfunction "1_1") (pintype "passive"))
    )
    (net (code "127") (name "Net-(LED18-PadA)") (class "Default")
      (node (ref "LED18") (pin "A") (pinfunction "A_A") (pintype "passive"))
      (node (ref "R128") (pin "1") (pinfunction "1_1") (pintype "passive"))
    )
    (net (code "128") (name "Net-(LED19-PadA)") (class "Default")
      (node (ref "LED19") (pin "A") (pinfunction "A_A") (pintype "passive"))
      (node (ref "R73") (pin "1") (pinfunction "1_1") (pintype "passive"))
    )
    (net (code "129") (name "Net-(LED20-PadA)") (class "Default")
      (node (ref "LED20") (pin "A") (pinfunction "A_A") (pintype "passive"))
      (node (ref "R129") (pin "1") (pinfunction "1_1") (pintype "passive"))
    )
    (net (code "130") (name "Net-(LED21-PadA)") (class "Default")
      (node (ref "LED21") (pin "A") (pinfunction "A_A") (pintype "passive"))
      (node (ref "R130") (pin "1") (pinfunction "1_1") (pintype "passive"))
    )
    (net (code "131") (name "Net-(LED22-PadA)") (class "Default")
      (node (ref "LED22") (pin "A") (pinfunction "A_A") (pintype "passive"))
      (node (ref "R131") (pin "1") (pinfunction "1_1") (pintype "passive"))
    )
    (net (code "132") (name "Net-(LED23-PadA)") (class "Default")
      (node (ref "LED23") (pin "A") (pinfunction "A_A") (pintype "passive"))
      (node (ref "R132") (pin "1") (pinfunction "1_1") (pintype "passive"))
    )
    (net (code "133") (name "Net-(LED24-PadA)") (class "Default")
      (node (ref "LED24") (pin "A") (pinfunction "A_A") (pintype "passive"))
      (node (ref "R133") (pin "1") (pinfunction "1_1") (pintype "passive"))
    )
    (net (code "134") (name "Net-(LED25-PadA)") (class "Default")
      (node (ref "LED25") (pin "A") (pinfunction "A_A") (pintype "passive"))
      (node (ref "R134") (pin "1") (pinfunction "1_1") (pintype "passive"))
    )
    (net (code "135") (name "Net-(LED26-PadA)") (class "Default")
      (node (ref "LED26") (pin "A") (pinfunction "A_A") (pintype "passive"))
      (node (ref "R135") (pin "1") (pinfunction "1_1") (pintype "passive"))
    )
    (net (code "136") (name "Net-(LED27-PadA)") (class "Default")
      (node (ref "LED27") (pin "A") (pinfunction "A_A") (pintype "passive"))
      (node (ref "R136") (pin "1") (pinfunction "1_1") (pintype "passive"))
    )
    (net (code "137") (name "Net-(LED28-PadA)") (class "Default")
      (node (ref "LED28") (pin "A") (pinfunction "A_A") (pintype "passive"))
      (node (ref "R137") (pin "1") (pinfunction "1_1") (pintype "passive"))
    )
    (net (code "138") (name "Net-(LED29-PadA)") (class "Default")
      (node (ref "LED29") (pin "A") (pinfunction "A_A") (pintype "passive"))
      (node (ref "R138") (pin "1") (pinfunction "1_1") (pintype "passive"))
    )
    (net (code "139") (name "Net-(OK1-C)") (class "Default")
      (node (ref "OK1") (pin "2") (pinfunction "C_2") (pintype "passive"))
      (node (ref "R5") (pin "2") (pinfunction "2_2") (pintype "passive"))
    )
    (net (code "140") (name "Net-(OK1-EMIT)") (class "Default")
      (node (ref "OK1") (pin "3") (pinfunction "EMIT_3") (pintype "passive"))
      (node (ref "R7") (pin "1") (pinfunction "1_1") (pintype "passive"))
    )
    (net (code "141") (name "Net-(OK2-C)") (class "Default")
      (node (ref "OK2") (pin "2") (pinfunction "C_2") (pintype "passive"))
      (node (ref "R15") (pin "2") (pinfunction "2_2") (pintype "passive"))
    )
    (net (code "142") (name "Net-(OK2-EMIT)") (class "Default")
      (node (ref "OK2") (pin "3") (pinfunction "EMIT_3") (pintype "passive"))
      (node (ref "R17") (pin "1") (pinfunction "1_1") (pintype "passive"))
    )
    (net (code "143") (name "Net-(OK3-C)") (class "Default")
      (node (ref "OK3") (pin "2") (pinfunction "C_2") (pintype "passive"))
      (node (ref "R19") (pin "2") (pinfunction "2_2") (pintype "passive"))
    )
    (net (code "144") (name "Net-(OK3-EMIT)") (class "Default")
      (node (ref "OK3") (pin "3") (pinfunction "EMIT_3") (pintype "passive"))
      (node (ref "R21") (pin "1") (pinfunction "1_1") (pintype "passive"))
    )
    (net (code "145") (name "Net-(OK4-C)") (class "Default")
      (node (ref "OK4") (pin "2") (pinfunction "C_2") (pintype "passive"))
      (node (ref "R25") (pin "2") (pinfunction "2_2") (pintype "passive"))
    )
    (net (code "146") (name "Net-(OK4-EMIT)") (class "Default")
      (node (ref "OK4") (pin "3") (pinfunction "EMIT_3") (pintype "passive"))
      (node (ref "R27") (pin "1") (pinfunction "1_1") (pintype "passive"))
    )
    (net (code "147") (name "Net-(OK5-C)") (class "Default")
      (node (ref "OK5") (pin "2") (pinfunction "C_2") (pintype "passive"))
      (node (ref "R32") (pin "2") (pinfunction "2_2") (pintype "passive"))
    )
    (net (code "148") (name "Net-(OK5-EMIT)") (class "Default")
      (node (ref "OK5") (pin "3") (pinfunction "EMIT_3") (pintype "passive"))
      (node (ref "R33") (pin "1") (pinfunction "1_1") (pintype "passive"))
    )
    (net (code "149") (name "Net-(OK6-C)") (class "Default")
      (node (ref "OK6") (pin "2") (pinfunction "C_2") (pintype "passive"))
      (node (ref "R37") (pin "2") (pinfunction "2_2") (pintype "passive"))
    )
    (net (code "150") (name "Net-(OK6-EMIT)") (class "Default")
      (node (ref "OK6") (pin "3") (pinfunction "EMIT_3") (pintype "passive"))
      (node (ref "R38") (pin "1") (pinfunction "1_1") (pintype "passive"))
    )
    (net (code "151") (name "Net-(OK7-C)") (class "Default")
      (node (ref "OK7") (pin "2") (pinfunction "C_2") (pintype "passive"))
      (node (ref "R40") (pin "2") (pinfunction "2_2") (pintype "passive"))
    )
    (net (code "152") (name "Net-(OK7-EMIT)") (class "Default")
      (node (ref "OK7") (pin "3") (pinfunction "EMIT_3") (pintype "passive"))
      (node (ref "R41") (pin "1") (pinfunction "1_1") (pintype "passive"))
    )
    (net (code "153") (name "Net-(OK8-C)") (class "Default")
      (node (ref "OK8") (pin "2") (pinfunction "C_2") (pintype "passive"))
      (node (ref "R43") (pin "2") (pinfunction "2_2") (pintype "passive"))
    )
    (net (code "154") (name "Net-(OK8-EMIT)") (class "Default")
      (node (ref "OK8") (pin "3") (pinfunction "EMIT_3") (pintype "passive"))
      (node (ref "R44") (pin "1") (pinfunction "1_1") (pintype "passive"))
    )
    (net (code "155") (name "Net-(OK9-C)") (class "Default")
      (node (ref "OK9") (pin "2") (pinfunction "C_2") (pintype "passive"))
      (node (ref "R46") (pin "2") (pinfunction "2_2") (pintype "passive"))
    )
    (net (code "156") (name "Net-(OK9-EMIT)") (class "Default")
      (node (ref "OK9") (pin "3") (pinfunction "EMIT_3") (pintype "passive"))
      (node (ref "R47") (pin "1") (pinfunction "1_1") (pintype "passive"))
    )
    (net (code "157") (name "Net-(OK10-C)") (class "Default")
      (node (ref "OK10") (pin "2") (pinfunction "C_2") (pintype "passive"))
      (node (ref "R49") (pin "2") (pinfunction "2_2") (pintype "passive"))
    )
    (net (code "158") (name "Net-(OK10-EMIT)") (class "Default")
      (node (ref "OK10") (pin "3") (pinfunction "EMIT_3") (pintype "passive"))
      (node (ref "R50") (pin "1") (pinfunction "1_1") (pintype "passive"))
    )
    (net (code "159") (name "Net-(OK11-C)") (class "Default")
      (node (ref "OK11") (pin "2") (pinfunction "C_2") (pintype "passive"))
      (node (ref "R53") (pin "2") (pinfunction "2_2") (pintype "passive"))
    )
    (net (code "160") (name "Net-(OK11-EMIT)") (class "Default")
      (node (ref "OK11") (pin "3") (pinfunction "EMIT_3") (pintype "passive"))
      (node (ref "R54") (pin "1") (pinfunction "1_1") (pintype "passive"))
    )
    (net (code "161") (name "Net-(OK12-C)") (class "Default")
      (node (ref "OK12") (pin "2") (pinfunction "C_2") (pintype "passive"))
      (node (ref "R56") (pin "2") (pinfunction "2_2") (pintype "passive"))
    )
    (net (code "162") (name "Net-(OK12-EMIT)") (class "Default")
      (node (ref "OK12") (pin "3") (pinfunction "EMIT_3") (pintype "passive"))
      (node (ref "R57") (pin "1") (pinfunction "1_1") (pintype "passive"))
    )
    (net (code "163") (name "Net-(OK13-C)") (class "Default")
      (node (ref "OK13") (pin "2") (pinfunction "C_2") (pintype "passive"))
      (node (ref "R59") (pin "2") (pinfunction "2_2") (pintype "passive"))
    )
    (net (code "164") (name "Net-(OK13-EMIT)") (class "Default")
      (node (ref "OK13") (pin "3") (pinfunction "EMIT_3") (pintype "passive"))
      (node (ref "R60") (pin "1") (pinfunction "1_1") (pintype "passive"))
    )
    (net (code "165") (name "Net-(OK14-C)") (class "Default")
      (node (ref "OK14") (pin "2") (pinfunction "C_2") (pintype "passive"))
      (node (ref "R62") (pin "2") (pinfunction "2_2") (pintype "passive"))
    )
    (net (code "166") (name "Net-(OK14-EMIT)") (class "Default")
      (node (ref "OK14") (pin "3") (pinfunction "EMIT_3") (pintype "passive"))
      (node (ref "R63") (pin "1") (pinfunction "1_1") (pintype "passive"))
    )
    (net (code "167") (name "Net-(OK15-C)") (class "Default")
      (node (ref "OK15") (pin "2") (pinfunction "C_2") (pintype "passive"))
      (node (ref "R65") (pin "2") (pinfunction "2_2") (pintype "passive"))
    )
    (net (code "168") (name "Net-(OK15-EMIT)") (class "Default")
      (node (ref "OK15") (pin "3") (pinfunction "EMIT_3") (pintype "passive"))
      (node (ref "R66") (pin "1") (pinfunction "1_1") (pintype "passive"))
    )
    (net (code "169") (name "Net-(OK16-C)") (class "Default")
      (node (ref "OK16") (pin "2") (pinfunction "C_2") (pintype "passive"))
      (node (ref "R68") (pin "2") (pinfunction "2_2") (pintype "passive"))
    )
    (net (code "170") (name "Net-(OK16-EMIT)") (class "Default")
      (node (ref "OK16") (pin "3") (pinfunction "EMIT_3") (pintype "passive"))
      (node (ref "R69") (pin "1") (pinfunction "1_1") (pintype "passive"))
    )
    (net (code "171") (name "Net-(OK17-C)") (class "Default")
      (node (ref "OK17") (pin "2") (pinfunction "C_2") (pintype "passive"))
      (node (ref "R71") (pin "2") (pinfunction "2_2") (pintype "passive"))
    )
    (net (code "172") (name "Net-(OK17-EMIT)") (class "Default")
      (node (ref "OK17") (pin "3") (pinfunction "EMIT_3") (pintype "passive"))
      (node (ref "R72") (pin "1") (pinfunction "1_1") (pintype "passive"))
    )
    (net (code "173") (name "Net-(OK18-C)") (class "Default")
      (node (ref "OK18") (pin "2") (pinfunction "C_2") (pintype "passive"))
      (node (ref "R74") (pin "2") (pinfunction "2_2") (pintype "passive"))
    )
    (net (code "174") (name "Net-(OK18-EMIT)") (class "Default")
      (node (ref "OK18") (pin "3") (pinfunction "EMIT_3") (pintype "passive"))
      (node (ref "R75") (pin "1") (pinfunction "1_1") (pintype "passive"))
    )
    (net (code "175") (name "Net-(OK19-C)") (class "Default")
      (node (ref "OK19") (pin "2") (pinfunction "C_2") (pintype "passive"))
      (node (ref "R77") (pin "2") (pinfunction "2_2") (pintype "passive"))
    )
    (net (code "176") (name "Net-(OK19-EMIT)") (class "Default")
      (node (ref "OK19") (pin "3") (pinfunction "EMIT_3") (pintype "passive"))
      (node (ref "R78") (pin "1") (pinfunction "1_1") (pintype "passive"))
    )
    (net (code "177") (name "Net-(OK20-C)") (class "Default")
      (node (ref "OK20") (pin "2") (pinfunction "C_2") (pintype "passive"))
      (node (ref "R80") (pin "2") (pinfunction "2_2") (pintype "passive"))
    )
    (net (code "178") (name "Net-(OK20-EMIT)") (class "Default")
      (node (ref "OK20") (pin "3") (pinfunction "EMIT_3") (pintype "passive"))
      (node (ref "R81") (pin "1") (pinfunction "1_1") (pintype "passive"))
    )
    (net (code "179") (name "Net-(OK21-C)") (class "Default")
      (node (ref "OK21") (pin "2") (pinfunction "C_2") (pintype "passive"))
      (node (ref "R83") (pin "2") (pinfunction "2_2") (pintype "passive"))
    )
    (net (code "180") (name "Net-(OK21-EMIT)") (class "Default")
      (node (ref "OK21") (pin "3") (pinfunction "EMIT_3") (pintype "passive"))
      (node (ref "R84") (pin "1") (pinfunction "1_1") (pintype "passive"))
    )
    (net (code "181") (name "Net-(OK22-C)") (class "Default")
      (node (ref "OK22") (pin "2") (pinfunction "C_2") (pintype "passive"))
      (node (ref "R86") (pin "2") (pinfunction "2_2") (pintype "passive"))
    )
    (net (code "182") (name "Net-(OK22-EMIT)") (class "Default")
      (node (ref "OK22") (pin "3") (pinfunction "EMIT_3") (pintype "passive"))
      (node (ref "R87") (pin "1") (pinfunction "1_1") (pintype "passive"))
    )
    (net (code "183") (name "Net-(OK23-C)") (class "Default")
      (node (ref "OK23") (pin "2") (pinfunction "C_2") (pintype "passive"))
      (node (ref "R89") (pin "2") (pinfunction "2_2") (pintype "passive"))
    )
    (net (code "184") (name "Net-(OK23-EMIT)") (class "Default")
      (node (ref "OK23") (pin "3") (pinfunction "EMIT_3") (pintype "passive"))
      (node (ref "R90") (pin "1") (pinfunction "1_1") (pintype "passive"))
    )
    (net (code "185") (name "Net-(OK24-C)") (class "Default")
      (node (ref "OK24") (pin "2") (pinfunction "C_2") (pintype "passive"))
      (node (ref "R92") (pin "2") (pinfunction "2_2") (pintype "passive"))
    )
    (net (code "186") (name "Net-(OK24-EMIT)") (class "Default")
      (node (ref "OK24") (pin "3") (pinfunction "EMIT_3") (pintype "passive"))
      (node (ref "R93") (pin "1") (pinfunction "1_1") (pintype "passive"))
    )
    (net (code "187") (name "Net-(OK25-C)") (class "Default")
      (node (ref "OK25") (pin "2") (pinfunction "C_2") (pintype "passive"))
      (node (ref "R35") (pin "2") (pinfunction "2_2") (pintype "passive"))
    )
    (net (code "188") (name "Net-(OK25-EMIT)") (class "Default")
      (node (ref "OK25") (pin "3") (pinfunction "EMIT_3") (pintype "passive"))
      (node (ref "R39") (pin "1") (pinfunction "1_1") (pintype "passive"))
    )
    (net (code "189") (name "Net-(OK26-C)") (class "Default")
      (node (ref "OK26") (pin "2") (pinfunction "C_2") (pintype "passive"))
      (node (ref "R45") (pin "2") (pinfunction "2_2") (pintype "passive"))
    )
    (net (code "190") (name "Net-(OK26-EMIT)") (class "Default")
      (node (ref "OK26") (pin "3") (pinfunction "EMIT_3") (pintype "passive"))
      (node (ref "R48") (pin "1") (pinfunction "1_1") (pintype "passive"))
    )
    (net (code "191") (name "Net-(OK27-C)") (class "Default")
      (node (ref "OK27") (pin "2") (pinfunction "C_2") (pintype "passive"))
      (node (ref "R55") (pin "2") (pinfunction "2_2") (pintype "passive"))
    )
    (net (code "192") (name "Net-(OK27-EMIT)") (class "Default")
      (node (ref "OK27") (pin "3") (pinfunction "EMIT_3") (pintype "passive"))
      (node (ref "R58") (pin "1") (pinfunction "1_1") (pintype "passive"))
    )
    (net (code "193") (name "Net-(OK28-C)") (class "Default")
      (node (ref "OK28") (pin "2") (pinfunction "C_2") (pintype "passive"))
      (node (ref "R64") (pin "2") (pinfunction "2_2") (pintype "passive"))
    )
    (net (code "194") (name "Net-(OK28-EMIT)") (class "Default")
      (node (ref "OK28") (pin "3") (pinfunction "EMIT_3") (pintype "passive"))
      (node (ref "R67") (pin "1") (pinfunction "1_1") (pintype "passive"))
    )
    (net (code "195") (name "Net-(Q1-2)") (class "Default")
      (node (ref "C19") (pin "1") (pinfunction "1_1") (pintype "passive"))
      (node (ref "Q1") (pin "3") (pinfunction "2_3") (pintype "passive"))
      (node (ref "R52") (pin "1") (pinfunction "1_1") (pintype "passive"))
      (node (ref "U2") (pin "30") (pinfunction "XI/CLKIN_30") (pintype "passive"))
    )
    (net (code "196") (name "Net-(Q2-B)") (class "Default")
      (node (ref "Q2") (pin "1") (pinfunction "B_1") (pintype "passive"))
      (node (ref "R18") (pin "1") (pinfunction "1_1") (pintype "passive"))
    )
    (net (code "197") (name "Net-(Q2-C)") (class "Default")
      (node (ref "Q2") (pin "3") (pinfunction "C_3") (pintype "passive"))
      (node (ref "R23") (pin "2") (pinfunction "2_2") (pintype "passive"))
    )
    (net (code "198") (name "Net-(Q5-2)") (class "Default")
      (node (ref "C47") (pin "1") (pinfunction "1_1") (pintype "passive"))
      (node (ref "Q5") (pin "3") (pinfunction "2_3") (pintype "passive"))
      (node (ref "U$1") (pin "7") (pinfunction "XI_7") (pintype "bidirectional"))
    )
    (net (code "199") (name "Net-(R1-Pad1)") (class "Default")
      (node (ref "R1") (pin "1") (pinfunction "1_1") (pintype "passive"))
      (node (ref "R30") (pin "2") (pinfunction "2_2") (pintype "passive"))
    )
    (net (code "200") (name "Net-(RN1B-1)") (class "Default")
      (node (ref "RN1") (pin "2") (pinfunction "1_2") (pintype "passive"))
      (node (ref "U2") (pin "44") (pinfunction "PMODE1_44") (pintype "passive"))
    )
    (net (code "201") (name "Net-(RN1C-1)") (class "Default")
      (node (ref "RN1") (pin "3") (pinfunction "1_3") (pintype "passive"))
      (node (ref "U2") (pin "43") (pinfunction "PMODE2_43") (pintype "passive"))
    )
    (net (code "202") (name "Net-(RN1D-1)") (class "Default")
      (node (ref "RN1") (pin "4") (pinfunction "1_4") (pintype "passive"))
      (node (ref "U2") (pin "42") (pinfunction "RSVD_42") (pintype "passive"))
    )
    (net (code "203") (name "Net-(RN2-Pad1)") (class "Default")
      (node (ref "RN2") (pin "1") (pinfunction "1_1") (pintype "passive"))
      (node (ref "U2") (pin "41") (pinfunction "RSVD_41") (pintype "passive"))
    )
    (net (code "204") (name "Net-(RN2B-1)") (class "Default")
      (node (ref "RN2") (pin "2") (pinfunction "1_2") (pintype "passive"))
      (node (ref "U2") (pin "40") (pinfunction "RSVD_40") (pintype "passive"))
    )
    (net (code "205") (name "Net-(RN2C-1)") (class "Default")
      (node (ref "RN2") (pin "3") (pinfunction "1_3") (pintype "passive"))
      (node (ref "U2") (pin "39") (pinfunction "RSVD_39") (pintype "passive"))
    )
    (net (code "206") (name "Net-(RN2D-1)") (class "Default")
      (node (ref "RN2") (pin "4") (pinfunction "1_4") (pintype "passive"))
      (node (ref "U2") (pin "38") (pinfunction "RSVD_38") (pintype "passive"))
    )
    (net (code "207") (name "Net-(U$1-DTR)") (class "Default")
      (node (ref "R13") (pin "2") (pinfunction "2_2") (pintype "passive"))
      (node (ref "U$1") (pin "13") (pinfunction "DTR_13") (pintype "bidirectional"))
    )
    (net (code "208") (name "Net-(U$1-RTS)") (class "Default")
      (node (ref "R18") (pin "2") (pinfunction "2_2") (pintype "passive"))
      (node (ref "U$1") (pin "14") (pinfunction "RTS_14") (pintype "bidirectional"))
      (node (ref "U26") (pin "P$2") (pinfunction "EMITTER_P$2") (pintype "bidirectional"))
    )
    (net (code "209") (name "Net-(U$1-V3)") (class "Default")
      (node (ref "C46") (pin "2") (pinfunction "2_2") (pintype "passive"))
      (node (ref "U$1") (pin "4") (pinfunction "V3_4") (pintype "bidirectional"))
    )
    (net (code "210") (name "Net-(U$1-XO)") (class "Default")
      (node (ref "C48") (pin "1") (pinfunction "1_1") (pintype "passive"))
      (node (ref "Q5") (pin "1") (pinfunction "1_1") (pintype "passive"))
      (node (ref "U$1") (pin "8") (pinfunction "XO_8") (pintype "bidirectional"))
    )
    (net (code "211") (name "Net-(U1-BASE)") (class "Default")
      (node (ref "R7") (pin "2") (pinfunction "2_2") (pintype "passive"))
      (node (ref "U1") (pin "P$1") (pinfunction "BASE_P$1") (pintype "bidirectional"))
    )
    (net (code "212") (name "Net-(U1-COLLECTOR)") (class "Default")
      (node (ref "D1") (pin "A") (pinfunction "A_A") (pintype "passive"))
      (node (ref "LED19") (pin "C") (pinfunction "C_C") (pintype "passive"))
      (node (ref "U1") (pin "P$3") (pinfunction "COLLECTOR_P$3") (pintype "bidirectional"))
      (node (ref "X1") (pin "1") (pinfunction "K_1") (pintype "passive"))
    )
    (net (code "213") (name "Net-(U2-1V2O)") (class "Default")
      (node (ref "C9") (pin "1") (pinfunction "1_1") (pintype "passive"))
      (node (ref "U2") (pin "22") (pinfunction "1V2O_22") (pintype "passive"))
    )
    (net (code "214") (name "Net-(U2-EXRES1)") (class "Default")
      (node (ref "R30") (pin "1") (pinfunction "1_1") (pintype "passive"))
      (node (ref "U2") (pin "10") (pinfunction "EXRES1_10") (pintype "passive"))
    )
    (net (code "215") (name "Net-(U2-PMODE0)") (class "Default")
      (node (ref "RN1") (pin "1") (pinfunction "1_1") (pintype "passive"))
      (node (ref "U2") (pin "45") (pinfunction "PMODE0_45") (pintype "passive"))
    )
    (net (code "216") (name "Net-(U2-RXN)") (class "Default")
      (node (ref "R16") (pin "1") (pinfunction "1_1") (pintype "passive"))
      (node (ref "U2") (pin "5") (pinfunction "RXN_5") (pintype "passive"))
    )
    (net (code "217") (name "Net-(U2-RXP)") (class "Default")
      (node (ref "R14") (pin "1") (pinfunction "1_1") (pintype "passive"))
      (node (ref "U2") (pin "6") (pinfunction "RXP_6") (pintype "passive"))
    )
    (net (code "218") (name "Net-(U2-TOCAP)") (class "Default")
      (node (ref "C10") (pin "1") (pinfunction "1_1") (pintype "passive"))
      (node (ref "U2") (pin "20") (pinfunction "TOCAP_20") (pintype "passive"))
    )
    (net (code "219") (name "Net-(U2-TXN)") (class "Default")
      (node (ref "R12") (pin "1") (pinfunction "1_1") (pintype "passive"))
      (node (ref "U2") (pin "1") (pinfunction "TXN_1") (pintype "passive"))
    )
    (net (code "220") (name "Net-(U2-TXP)") (class "Default")
      (node (ref "R10") (pin "1") (pinfunction "1_1") (pintype "passive"))
      (node (ref "U2") (pin "2") (pinfunction "TXP_2") (pintype "passive"))
    )
    (net (code "221") (name "Net-(U2-XO)") (class "Default")
      (node (ref "C18") (pin "1") (pinfunction "1_1") (pintype "passive"))
      (node (ref "Q1") (pin "1") (pinfunction "1_1") (pintype "passive"))
      (node (ref "R52") (pin "2") (pinfunction "2_2") (pintype "passive"))
      (node (ref "U2") (pin "31") (pinfunction "XO_31") (pintype "passive"))
    )
    (net (code "222") (name "Net-(U3-BASE)") (class "Default")
      (node (ref "R17") (pin "2") (pinfunction "2_2") (pintype "passive"))
      (node (ref "U3") (pin "P$1") (pinfunction "BASE_P$1") (pintype "bidirectional"))
    )
    (net (code "223") (name "Net-(U3-COLLECTOR)") (class "Default")
      (node (ref "D2") (pin "A") (pinfunction "A_A") (pintype "passive"))
      (node (ref "LED2") (pin "C") (pinfunction "C_C") (pintype "passive"))
      (node (ref "U3") (pin "P$3") (pinfunction "COLLECTOR_P$3") (pintype "bidirectional"))
      (node (ref "X1") (pin "2") (pinfunction "K_2") (pintype "passive"))
    )
    (net (code "224") (name "Net-(U4-BASE)") (class "Default")
      (node (ref "R21") (pin "2") (pinfunction "2_2") (pintype "passive"))
      (node (ref "U4") (pin "P$1") (pinfunction "BASE_P$1") (pintype "bidirectional"))
    )
    (net (code "225") (name "Net-(U4-COLLECTOR)") (class "Default")
      (node (ref "D3") (pin "A") (pinfunction "A_A") (pintype "passive"))
      (node (ref "LED3") (pin "C") (pinfunction "C_C") (pintype "passive"))
      (node (ref "U4") (pin "P$3") (pinfunction "COLLECTOR_P$3") (pintype "bidirectional"))
      (node (ref "X1") (pin "3") (pinfunction "K_3") (pintype "passive"))
    )
    (net (code "226") (name "Net-(U5-BASE)") (class "Default")
      (node (ref "R27") (pin "2") (pinfunction "2_2") (pintype "passive"))
      (node (ref "U5") (pin "P$1") (pinfunction "BASE_P$1") (pintype "bidirectional"))
    )
    (net (code "227") (name "Net-(U5-COLLECTOR)") (class "Default")
      (node (ref "D4") (pin "A") (pinfunction "A_A") (pintype "passive"))
      (node (ref "LED4") (pin "C") (pinfunction "C_C") (pintype "passive"))
      (node (ref "U5") (pin "P$3") (pinfunction "COLLECTOR_P$3") (pintype "bidirectional"))
      (node (ref "X1") (pin "4") (pinfunction "K_4") (pintype "passive"))
    )
    (net (code "228") (name "Net-(U6-BASE)") (class "Default")
      (node (ref "R33") (pin "2") (pinfunction "2_2") (pintype "passive"))
      (node (ref "U6") (pin "P$1") (pinfunction "BASE_P$1") (pintype "bidirectional"))
    )
    (net (code "229") (name "Net-(U6-COLLECTOR)") (class "Default")
      (node (ref "D5") (pin "A") (pinfunction "A_A") (pintype "passive"))
      (node (ref "LED5") (pin "C") (pinfunction "C_C") (pintype "passive"))
      (node (ref "U6") (pin "P$3") (pinfunction "COLLECTOR_P$3") (pintype "bidirectional"))
      (node (ref "X1") (pin "5") (pinfunction "K_5") (pintype "passive"))
    )
    (net (code "230") (name "Net-(U7-BASE)") (class "Default")
      (node (ref "R38") (pin "2") (pinfunction "2_2") (pintype "passive"))
      (node (ref "U7") (pin "P$1") (pinfunction "BASE_P$1") (pintype "bidirectional"))
    )
    (net (code "231") (name "Net-(U7-COLLECTOR)") (class "Default")
      (node (ref "D6") (pin "A") (pinfunction "A_A") (pintype "passive"))
      (node (ref "LED6") (pin "C") (pinfunction "C_C") (pintype "passive"))
      (node (ref "U7") (pin "P$3") (pinfunction "COLLECTOR_P$3") (pintype "bidirectional"))
      (node (ref "X1") (pin "6") (pinfunction "K_6") (pintype "passive"))
    )
    (net (code "232") (name "Net-(U8-BASE)") (class "Default")
      (node (ref "R41") (pin "2") (pinfunction "2_2") (pintype "passive"))
      (node (ref "U8") (pin "P$1") (pinfunction "BASE_P$1") (pintype "bidirectional"))
    )
    (net (code "233") (name "Net-(U8-COLLECTOR)") (class "Default")
      (node (ref "D7") (pin "A") (pinfunction "A_A") (pintype "passive"))
      (node (ref "LED7") (pin "C") (pinfunction "C_C") (pintype "passive"))
      (node (ref "U8") (pin "P$3") (pinfunction "COLLECTOR_P$3") (pintype "bidirectional"))
      (node (ref "X1") (pin "7") (pinfunction "K_7") (pintype "passive"))
    )
    (net (code "234") (name "Net-(U9-BASE)") (class "Default")
      (node (ref "R44") (pin "2") (pinfunction "2_2") (pintype "passive"))
      (node (ref "U9") (pin "P$1") (pinfunction "BASE_P$1") (pintype "bidirectional"))
    )
    (net (code "235") (name "Net-(U9-COLLECTOR)") (class "Default")
      (node (ref "D8") (pin "A") (pinfunction "A_A") (pintype "passive"))
      (node (ref "LED8") (pin "C") (pinfunction "C_C") (pintype "passive"))
      (node (ref "U9") (pin "P$3") (pinfunction "COLLECTOR_P$3") (pintype "bidirectional"))
      (node (ref "X1") (pin "8") (pinfunction "K_8") (pintype "passive"))
    )
    (net (code "236") (name "Net-(U10-BASE)") (class "Default")
      (node (ref "R47") (pin "2") (pinfunction "2_2") (pintype "passive"))
      (node (ref "U10") (pin "P$1") (pinfunction "BASE_P$1") (pintype "bidirectional"))
    )
    (net (code "237") (name "Net-(U10-COLLECTOR)") (class "Default")
      (node (ref "D9") (pin "A") (pinfunction "A_A") (pintype "passive"))
      (node (ref "LED9") (pin "C") (pinfunction "C_C") (pintype "passive"))
      (node (ref "U10") (pin "P$3") (pinfunction "COLLECTOR_P$3") (pintype "bidirectional"))
      (node (ref "X7") (pin "1") (pinfunction "K_1") (pintype "passive"))
    )
    (net (code "238") (name "Net-(U11-BASE)") (class "Default")
      (node (ref "R50") (pin "2") (pinfunction "2_2") (pintype "passive"))
      (node (ref "U11") (pin "P$1") (pinfunction "BASE_P$1") (pintype "bidirectional"))
    )
    (net (code "239") (name "Net-(U11-COLLECTOR)") (class "Default")
      (node (ref "D10") (pin "A") (pinfunction "A_A") (pintype "passive"))
      (node (ref "LED10") (pin "C") (pinfunction "C_C") (pintype "passive"))
      (node (ref "U11") (pin "P$3") (pinfunction "COLLECTOR_P$3") (pintype "bidirectional"))
      (node (ref "X7") (pin "2") (pinfunction "K_2") (pintype "passive"))
    )
    (net (code "240") (name "Net-(U12-BASE)") (class "Default")
      (node (ref "R54") (pin "2") (pinfunction "2_2") (pintype "passive"))
      (node (ref "U12") (pin "P$1") (pinfunction "BASE_P$1") (pintype "bidirectional"))
    )
    (net (code "241") (name "Net-(U12-COLLECTOR)") (class "Default")
      (node (ref "D11") (pin "A") (pinfunction "A_A") (pintype "passive"))
      (node (ref "LED11") (pin "C") (pinfunction "C_C") (pintype "passive"))
      (node (ref "U12") (pin "P$3") (pinfunction "COLLECTOR_P$3") (pintype "bidirectional"))
      (node (ref "X7") (pin "3") (pinfunction "K_3") (pintype "passive"))
    )
    (net (code "242") (name "Net-(U13-BASE)") (class "Default")
      (node (ref "R57") (pin "2") (pinfunction "2_2") (pintype "passive"))
      (node (ref "U13") (pin "P$1") (pinfunction "BASE_P$1") (pintype "bidirectional"))
    )
    (net (code "243") (name "Net-(U13-COLLECTOR)") (class "Default")
      (node (ref "D12") (pin "A") (pinfunction "A_A") (pintype "passive"))
      (node (ref "LED12") (pin "C") (pinfunction "C_C") (pintype "passive"))
      (node (ref "U13") (pin "P$3") (pinfunction "COLLECTOR_P$3") (pintype "bidirectional"))
      (node (ref "X7") (pin "4") (pinfunction "K_4") (pintype "passive"))
    )
    (net (code "244") (name "Net-(U14-BASE)") (class "Default")
      (node (ref "R60") (pin "2") (pinfunction "2_2") (pintype "passive"))
      (node (ref "U14") (pin "P$1") (pinfunction "BASE_P$1") (pintype "bidirectional"))
    )
    (net (code "245") (name "Net-(U14-COLLECTOR)") (class "Default")
      (node (ref "D13") (pin "A") (pinfunction "A_A") (pintype "passive"))
      (node (ref "LED13") (pin "C") (pinfunction "C_C") (pintype "passive"))
      (node (ref "U14") (pin "P$3") (pinfunction "COLLECTOR_P$3") (pintype "bidirectional"))
      (node (ref "X7") (pin "5") (pinfunction "K_5") (pintype "passive"))
    )
    (net (code "246") (name "Net-(U15-BASE)") (class "Default")
      (node (ref "R63") (pin "2") (pinfunction "2_2") (pintype "passive"))
      (node (ref "U15") (pin "P$1") (pinfunction "BASE_P$1") (pintype "bidirectional"))
    )
    (net (code "247") (name "Net-(U15-COLLECTOR)") (class "Default")
      (node (ref "D14") (pin "A") (pinfunction "A_A") (pintype "passive"))
      (node (ref "LED14") (pin "C") (pinfunction "C_C") (pintype "passive"))
      (node (ref "U15") (pin "P$3") (pinfunction "COLLECTOR_P$3") (pintype "bidirectional"))
      (node (ref "X7") (pin "6") (pinfunction "K_6") (pintype "passive"))
    )
    (net (code "248") (name "Net-(U16-BASE)") (class "Default")
      (node (ref "R66") (pin "2") (pinfunction "2_2") (pintype "passive"))
      (node (ref "U16") (pin "P$1") (pinfunction "BASE_P$1") (pintype "bidirectional"))
    )
    (net (code "249") (name "Net-(U16-COLLECTOR)") (class "Default")
      (node (ref "D15") (pin "A") (pinfunction "A_A") (pintype "passive"))
      (node (ref "LED15") (pin "C") (pinfunction "C_C") (pintype "passive"))
      (node (ref "U16") (pin "P$3") (pinfunction "COLLECTOR_P$3") (pintype "bidirectional"))
      (node (ref "X7") (pin "7") (pinfunction "K_7") (pintype "passive"))
    )
    (net (code "250") (name "Net-(U17-BASE)") (class "Default")
      (node (ref "R69") (pin "2") (pinfunction "2_2") (pintype "passive"))
      (node (ref "U17") (pin "P$1") (pinfunction "BASE_P$1") (pintype "bidirectional"))
    )
    (net (code "251") (name "Net-(U17-COLLECTOR)") (class "Default")
      (node (ref "D16") (pin "A") (pinfunction "A_A") (pintype "passive"))
      (node (ref "LED16") (pin "C") (pinfunction "C_C") (pintype "passive"))
      (node (ref "U17") (pin "P$3") (pinfunction "COLLECTOR_P$3") (pintype "bidirectional"))
      (node (ref "X7") (pin "8") (pinfunction "K_8") (pintype "passive"))
    )
    (net (code "252") (name "Net-(U18-BASE)") (class "Default")
      (node (ref "R72") (pin "2") (pinfunction "2_2") (pintype "passive"))
      (node (ref "U18") (pin "P$1") (pinfunction "BASE_P$1") (pintype "bidirectional"))
    )
    (net (code "253") (name "Net-(U18-COLLECTOR)") (class "Default")
      (node (ref "D17") (pin "A") (pinfunction "A_A") (pintype "passive"))
      (node (ref "LED17") (pin "C") (pinfunction "C_C") (pintype "passive"))
      (node (ref "U18") (pin "P$3") (pinfunction "COLLECTOR_P$3") (pintype "bidirectional"))
      (node (ref "X8") (pin "1") (pinfunction "K_1") (pintype "passive"))
    )
    (net (code "254") (name "Net-(U19-BASE)") (class "Default")
      (node (ref "R75") (pin "2") (pinfunction "2_2") (pintype "passive"))
      (node (ref "U19") (pin "P$1") (pinfunction "BASE_P$1") (pintype "bidirectional"))
    )
    (net (code "255") (name "Net-(U19-COLLECTOR)") (class "Default")
      (node (ref "D18") (pin "A") (pinfunction "A_A") (pintype "passive"))
      (node (ref "LED18") (pin "C") (pinfunction "C_C") (pintype "passive"))
      (node (ref "U19") (pin "P$3") (pinfunction "COLLECTOR_P$3") (pintype "bidirectional"))
      (node (ref "X8") (pin "2") (pinfunction "K_2") (pintype "passive"))
    )
    (net (code "256") (name "Net-(U20-BASE)") (class "Default")
      (node (ref "R78") (pin "2") (pinfunction "2_2") (pintype "passive"))
      (node (ref "U20") (pin "P$1") (pinfunction "BASE_P$1") (pintype "bidirectional"))
    )
    (net (code "257") (name "Net-(U20-COLLECTOR)") (class "Default")
      (node (ref "D19") (pin "A") (pinfunction "A_A") (pintype "passive"))
      (node (ref "LED20") (pin "C") (pinfunction "C_C") (pintype "passive"))
      (node (ref "U20") (pin "P$3") (pinfunction "COLLECTOR_P$3") (pintype "bidirectional"))
      (node (ref "X8") (pin "3") (pinfunction "K_3") (pintype "passive"))
    )
    (net (code "258") (name "Net-(U21-BASE)") (class "Default")
      (node (ref "R81") (pin "2") (pinfunction "2_2") (pintype "passive"))
      (node (ref "U21") (pin "P$1") (pinfunction "BASE_P$1") (pintype "bidirectional"))
    )
    (net (code "259") (name "Net-(U21-COLLECTOR)") (class "Default")
      (node (ref "D20") (pin "A") (pinfunction "A_A") (pintype "passive"))
      (node (ref "LED21") (pin "C") (pinfunction "C_C") (pintype "passive"))
      (node (ref "U21") (pin "P$3") (pinfunction "COLLECTOR_P$3") (pintype "bidirectional"))
      (node (ref "X8") (pin "4") (pinfunction "K_4") (pintype "passive"))
    )
    (net (code "260") (name "Net-(U22-BASE)") (class "Default")
      (node (ref "R84") (pin "2") (pinfunction "2_2") (pintype "passive"))
      (node (ref "U22") (pin "P$1") (pinfunction "BASE_P$1") (pintype "bidirectional"))
    )
    (net (code "261") (name "Net-(U22-COLLECTOR)") (class "Default")
      (node (ref "D21") (pin "A") (pinfunction "A_A") (pintype "passive"))
      (node (ref "LED22") (pin "C") (pinfunction "C_C") (pintype "passive"))
      (node (ref "U22") (pin "P$3") (pinfunction "COLLECTOR_P$3") (pintype "bidirectional"))
      (node (ref "X8") (pin "5") (pinfunction "K_5") (pintype "passive"))
    )
    (net (code "262") (name "Net-(U23-BASE)") (class "Default")
      (node (ref "R87") (pin "2") (pinfunction "2_2") (pintype "passive"))
      (node (ref "U23") (pin "P$1") (pinfunction "BASE_P$1") (pintype "bidirectional"))
    )
    (net (code "263") (name "Net-(U23-COLLECTOR)") (class "Default")
      (node (ref "D22") (pin "A") (pinfunction "A_A") (pintype "passive"))
      (node (ref "LED23") (pin "C") (pinfunction "C_C") (pintype "passive"))
      (node (ref "U23") (pin "P$3") (pinfunction "COLLECTOR_P$3") (pintype "bidirectional"))
      (node (ref "X8") (pin "6") (pinfunction "K_6") (pintype "passive"))
    )
    (net (code "264") (name "Net-(U24-BASE)") (class "Default")
      (node (ref "R90") (pin "2") (pinfunction "2_2") (pintype "passive"))
      (node (ref "U24") (pin "P$1") (pinfunction "BASE_P$1") (pintype "bidirectional"))
    )
    (net (code "265") (name "Net-(U24-COLLECTOR)") (class "Default")
      (node (ref "D23") (pin "A") (pinfunction "A_A") (pintype "passive"))
      (node (ref "LED24") (pin "C") (pinfunction "C_C") (pintype "passive"))
      (node (ref "U24") (pin "P$3") (pinfunction "COLLECTOR_P$3") (pintype "bidirectional"))
      (node (ref "X8") (pin "7") (pinfunction "K_7") (pintype "passive"))
    )
    (net (code "266") (name "Net-(U25-BASE)") (class "Default")
      (node (ref "R93") (pin "2") (pinfunction "2_2") (pintype "passive"))
      (node (ref "U25") (pin "P$1") (pinfunction "BASE_P$1") (pintype "bidirectional"))
    )
    (net (code "267") (name "Net-(U25-COLLECTOR)") (class "Default")
      (node (ref "D24") (pin "A") (pinfunction "A_A") (pintype "passive"))
      (node (ref "LED25") (pin "C") (pinfunction "C_C") (pintype "passive"))
      (node (ref "U25") (pin "P$3") (pinfunction "COLLECTOR_P$3") (pintype "bidirectional"))
      (node (ref "X8") (pin "8") (pinfunction "K_8") (pintype "passive"))
    )
    (net (code "268") (name "Net-(U26-BASE)") (class "Default")
      (node (ref "R13") (pin "1") (pinfunction "1_1") (pintype "passive"))
      (node (ref "U26") (pin "P$1") (pinfunction "BASE_P$1") (pintype "bidirectional"))
    )
    (net (code "269") (name "Net-(U26-COLLECTOR)") (class "Default")
      (node (ref "D26") (pin "C") (pinfunction "C_C") (pintype "passive"))
      (node (ref "R29") (pin "1") (pinfunction "1_1") (pintype "passive"))
      (node (ref "U26") (pin "P$3") (pinfunction "COLLECTOR_P$3") (pintype "bidirectional"))
    )
    (net (code "270") (name "Net-(U27-BASE)") (class "Default")
      (node (ref "R39") (pin "2") (pinfunction "2_2") (pintype "passive"))
      (node (ref "U27") (pin "P$1") (pinfunction "BASE_P$1") (pintype "bidirectional"))
    )
    (net (code "271") (name "Net-(U27-COLLECTOR)") (class "Default")
      (node (ref "D27") (pin "A") (pinfunction "A_A") (pintype "passive"))
      (node (ref "LED26") (pin "C") (pinfunction "C_C") (pintype "passive"))
      (node (ref "U27") (pin "P$3") (pinfunction "COLLECTOR_P$3") (pintype "bidirectional"))
      (node (ref "X5") (pin "1") (pinfunction "K_1") (pintype "passive"))
    )
    (net (code "272") (name "Net-(U28-BASE)") (class "Default")
      (node (ref "R48") (pin "2") (pinfunction "2_2") (pintype "passive"))
      (node (ref "U28") (pin "P$1") (pinfunction "BASE_P$1") (pintype "bidirectional"))
    )
    (net (code "273") (name "Net-(U28-COLLECTOR)") (class "Default")
      (node (ref "D28") (pin "A") (pinfunction "A_A") (pintype "passive"))
      (node (ref "LED27") (pin "C") (pinfunction "C_C") (pintype "passive"))
      (node (ref "U28") (pin "P$3") (pinfunction "COLLECTOR_P$3") (pintype "bidirectional"))
      (node (ref "X5") (pin "2") (pinfunction "K_2") (pintype "passive"))
    )
    (net (code "274") (name "Net-(U29-BASE)") (class "Default")
      (node (ref "R58") (pin "2") (pinfunction "2_2") (pintype "passive"))
      (node (ref "U29") (pin "P$1") (pinfunction "BASE_P$1") (pintype "bidirectional"))
    )
    (net (code "275") (name "Net-(U29-COLLECTOR)") (class "Default")
      (node (ref "D29") (pin "A") (pinfunction "A_A") (pintype "passive"))
      (node (ref "LED28") (pin "C") (pinfunction "C_C") (pintype "passive"))
      (node (ref "U29") (pin "P$3") (pinfunction "COLLECTOR_P$3") (pintype "bidirectional"))
      (node (ref "X5") (pin "3") (pinfunction "K_3") (pintype "passive"))
    )
    (net (code "276") (name "Net-(U30-BASE)") (class "Default")
      (node (ref "R67") (pin "2") (pinfunction "2_2") (pintype "passive"))
      (node (ref "U30") (pin "P$1") (pinfunction "BASE_P$1") (pintype "bidirectional"))
    )
    (net (code "277") (name "Net-(U30-COLLECTOR)") (class "Default")
      (node (ref "D30") (pin "A") (pinfunction "A_A") (pintype "passive"))
      (node (ref "LED29") (pin "C") (pinfunction "C_C") (pintype "passive"))
      (node (ref "U30") (pin "P$3") (pinfunction "COLLECTOR_P$3") (pintype "bidirectional"))
      (node (ref "X5") (pin "4") (pinfunction "K_4") (pintype "passive"))
    )
    (net (code "278") (name "V-") (class "Default")
      (node (ref "C1") (pin "2") (pinfunction "2_2") (pintype "passive"))
      (node (ref "C10") (pin "2") (pinfunction "2_2") (pintype "passive"))
      (node (ref "C11") (pin "2") (pinfunction "2_2") (pintype "passive"))
      (node (ref "C13") (pin "1") (pinfunction "1_1") (pintype "passive"))
      (node (ref "C14") (pin "1") (pinfunction "1_1") (pintype "passive"))
      (node (ref "C15") (pin "2") (pinfunction "2_2") (pintype "passive"))
      (node (ref "C17") (pin "2") (pinfunction "2_2") (pintype "passive"))
      (node (ref "C18") (pin "2") (pinfunction "2_2") (pintype "passive"))
      (node (ref "C19") (pin "2") (pinfunction "2_2") (pintype "passive"))
      (node (ref "C2") (pin "2") (pinfunction "2_2") (pintype "passive"))
      (node (ref "C20") (pin "2") (pinfunction "2_2") (pintype "passive"))
      (node (ref "C21") (pin "2") (pinfunction "2_2") (pintype "passive"))
      (node (ref "C22") (pin "2") (pinfunction "2_2") (pintype "passive"))
      (node (ref "C23") (pin "2") (pinfunction "2_2") (pintype "passive"))
      (node (ref "C24") (pin "2") (pinfunction "2_2") (pintype "passive"))
      (node (ref "C25") (pin "2") (pinfunction "2_2") (pintype "passive"))
      (node (ref "C26") (pin "2") (pinfunction "2_2") (pintype "passive"))
      (node (ref "C27") (pin "2") (pinfunction "2_2") (pintype "passive"))
      (node (ref "C28") (pin "2") (pinfunction "2_2") (pintype "passive"))
      (node (ref "C29") (pin "2") (pinfunction "2_2") (pintype "passive"))
      (node (ref "C3") (pin "2") (pinfunction "2_2") (pintype "passive"))
      (node (ref "C30") (pin "2") (pinfunction "2_2") (pintype "passive"))
      (node (ref "C31") (pin "2") (pinfunction "2_2") (pintype "passive"))
      (node (ref "C32") (pin "2") (pinfunction "2_2") (pintype "passive"))
      (node (ref "C33") (pin "2") (pinfunction "2_2") (pintype "passive"))
      (node (ref "C34") (pin "2") (pinfunction "2_2") (pintype "passive"))
      (node (ref "C35") (pin "2") (pinfunction "2_2") (pintype "passive"))
      (node (ref "C36") (pin "2") (pinfunction "2_2") (pintype "passive"))
      (node (ref "C37") (pin "2") (pinfunction "2_2") (pintype "passive"))
      (node (ref "C38") (pin "2") (pinfunction "2_2") (pintype "passive"))
      (node (ref "C39") (pin "2") (pinfunction "2_2") (pintype "passive"))
      (node (ref "C4") (pin "2") (pinfunction "2_2") (pintype "passive"))
      (node (ref "C40") (pin "2") (pinfunction "2_2") (pintype "passive"))
      (node (ref "C41") (pin "2") (pinfunction "2_2") (pintype "passive"))
      (node (ref "C42") (pin "2") (pinfunction "2_2") (pintype "passive"))
      (node (ref "C43") (pin "2") (pinfunction "2_2") (pintype "passive"))
      (node (ref "C44") (pin "2") (pinfunction "2_2") (pintype "passive"))
      (node (ref "C45") (pin "1") (pinfunction "1_1") (pintype "passive"))
      (node (ref "C46") (pin "1") (pinfunction "1_1") (pintype "passive"))
      (node (ref "C47") (pin "2") (pinfunction "2_2") (pintype "passive"))
      (node (ref "C48") (pin "2") (pinfunction "2_2") (pintype "passive"))
      (node (ref "C49") (pin "2") (pinfunction "2_2") (pintype "passive"))
      (node (ref "C5") (pin "2") (pinfunction "2_2") (pintype "passive"))
      (node (ref "C50") (pin "2") (pinfunction "2_2") (pintype "passive"))
      (node (ref "C51") (pin "2") (pinfunction "2_2") (pintype "passive"))
      (node (ref "C52") (pin "2") (pinfunction "2_2") (pintype "passive"))
      (node (ref "C53") (pin "2") (pinfunction "2_2") (pintype "passive"))
      (node (ref "C54") (pin "2") (pinfunction "2_2") (pintype "passive"))
      (node (ref "C55") (pin "2") (pinfunction "2_2") (pintype "passive"))
      (node (ref "C56") (pin "2") (pinfunction "2_2") (pintype "passive"))
      (node (ref "C57") (pin "2") (pinfunction "2_2") (pintype "passive"))
      (node (ref "C58") (pin "2") (pinfunction "2_2") (pintype "passive"))
      (node (ref "C59") (pin "2") (pinfunction "2_2") (pintype "passive"))
      (node (ref "C6") (pin "2") (pinfunction "2_2") (pintype "passive"))
      (node (ref "C60") (pin "2") (pinfunction "2_2") (pintype "passive"))
      (node (ref "C61") (pin "2") (pinfunction "2_2") (pintype "passive"))
      (node (ref "C62") (pin "2") (pinfunction "2_2") (pintype "passive"))
      (node (ref "C7") (pin "2") (pinfunction "2_2") (pintype "passive"))
      (node (ref "C8") (pin "2") (pinfunction "2_2") (pintype "passive"))
      (node (ref "C9") (pin "2") (pinfunction "2_2") (pintype "passive"))
      (node (ref "CONN1") (pin "P5") (pinfunction "GND_P5") (pintype "bidirectional"))
      (node (ref "IC2") (pin "10") (pinfunction "VSS_10") (pintype "power_in"))
      (node (ref "IC2") (pin "19") (pinfunction "VSSA_19") (pintype "power_in"))
      (node (ref "IC2") (pin "27") (pinfunction "VSS_27") (pintype "power_in"))
      (node (ref "IC2") (pin "49") (pinfunction "VSS_49") (pintype "power_in"))
      (node (ref "IC2") (pin "74") (pinfunction "VSS_74") (pintype "power_in"))
      (node (ref "IC2") (pin "99") (pinfunction "VSS_99") (pintype "power_in"))
      (node (ref "J1") (pin "1") (pinfunction "1_1") (pintype "passive"))
      (node (ref "J2") (pin "GND") (pinfunction "GND_GND") (pintype "bidirectional"))
      (node (ref "J2") (pin "SHIELD0") (pinfunction "SHIELD0_SHIELD0") (pintype "bidirectional"))
      (node (ref "J2") (pin "SHIELD1") (pinfunction "SHIELD1_SHIELD1") (pintype "bidirectional"))
      (node (ref "J3") (pin "GND") (pinfunction "GND_GND") (pintype "bidirectional"))
      (node (ref "J3") (pin "GNDBREAK") (pinfunction "GNDBREAK_GNDBREAK") (pintype "bidirectional"))
      (node (ref "JP1") (pin "10") (pinfunction "10_10") (pintype "passive"))
      (node (ref "JP1") (pin "13") (pinfunction "13_13") (pintype "passive"))
      (node (ref "JP1") (pin "25") (pinfunction "25_25") (pintype "passive"))
      (node (ref "JP1") (pin "30") (pinfunction "30_30") (pintype "passive"))
      (node (ref "Q1") (pin "2") (pinfunction "GND_2") (pintype "bidirectional"))
      (node (ref "Q1") (pin "4") (pinfunction "GND_4") (pintype "bidirectional"))
      (node (ref "Q5") (pin "2") (pinfunction "GND_2") (pintype "bidirectional"))
      (node (ref "Q5") (pin "4") (pinfunction "GND_4") (pintype "bidirectional"))
      (node (ref "R1") (pin "2") (pinfunction "2_2") (pintype "passive"))
      (node (ref "R100") (pin "2") (pinfunction "2_2") (pintype "passive"))
      (node (ref "R101") (pin "2") (pinfunction "2_2") (pintype "passive"))
      (node (ref "R102") (pin "2") (pinfunction "2_2") (pintype "passive"))
      (node (ref "R103") (pin "2") (pinfunction "2_2") (pintype "passive"))
      (node (ref "R104") (pin "2") (pinfunction "2_2") (pintype "passive"))
      (node (ref "R105") (pin "2") (pinfunction "2_2") (pintype "passive"))
      (node (ref "R106") (pin "2") (pinfunction "2_2") (pintype "passive"))
      (node (ref "R107") (pin "2") (pinfunction "2_2") (pintype "passive"))
      (node (ref "R108") (pin "2") (pinfunction "2_2") (pintype "passive"))
      (node (ref "R109") (pin "2") (pinfunction "2_2") (pintype "passive"))
      (node (ref "R11") (pin "2") (pinfunction "2_2") (pintype "passive"))
      (node (ref "R110") (pin "2") (pinfunction "2_2") (pintype "passive"))
      (node (ref "R111") (pin "2") (pinfunction "2_2") (pintype "passive"))
      (node (ref "R112") (pin "2") (pinfunction "2_2") (pintype "passive"))
      (node (ref "R113") (pin "2") (pinfunction "2_2") (pintype "passive"))
      (node (ref "R114") (pin "2") (pinfunction "2_2") (pintype "passive"))
      (node (ref "R115") (pin "2") (pinfunction "2_2") (pintype "passive"))
      (node (ref "R116") (pin "2") (pinfunction "2_2") (pintype "passive"))
      (node (ref "R117") (pin "2") (pinfunction "2_2") (pintype "passive"))
      (node (ref "R118") (pin "2") (pinfunction "2_2") (pintype "passive"))
      (node (ref "R15") (pin "1") (pinfunction "1_1") (pintype "passive"))
      (node (ref "R19") (pin "1") (pinfunction "1_1") (pintype "passive"))
      (node (ref "R2") (pin "2") (pinfunction "2_2") (pintype "passive"))
      (node (ref "R25") (pin "1") (pinfunction "1_1") (pintype "passive"))
      (node (ref "R32") (pin "1") (pinfunction "1_1") (pintype "passive"))
      (node (ref "R35") (pin "1") (pinfunction "1_1") (pintype "passive"))
      (node (ref "R37") (pin "1") (pinfunction "1_1") (pintype "passive"))
      (node (ref "R40") (pin "1") (pinfunction "1_1") (pintype "passive"))
      (node (ref "R42") (pin "2") (pinfunction "2_2") (pintype "passive"))
      (node (ref "R43") (pin "1") (pinfunction "1_1") (pintype "passive"))
      (node (ref "R45") (pin "1") (pinfunction "1_1") (pintype "passive"))
      (node (ref "R46") (pin "1") (pinfunction "1_1") (pintype "passive"))
      (node (ref "R49") (pin "1") (pinfunction "1_1") (pintype "passive"))
      (node (ref "R5") (pin "1") (pinfunction "1_1") (pintype "passive"))
      (node (ref "R51") (pin "2") (pinfunction "2_2") (pintype "passive"))
      (node (ref "R53") (pin "1") (pinfunction "1_1") (pintype "passive"))
      (node (ref "R55") (pin "1") (pinfunction "1_1") (pintype "passive"))
      (node (ref "R56") (pin "1") (pinfunction "1_1") (pintype "passive"))
      (node (ref "R59") (pin "1") (pinfunction "1_1") (pintype "passive"))
      (node (ref "R61") (pin "2") (pinfunction "2_2") (pintype "passive"))
      (node (ref "R62") (pin "1") (pinfunction "1_1") (pintype "passive"))
      (node (ref "R64") (pin "1") (pinfunction "1_1") (pintype "passive"))
      (node (ref "R65") (pin "1") (pinfunction "1_1") (pintype "passive"))
      (node (ref "R68") (pin "1") (pinfunction "1_1") (pintype "passive"))
      (node (ref "R70") (pin "2") (pinfunction "2_2") (pintype "passive"))
      (node (ref "R71") (pin "1") (pinfunction "1_1") (pintype "passive"))
      (node (ref "R74") (pin "1") (pinfunction "1_1") (pintype "passive"))
      (node (ref "R77") (pin "1") (pinfunction "1_1") (pintype "passive"))
      (node (ref "R80") (pin "1") (pinfunction "1_1") (pintype "passive"))
      (node (ref "R83") (pin "1") (pinfunction "1_1") (pintype "passive"))
      (node (ref "R86") (pin "1") (pinfunction "1_1") (pintype "passive"))
      (node (ref "R89") (pin "1") (pinfunction "1_1") (pintype "passive"))
      (node (ref "R9") (pin "2") (pinfunction "2_2") (pintype "passive"))
      (node (ref "R92") (pin "1") (pinfunction "1_1") (pintype "passive"))
      (node (ref "R95") (pin "2") (pinfunction "2_2") (pintype "passive"))
      (node (ref "R96") (pin "2") (pinfunction "2_2") (pintype "passive"))
      (node (ref "R97") (pin "2") (pinfunction "2_2") (pintype "passive"))
      (node (ref "R98") (pin "2") (pinfunction "2_2") (pintype "passive"))
      (node (ref "R99") (pin "2") (pinfunction "2_2") (pintype "passive"))
      (node (ref "RN1") (pin "5") (pinfunction "2_5") (pintype "passive"))
      (node (ref "RN2") (pin "5") (pinfunction "2_5") (pintype "passive"))
      (node (ref "RN2") (pin "6") (pinfunction "2_6") (pintype "passive"))
      (node (ref "RN2") (pin "7") (pinfunction "2_7") (pintype "passive"))
      (node (ref "RN2") (pin "8") (pinfunction "2_8") (pintype "passive"))
      (node (ref "S2") (pin "1") (pinfunction "1_1") (pintype "passive"))
      (node (ref "U$1") (pin "1") (pinfunction "GND_1") (pintype "bidirectional"))
      (node (ref "U$2") (pin "IN-.1") (pinfunction "IN-.1_IN-.1") (pintype "bidirectional"))
      (node (ref "U$2") (pin "IN-.2") (pinfunction "IN-.2_IN-.2") (pintype "bidirectional"))
      (node (ref "U$2") (pin "OUT-.1") (pinfunction "OUT-.1_OUT-.1") (pintype "bidirectional"))
      (node (ref "U$2") (pin "OUT-.2") (pinfunction "OUT-.2_OUT-.2") (pintype "bidirectional"))
      (node (ref "U1") (pin "P$2") (pinfunction "EMITTER_P$2") (pintype "bidirectional"))
      (node (ref "U10") (pin "P$2") (pinfunction "EMITTER_P$2") (pintype "bidirectional"))
      (node (ref "U11") (pin "P$2") (pinfunction "EMITTER_P$2") (pintype "bidirectional"))
      (node (ref "U12") (pin "P$2") (pinfunction "EMITTER_P$2") (pintype "bidirectional"))
      (node (ref "U13") (pin "P$2") (pinfunction "EMITTER_P$2") (pintype "bidirectional"))
      (node (ref "U14") (pin "P$2") (pinfunction "EMITTER_P$2") (pintype "bidirectional"))
      (node (ref "U15") (pin "P$2") (pinfunction "EMITTER_P$2") (pintype "bidirectional"))
      (node (ref "U16") (pin "P$2") (pinfunction "EMITTER_P$2") (pintype "bidirectional"))
      (node (ref "U17") (pin "P$2") (pinfunction "EMITTER_P$2") (pintype "bidirectional"))
      (node (ref "U18") (pin "P$2") (pinfunction "EMITTER_P$2") (pintype "bidirectional"))
      (node (ref "U19") (pin "P$2") (pinfunction "EMITTER_P$2") (pintype "bidirectional"))
      (node (ref "U2") (pin "14") (pinfunction "AGND_14") (pintype "passive"))
      (node (ref "U2") (pin "16") (pinfunction "AGND_16") (pintype "passive"))
      (node (ref "U2") (pin "19") (pinfunction "AGND_19") (pintype "passive"))
      (node (ref "U2") (pin "29") (pinfunction "GND_29") (pintype "passive"))
      (node (ref "U2") (pin "3") (pinfunction "AGND_3") (pintype "passive"))
      (node (ref "U2") (pin "48") (pinfunction "AGND_48") (pintype "passive"))
      (node (ref "U2") (pin "9") (pinfunction "AGND_9") (pintype "passive"))
      (node (ref "U20") (pin "P$2") (pinfunction "EMITTER_P$2") (pintype "bidirectional"))
      (node (ref "U21") (pin "P$2") (pinfunction "EMITTER_P$2") (pintype "bidirectional"))
      (node (ref "U22") (pin "P$2") (pinfunction "EMITTER_P$2") (pintype "bidirectional"))
      (node (ref "U23") (pin "P$2") (pinfunction "EMITTER_P$2") (pintype "bidirectional"))
      (node (ref "U24") (pin "P$2") (pinfunction "EMITTER_P$2") (pintype "bidirectional"))
      (node (ref "U25") (pin "P$2") (pinfunction "EMITTER_P$2") (pintype "bidirectional"))
      (node (ref "U27") (pin "P$2") (pinfunction "EMITTER_P$2") (pintype "bidirectional"))
      (node (ref "U28") (pin "P$2") (pinfunction "EMITTER_P$2") (pintype "bidirectional"))
      (node (ref "U29") (pin "P$2") (pinfunction "EMITTER_P$2") (pintype "bidirectional"))
      (node (ref "U3") (pin "P$2") (pinfunction "EMITTER_P$2") (pintype "bidirectional"))
      (node (ref "U30") (pin "P$2") (pinfunction "EMITTER_P$2") (pintype "bidirectional"))
      (node (ref "U4") (pin "P$2") (pinfunction "EMITTER_P$2") (pintype "bidirectional"))
      (node (ref "U5") (pin "P$2") (pinfunction "EMITTER_P$2") (pintype "bidirectional"))
      (node (ref "U6") (pin "P$2") (pinfunction "EMITTER_P$2") (pintype "bidirectional"))
      (node (ref "U7") (pin "P$2") (pinfunction "EMITTER_P$2") (pintype "bidirectional"))
      (node (ref "U8") (pin "P$2") (pinfunction "EMITTER_P$2") (pintype "bidirectional"))
      (node (ref "U9") (pin "P$2") (pinfunction "EMITTER_P$2") (pintype "bidirectional"))
    )
    (net (code "279") (name "unconnected-(CONN1B-USBID-PadP4)") (class "Default")
      (node (ref "CONN1") (pin "P4") (pinfunction "USBID_P4") (pintype "bidirectional"))
    )
    (net (code "280") (name "unconnected-(J2-PadNC)") (class "Default")
      (node (ref "J2") (pin "NC") (pinfunction "NC_NC") (pintype "bidirectional"))
    )
    (net (code "281") (name "unconnected-(U$1-CTS-Pad9)") (class "Default")
      (node (ref "U$1") (pin "9") (pinfunction "CTS_9") (pintype "bidirectional"))
    )
    (net (code "282") (name "unconnected-(U$1-DCD-Pad12)") (class "Default")
      (node (ref "U$1") (pin "12") (pinfunction "DCD_12") (pintype "bidirectional"))
    )
    (net (code "283") (name "unconnected-(U$1-DSR-Pad10)") (class "Default")
      (node (ref "U$1") (pin "10") (pinfunction "DSR_10") (pintype "bidirectional"))
    )
    (net (code "284") (name "unconnected-(U$1-RI-Pad11)") (class "Default")
      (node (ref "U$1") (pin "11") (pinfunction "RI_11") (pintype "bidirectional"))
    )
    (net (code "285") (name "unconnected-(U$1-RS232-Pad15)") (class "Default")
      (node (ref "U$1") (pin "15") (pinfunction "RS232_15") (pintype "bidirectional"))
    )
    (net (code "286") (name "unconnected-(U2-DNC-Pad7)") (class "Default")
      (node (ref "U2") (pin "7") (pinfunction "DNC_7") (pintype "passive"))
    )
    (net (code "287") (name "unconnected-(U2-DUPLED-Pad26)") (class "Default")
      (node (ref "U2") (pin "26") (pinfunction "DUPLED_26") (pintype "passive"))
    )
    (net (code "288") (name "unconnected-(U2-NC-Pad12)") (class "Default")
      (node (ref "U2") (pin "12") (pinfunction "NC_12") (pintype "passive"))
    )
    (net (code "289") (name "unconnected-(U2-NC-Pad13)") (class "Default")
      (node (ref "U2") (pin "13") (pinfunction "NC_13") (pintype "passive"))
    )
    (net (code "290") (name "unconnected-(U2-NC-Pad46)") (class "Default")
      (node (ref "U2") (pin "46") (pinfunction "NC_46") (pintype "passive"))
    )
    (net (code "291") (name "unconnected-(U2-NC-Pad47)") (class "Default")
      (node (ref "U2") (pin "47") (pinfunction "NC_47") (pintype "passive"))
    )
    (net (code "292") (name "unconnected-(U2-RSVD-Pad23)") (class "Default")
      (node (ref "U2") (pin "23") (pinfunction "RSVD_23") (pintype "passive"))
    )
    (net (code "293") (name "unconnected-(U2-SPDLED-Pad24)") (class "Default")
      (node (ref "U2") (pin "24") (pinfunction "SPDLED_24") (pintype "passive"))
    )
    (net (code "294") (name "unconnected-(U2-VBG-Pad18)") (class "Default")
      (node (ref "U2") (pin "18") (pinfunction "VBG_18") (pintype "passive"))
    )
  )
)
